# FPGA.net
KiCad netlist of a schematic drawn in Altium Designer
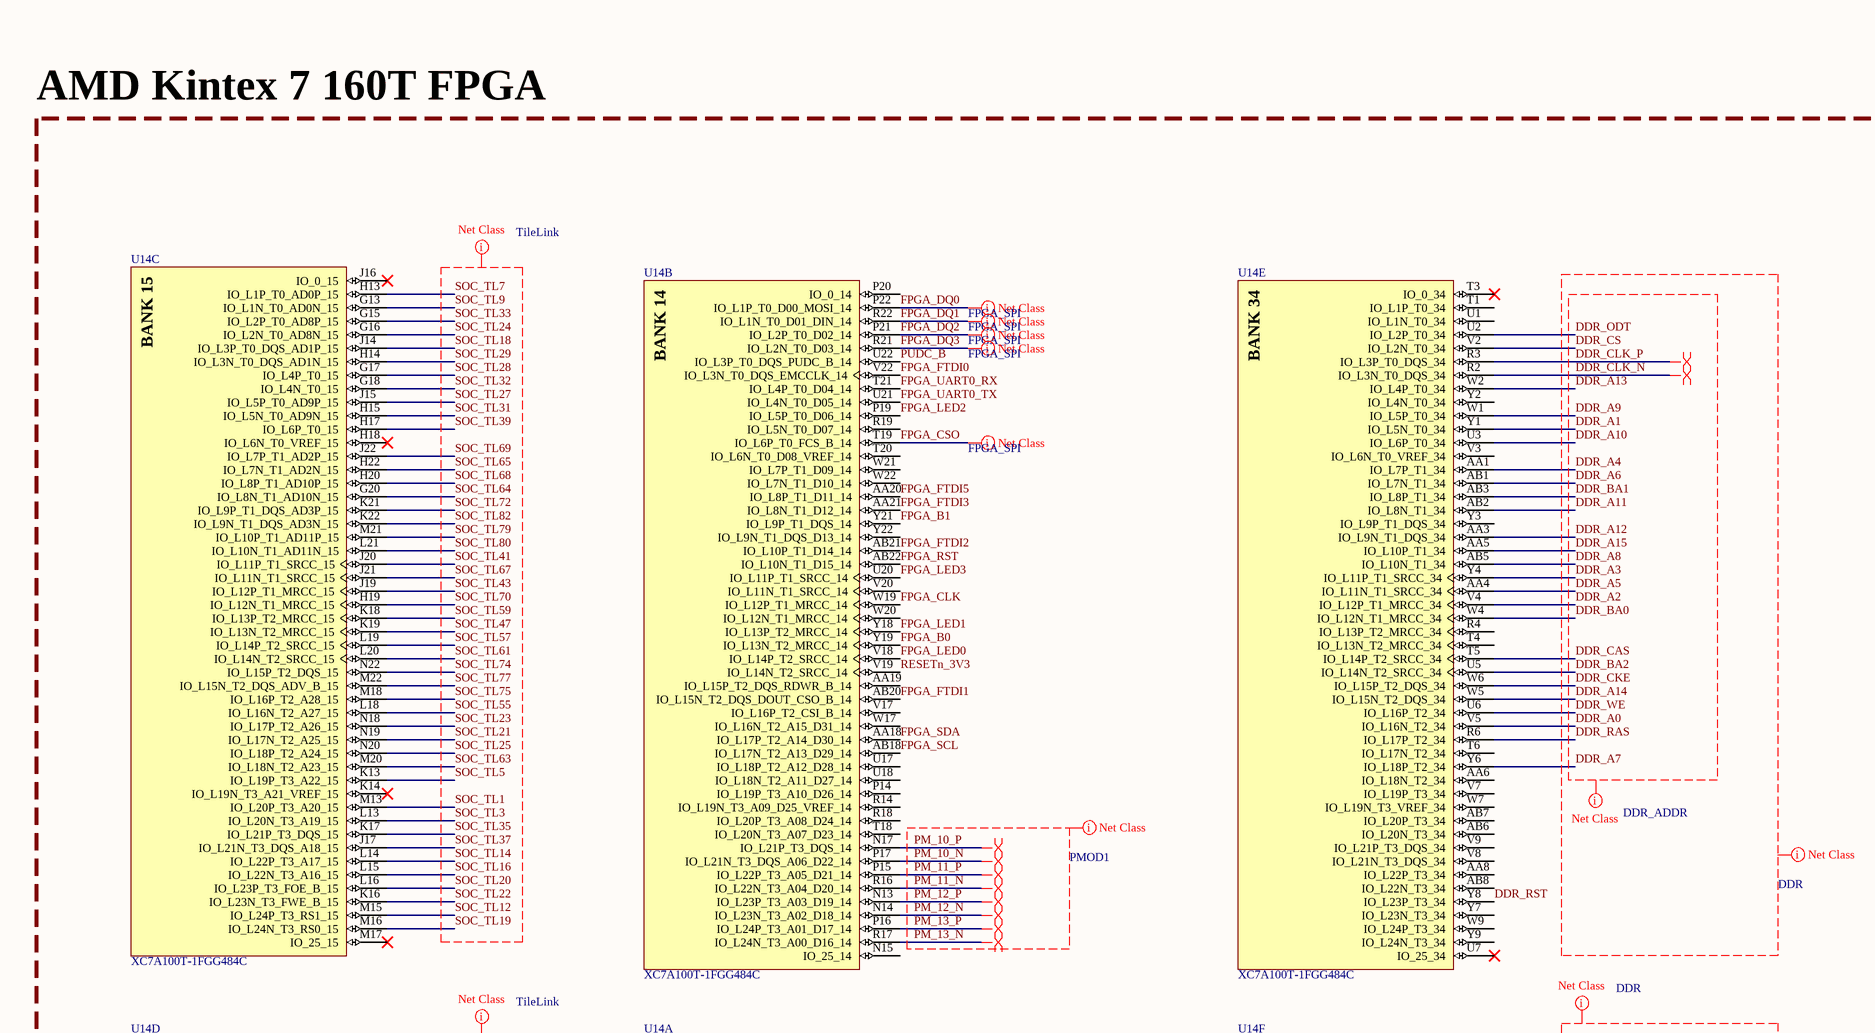
[diagram p0: FPGA.SchDoc, top left]
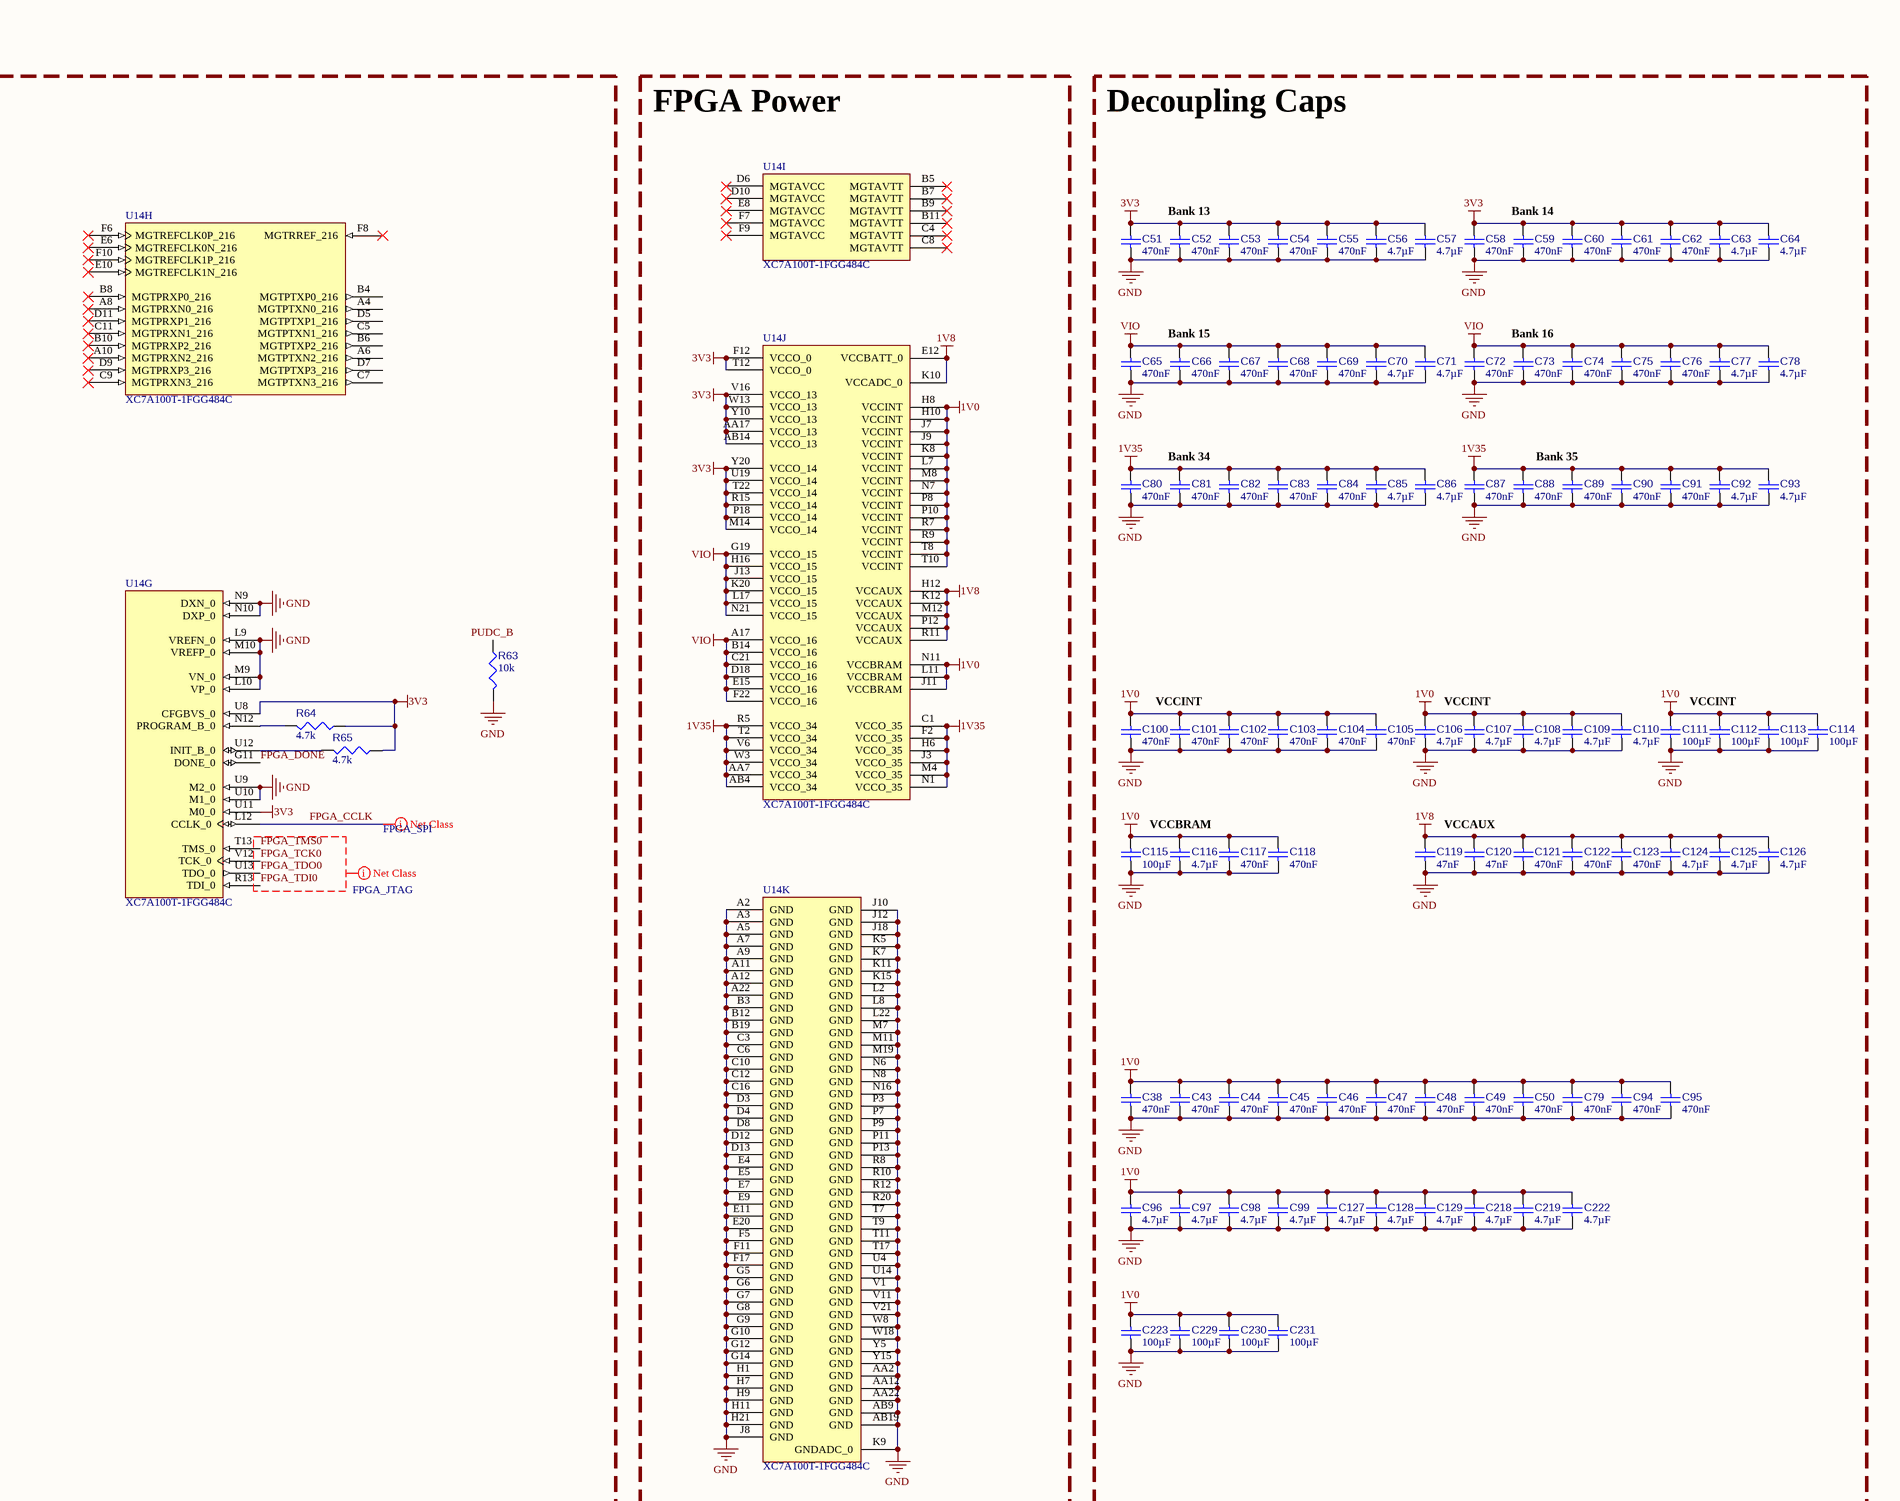
[diagram p1: FPGA.SchDoc, top right]
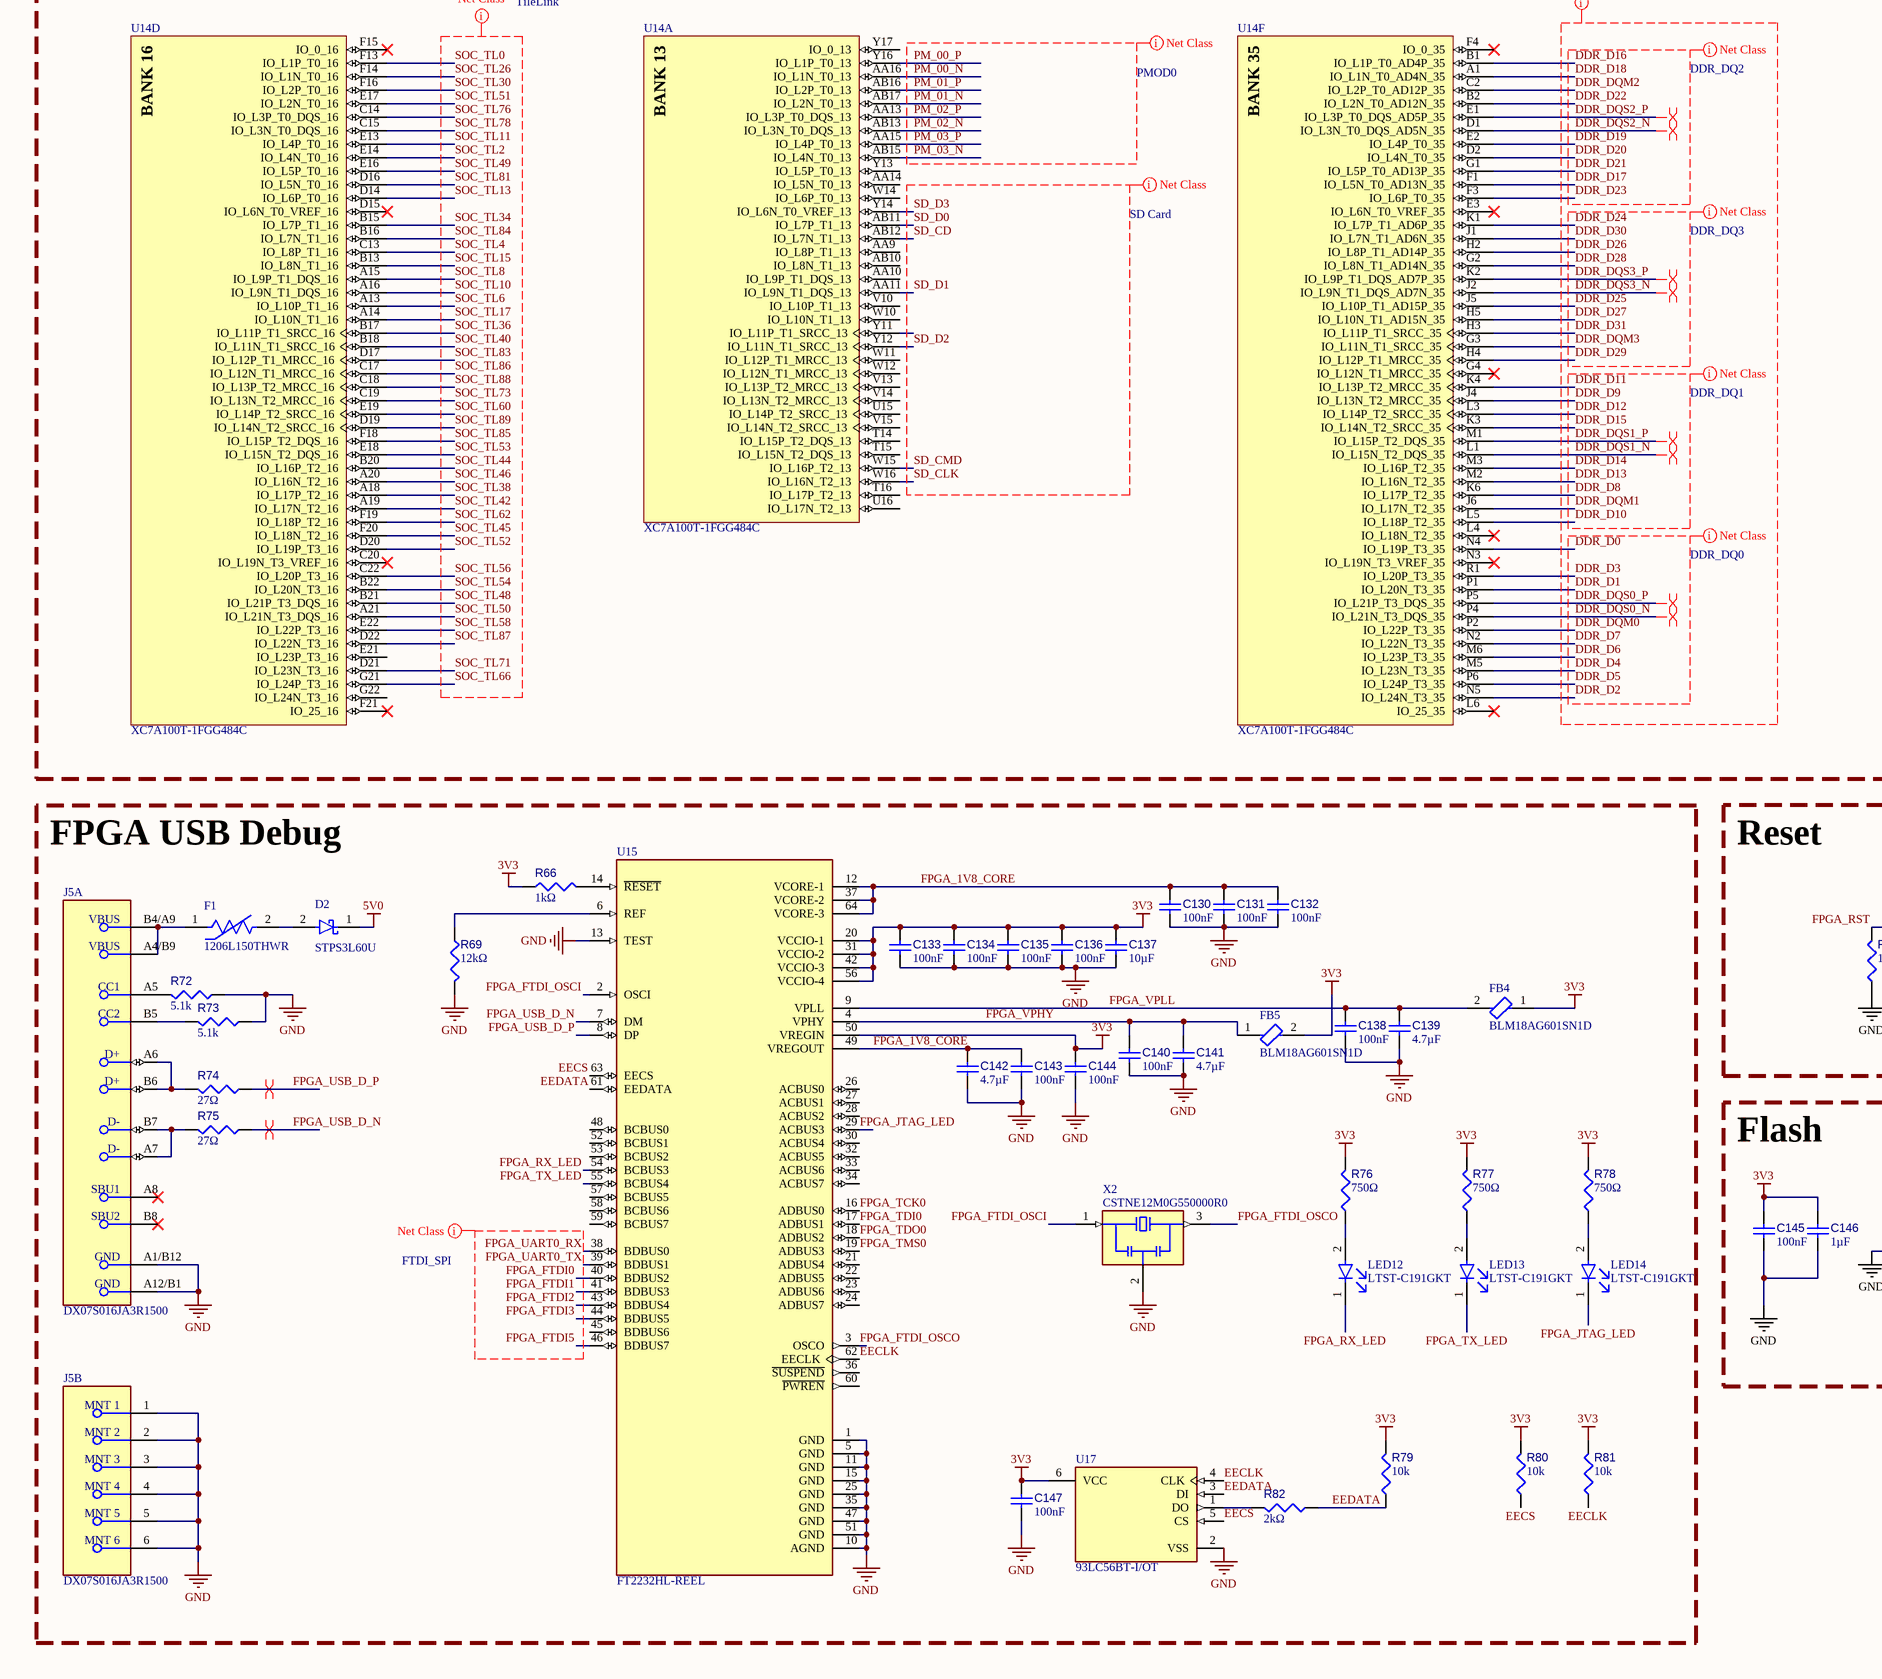
[diagram p2: FPGA.SchDoc, bottom left]
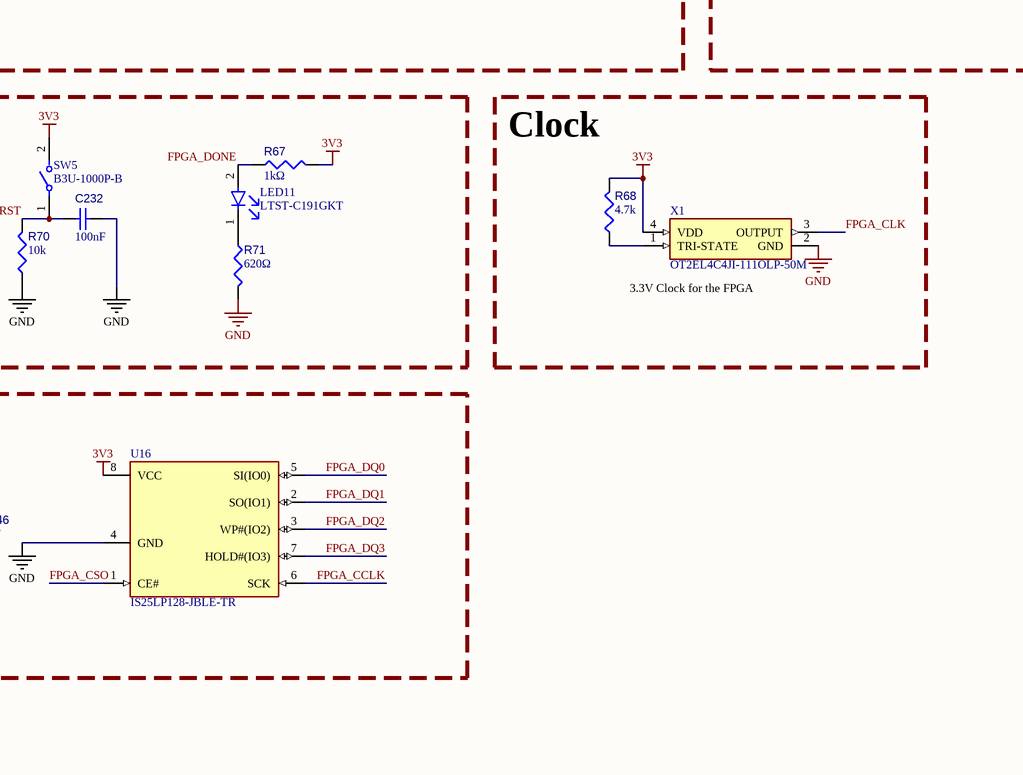
[diagram p3: FPGA.SchDoc, bottom right]

(export (version "E")
  (design (tool "Eeschema 10.0.6"))
  (components
    (comp (ref "C38")
      (value "470nF")
      (footprint "CAP-0402-MFG")
      (description "0402-470n-10%-16V-X5R-AECQ200")
      (fields (field (name "MANUFACTURER PART NUMBER") "GRT155R61C474KE01D") (field (name "TOLERANCE") "10%"))
      (libsource (lib "UC Berkeley – EE194") (part "CAP-NP-2P"))
    )
    (comp (ref "C43")
      (value "470nF")
      (footprint "CAP-0402-MFG")
      (description "0402-470n-10%-16V-X5R-AECQ200")
      (fields (field (name "MANUFACTURER PART NUMBER") "GRT155R61C474KE01D") (field (name "TOLERANCE") "10%"))
      (libsource (lib "UC Berkeley – EE194") (part "CAP-NP-2P"))
    )
    (comp (ref "C44")
      (value "470nF")
      (footprint "CAP-0402-MFG")
      (description "0402-470n-10%-16V-X5R-AECQ200")
      (fields (field (name "MANUFACTURER PART NUMBER") "GRT155R61C474KE01D") (field (name "TOLERANCE") "10%"))
      (libsource (lib "UC Berkeley – EE194") (part "CAP-NP-2P"))
    )
    (comp (ref "C45")
      (value "470nF")
      (footprint "CAP-0402-MFG")
      (description "0402-470n-10%-16V-X5R-AECQ200")
      (fields (field (name "MANUFACTURER PART NUMBER") "GRT155R61C474KE01D") (field (name "TOLERANCE") "10%"))
      (libsource (lib "UC Berkeley – EE194") (part "CAP-NP-2P"))
    )
    (comp (ref "C46")
      (value "470nF")
      (footprint "CAP-0402-MFG")
      (description "0402-470n-10%-16V-X5R-AECQ200")
      (fields (field (name "MANUFACTURER PART NUMBER") "GRT155R61C474KE01D") (field (name "TOLERANCE") "10%"))
      (libsource (lib "UC Berkeley – EE194") (part "CAP-NP-2P"))
    )
    (comp (ref "C47")
      (value "470nF")
      (footprint "CAP-0402-MFG")
      (description "0402-470n-10%-16V-X5R-AECQ200")
      (fields (field (name "MANUFACTURER PART NUMBER") "GRT155R61C474KE01D") (field (name "TOLERANCE") "10%"))
      (libsource (lib "UC Berkeley – EE194") (part "CAP-NP-2P"))
    )
    (comp (ref "C48")
      (value "470nF")
      (footprint "CAP-0402-MFG")
      (description "0402-470n-10%-16V-X5R-AECQ200")
      (fields (field (name "MANUFACTURER PART NUMBER") "GRT155R61C474KE01D") (field (name "TOLERANCE") "10%"))
      (libsource (lib "UC Berkeley – EE194") (part "CAP-NP-2P"))
    )
    (comp (ref "C49")
      (value "470nF")
      (footprint "CAP-0402-MFG")
      (description "0402-470n-10%-16V-X5R-AECQ200")
      (fields (field (name "MANUFACTURER PART NUMBER") "GRT155R61C474KE01D") (field (name "TOLERANCE") "10%"))
      (libsource (lib "UC Berkeley – EE194") (part "CAP-NP-2P"))
    )
    (comp (ref "C50")
      (value "470nF")
      (footprint "CAP-0402-MFG")
      (description "0402-470n-10%-16V-X5R-AECQ200")
      (fields (field (name "MANUFACTURER PART NUMBER") "GRT155R61C474KE01D") (field (name "TOLERANCE") "10%"))
      (libsource (lib "UC Berkeley – EE194") (part "CAP-NP-2P"))
    )
    (comp (ref "C51")
      (value "470nF")
      (footprint "CAP-0402-MFG")
      (description "0402-470n-10%-16V-X5R-AECQ200")
      (fields (field (name "MANUFACTURER PART NUMBER") "GRT155R61C474KE01D") (field (name "TOLERANCE") "10%"))
      (libsource (lib "UC Berkeley – EE194") (part "CAP-NP-2P"))
    )
    (comp (ref "C52")
      (value "470nF")
      (footprint "CAP-0402-MFG")
      (description "0402-470n-10%-16V-X5R-AECQ200")
      (fields (field (name "MANUFACTURER PART NUMBER") "GRT155R61C474KE01D") (field (name "TOLERANCE") "10%"))
      (libsource (lib "UC Berkeley – EE194") (part "CAP-NP-2P"))
    )
    (comp (ref "C53")
      (value "470nF")
      (footprint "CAP-0402-MFG")
      (description "0402-470n-10%-16V-X5R-AECQ200")
      (fields (field (name "MANUFACTURER PART NUMBER") "GRT155R61C474KE01D") (field (name "TOLERANCE") "10%"))
      (libsource (lib "UC Berkeley – EE194") (part "CAP-NP-2P"))
    )
    (comp (ref "C54")
      (value "470nF")
      (footprint "CAP-0402-MFG")
      (description "0402-470n-10%-16V-X5R-AECQ200")
      (fields (field (name "MANUFACTURER PART NUMBER") "GRT155R61C474KE01D") (field (name "TOLERANCE") "10%"))
      (libsource (lib "UC Berkeley – EE194") (part "CAP-NP-2P"))
    )
    (comp (ref "C55")
      (value "470nF")
      (footprint "CAP-0402-MFG")
      (description "0402-470n-10%-16V-X5R-AECQ200")
      (fields (field (name "MANUFACTURER PART NUMBER") "GRT155R61C474KE01D") (field (name "TOLERANCE") "10%"))
      (libsource (lib "UC Berkeley – EE194") (part "CAP-NP-2P"))
    )
    (comp (ref "C56")
      (value "4.7µF")
      (footprint "CAP-0402-MFG")
      (description "0402-4.7u-20%-25V-X5R")
      (fields (field (name "TOLERANCE") "20%") (field (name "MANUFACTURER PART NUMBER") "GRM155R61E475ME15D"))
      (libsource (lib "UC Berkeley – EE194") (part "CAP-NP-2P"))
    )
    (comp (ref "C57")
      (value "4.7µF")
      (footprint "CAP-0402-MFG")
      (description "0402-4.7u-20%-25V-X5R")
      (fields (field (name "TOLERANCE") "20%") (field (name "MANUFACTURER PART NUMBER") "GRM155R61E475ME15D"))
      (libsource (lib "UC Berkeley – EE194") (part "CAP-NP-2P"))
    )
    (comp (ref "C58")
      (value "470nF")
      (footprint "CAP-0402-MFG")
      (description "0402-470n-10%-16V-X5R-AECQ200")
      (fields (field (name "MANUFACTURER PART NUMBER") "GRT155R61C474KE01D") (field (name "TOLERANCE") "10%"))
      (libsource (lib "UC Berkeley – EE194") (part "CAP-NP-2P"))
    )
    (comp (ref "C59")
      (value "470nF")
      (footprint "CAP-0402-MFG")
      (description "0402-470n-10%-16V-X5R-AECQ200")
      (fields (field (name "MANUFACTURER PART NUMBER") "GRT155R61C474KE01D") (field (name "TOLERANCE") "10%"))
      (libsource (lib "UC Berkeley – EE194") (part "CAP-NP-2P"))
    )
    (comp (ref "C60")
      (value "470nF")
      (footprint "CAP-0402-MFG")
      (description "0402-470n-10%-16V-X5R-AECQ200")
      (fields (field (name "MANUFACTURER PART NUMBER") "GRT155R61C474KE01D") (field (name "TOLERANCE") "10%"))
      (libsource (lib "UC Berkeley – EE194") (part "CAP-NP-2P"))
    )
    (comp (ref "C61")
      (value "470nF")
      (footprint "CAP-0402-MFG")
      (description "0402-470n-10%-16V-X5R-AECQ200")
      (fields (field (name "MANUFACTURER PART NUMBER") "GRT155R61C474KE01D") (field (name "TOLERANCE") "10%"))
      (libsource (lib "UC Berkeley – EE194") (part "CAP-NP-2P"))
    )
    (comp (ref "C62")
      (value "470nF")
      (footprint "CAP-0402-MFG")
      (description "0402-470n-10%-16V-X5R-AECQ200")
      (fields (field (name "MANUFACTURER PART NUMBER") "GRT155R61C474KE01D") (field (name "TOLERANCE") "10%"))
      (libsource (lib "UC Berkeley – EE194") (part "CAP-NP-2P"))
    )
    (comp (ref "C63")
      (value "4.7µF")
      (footprint "CAP-0402-MFG")
      (description "0402-4.7u-20%-25V-X5R")
      (fields (field (name "TOLERANCE") "20%") (field (name "MANUFACTURER PART NUMBER") "GRM155R61E475ME15D"))
      (libsource (lib "UC Berkeley – EE194") (part "CAP-NP-2P"))
    )
    (comp (ref "C64")
      (value "4.7µF")
      (footprint "CAP-0402-MFG")
      (description "0402-4.7u-20%-25V-X5R")
      (fields (field (name "TOLERANCE") "20%") (field (name "MANUFACTURER PART NUMBER") "GRM155R61E475ME15D"))
      (libsource (lib "UC Berkeley – EE194") (part "CAP-NP-2P"))
    )
    (comp (ref "C65")
      (value "470nF")
      (footprint "CAP-0402-MFG")
      (description "0402-470n-10%-16V-X5R-AECQ200")
      (fields (field (name "MANUFACTURER PART NUMBER") "GRT155R61C474KE01D") (field (name "TOLERANCE") "10%"))
      (libsource (lib "UC Berkeley – EE194") (part "CAP-NP-2P"))
    )
    (comp (ref "C66")
      (value "470nF")
      (footprint "CAP-0402-MFG")
      (description "0402-470n-10%-16V-X5R-AECQ200")
      (fields (field (name "MANUFACTURER PART NUMBER") "GRT155R61C474KE01D") (field (name "TOLERANCE") "10%"))
      (libsource (lib "UC Berkeley – EE194") (part "CAP-NP-2P"))
    )
    (comp (ref "C67")
      (value "470nF")
      (footprint "CAP-0402-MFG")
      (description "0402-470n-10%-16V-X5R-AECQ200")
      (fields (field (name "MANUFACTURER PART NUMBER") "GRT155R61C474KE01D") (field (name "TOLERANCE") "10%"))
      (libsource (lib "UC Berkeley – EE194") (part "CAP-NP-2P"))
    )
    (comp (ref "C68")
      (value "470nF")
      (footprint "CAP-0402-MFG")
      (description "0402-470n-10%-16V-X5R-AECQ200")
      (fields (field (name "MANUFACTURER PART NUMBER") "GRT155R61C474KE01D") (field (name "TOLERANCE") "10%"))
      (libsource (lib "UC Berkeley – EE194") (part "CAP-NP-2P"))
    )
    (comp (ref "C69")
      (value "470nF")
      (footprint "CAP-0402-MFG")
      (description "0402-470n-10%-16V-X5R-AECQ200")
      (fields (field (name "MANUFACTURER PART NUMBER") "GRT155R61C474KE01D") (field (name "TOLERANCE") "10%"))
      (libsource (lib "UC Berkeley – EE194") (part "CAP-NP-2P"))
    )
    (comp (ref "C70")
      (value "4.7µF")
      (footprint "CAP-0402-MFG")
      (description "0402-4.7u-20%-25V-X5R")
      (fields (field (name "TOLERANCE") "20%") (field (name "MANUFACTURER PART NUMBER") "GRM155R61E475ME15D"))
      (libsource (lib "UC Berkeley – EE194") (part "CAP-NP-2P"))
    )
    (comp (ref "C71")
      (value "4.7µF")
      (footprint "CAP-0402-MFG")
      (description "0402-4.7u-20%-25V-X5R")
      (fields (field (name "TOLERANCE") "20%") (field (name "MANUFACTURER PART NUMBER") "GRM155R61E475ME15D"))
      (libsource (lib "UC Berkeley – EE194") (part "CAP-NP-2P"))
    )
    (comp (ref "C72")
      (value "470nF")
      (footprint "CAP-0402-MFG")
      (description "0402-470n-10%-16V-X5R-AECQ200")
      (fields (field (name "MANUFACTURER PART NUMBER") "GRT155R61C474KE01D") (field (name "TOLERANCE") "10%"))
      (libsource (lib "UC Berkeley – EE194") (part "CAP-NP-2P"))
    )
    (comp (ref "C73")
      (value "470nF")
      (footprint "CAP-0402-MFG")
      (description "0402-470n-10%-16V-X5R-AECQ200")
      (fields (field (name "MANUFACTURER PART NUMBER") "GRT155R61C474KE01D") (field (name "TOLERANCE") "10%"))
      (libsource (lib "UC Berkeley – EE194") (part "CAP-NP-2P"))
    )
    (comp (ref "C74")
      (value "470nF")
      (footprint "CAP-0402-MFG")
      (description "0402-470n-10%-16V-X5R-AECQ200")
      (fields (field (name "MANUFACTURER PART NUMBER") "GRT155R61C474KE01D") (field (name "TOLERANCE") "10%"))
      (libsource (lib "UC Berkeley – EE194") (part "CAP-NP-2P"))
    )
    (comp (ref "C75")
      (value "470nF")
      (footprint "CAP-0402-MFG")
      (description "0402-470n-10%-16V-X5R-AECQ200")
      (fields (field (name "MANUFACTURER PART NUMBER") "GRT155R61C474KE01D") (field (name "TOLERANCE") "10%"))
      (libsource (lib "UC Berkeley – EE194") (part "CAP-NP-2P"))
    )
    (comp (ref "C76")
      (value "470nF")
      (footprint "CAP-0402-MFG")
      (description "0402-470n-10%-16V-X5R-AECQ200")
      (fields (field (name "MANUFACTURER PART NUMBER") "GRT155R61C474KE01D") (field (name "TOLERANCE") "10%"))
      (libsource (lib "UC Berkeley – EE194") (part "CAP-NP-2P"))
    )
    (comp (ref "C77")
      (value "4.7µF")
      (footprint "CAP-0402-MFG")
      (description "0402-4.7u-20%-25V-X5R")
      (fields (field (name "TOLERANCE") "20%") (field (name "MANUFACTURER PART NUMBER") "GRM155R61E475ME15D"))
      (libsource (lib "UC Berkeley – EE194") (part "CAP-NP-2P"))
    )
    (comp (ref "C78")
      (value "4.7µF")
      (footprint "CAP-0402-MFG")
      (description "0402-4.7u-20%-25V-X5R")
      (fields (field (name "TOLERANCE") "20%") (field (name "MANUFACTURER PART NUMBER") "GRM155R61E475ME15D"))
      (libsource (lib "UC Berkeley – EE194") (part "CAP-NP-2P"))
    )
    (comp (ref "C79")
      (value "470nF")
      (footprint "CAP-0402-MFG")
      (description "0402-470n-10%-16V-X5R-AECQ200")
      (fields (field (name "MANUFACTURER PART NUMBER") "GRT155R61C474KE01D") (field (name "TOLERANCE") "10%"))
      (libsource (lib "UC Berkeley – EE194") (part "CAP-NP-2P"))
    )
    (comp (ref "C80")
      (value "470nF")
      (footprint "CAP-0402-MFG")
      (description "0402-470n-10%-16V-X5R-AECQ200")
      (fields (field (name "MANUFACTURER PART NUMBER") "GRT155R61C474KE01D") (field (name "TOLERANCE") "10%"))
      (libsource (lib "UC Berkeley – EE194") (part "CAP-NP-2P"))
    )
    (comp (ref "C81")
      (value "470nF")
      (footprint "CAP-0402-MFG")
      (description "0402-470n-10%-16V-X5R-AECQ200")
      (fields (field (name "MANUFACTURER PART NUMBER") "GRT155R61C474KE01D") (field (name "TOLERANCE") "10%"))
      (libsource (lib "UC Berkeley – EE194") (part "CAP-NP-2P"))
    )
    (comp (ref "C82")
      (value "470nF")
      (footprint "CAP-0402-MFG")
      (description "0402-470n-10%-16V-X5R-AECQ200")
      (fields (field (name "MANUFACTURER PART NUMBER") "GRT155R61C474KE01D") (field (name "TOLERANCE") "10%"))
      (libsource (lib "UC Berkeley – EE194") (part "CAP-NP-2P"))
    )
    (comp (ref "C83")
      (value "470nF")
      (footprint "CAP-0402-MFG")
      (description "0402-470n-10%-16V-X5R-AECQ200")
      (fields (field (name "MANUFACTURER PART NUMBER") "GRT155R61C474KE01D") (field (name "TOLERANCE") "10%"))
      (libsource (lib "UC Berkeley – EE194") (part "CAP-NP-2P"))
    )
    (comp (ref "C84")
      (value "470nF")
      (footprint "CAP-0402-MFG")
      (description "0402-470n-10%-16V-X5R-AECQ200")
      (fields (field (name "MANUFACTURER PART NUMBER") "GRT155R61C474KE01D") (field (name "TOLERANCE") "10%"))
      (libsource (lib "UC Berkeley – EE194") (part "CAP-NP-2P"))
    )
    (comp (ref "C85")
      (value "4.7µF")
      (footprint "CAP-0402-MFG")
      (description "0402-4.7u-20%-25V-X5R")
      (fields (field (name "TOLERANCE") "20%") (field (name "MANUFACTURER PART NUMBER") "GRM155R61E475ME15D"))
      (libsource (lib "UC Berkeley – EE194") (part "CAP-NP-2P"))
    )
    (comp (ref "C86")
      (value "4.7µF")
      (footprint "CAP-0402-MFG")
      (description "0402-4.7u-20%-25V-X5R")
      (fields (field (name "TOLERANCE") "20%") (field (name "MANUFACTURER PART NUMBER") "GRM155R61E475ME15D"))
      (libsource (lib "UC Berkeley – EE194") (part "CAP-NP-2P"))
    )
    (comp (ref "C87")
      (value "470nF")
      (footprint "CAP-0402-MFG")
      (description "0402-470n-10%-16V-X5R-AECQ200")
      (fields (field (name "MANUFACTURER PART NUMBER") "GRT155R61C474KE01D") (field (name "TOLERANCE") "10%"))
      (libsource (lib "UC Berkeley – EE194") (part "CAP-NP-2P"))
    )
    (comp (ref "C88")
      (value "470nF")
      (footprint "CAP-0402-MFG")
      (description "0402-470n-10%-16V-X5R-AECQ200")
      (fields (field (name "MANUFACTURER PART NUMBER") "GRT155R61C474KE01D") (field (name "TOLERANCE") "10%"))
      (libsource (lib "UC Berkeley – EE194") (part "CAP-NP-2P"))
    )
    (comp (ref "C89")
      (value "470nF")
      (footprint "CAP-0402-MFG")
      (description "0402-470n-10%-16V-X5R-AECQ200")
      (fields (field (name "MANUFACTURER PART NUMBER") "GRT155R61C474KE01D") (field (name "TOLERANCE") "10%"))
      (libsource (lib "UC Berkeley – EE194") (part "CAP-NP-2P"))
    )
    (comp (ref "C90")
      (value "470nF")
      (footprint "CAP-0402-MFG")
      (description "0402-470n-10%-16V-X5R-AECQ200")
      (fields (field (name "MANUFACTURER PART NUMBER") "GRT155R61C474KE01D") (field (name "TOLERANCE") "10%"))
      (libsource (lib "UC Berkeley – EE194") (part "CAP-NP-2P"))
    )
    (comp (ref "C91")
      (value "470nF")
      (footprint "CAP-0402-MFG")
      (description "0402-470n-10%-16V-X5R-AECQ200")
      (fields (field (name "MANUFACTURER PART NUMBER") "GRT155R61C474KE01D") (field (name "TOLERANCE") "10%"))
      (libsource (lib "UC Berkeley – EE194") (part "CAP-NP-2P"))
    )
    (comp (ref "C92")
      (value "4.7µF")
      (footprint "CAP-0402-MFG")
      (description "0402-4.7u-20%-25V-X5R")
      (fields (field (name "TOLERANCE") "20%") (field (name "MANUFACTURER PART NUMBER") "GRM155R61E475ME15D"))
      (libsource (lib "UC Berkeley – EE194") (part "CAP-NP-2P"))
    )
    (comp (ref "C93")
      (value "4.7µF")
      (footprint "CAP-0402-MFG")
      (description "0402-4.7u-20%-25V-X5R")
      (fields (field (name "TOLERANCE") "20%") (field (name "MANUFACTURER PART NUMBER") "GRM155R61E475ME15D"))
      (libsource (lib "UC Berkeley – EE194") (part "CAP-NP-2P"))
    )
    (comp (ref "C94")
      (value "470nF")
      (footprint "CAP-0402-MFG")
      (description "0402-470n-10%-16V-X5R-AECQ200")
      (fields (field (name "MANUFACTURER PART NUMBER") "GRT155R61C474KE01D") (field (name "TOLERANCE") "10%"))
      (libsource (lib "UC Berkeley – EE194") (part "CAP-NP-2P"))
    )
    (comp (ref "C95")
      (value "470nF")
      (footprint "CAP-0402-MFG")
      (description "0402-470n-10%-16V-X5R-AECQ200")
      (fields (field (name "MANUFACTURER PART NUMBER") "GRT155R61C474KE01D") (field (name "TOLERANCE") "10%"))
      (libsource (lib "UC Berkeley – EE194") (part "CAP-NP-2P"))
    )
    (comp (ref "C96")
      (value "4.7µF")
      (footprint "CAP-0402-MFG")
      (description "0402-4.7u-20%-25V-X5R")
      (fields (field (name "TOLERANCE") "20%") (field (name "MANUFACTURER PART NUMBER") "GRM155R61E475ME15D"))
      (libsource (lib "UC Berkeley – EE194") (part "CAP-NP-2P"))
    )
    (comp (ref "C97")
      (value "4.7µF")
      (footprint "CAP-0402-MFG")
      (description "0402-4.7u-20%-25V-X5R")
      (fields (field (name "TOLERANCE") "20%") (field (name "MANUFACTURER PART NUMBER") "GRM155R61E475ME15D"))
      (libsource (lib "UC Berkeley – EE194") (part "CAP-NP-2P"))
    )
    (comp (ref "C98")
      (value "4.7µF")
      (footprint "CAP-0402-MFG")
      (description "0402-4.7u-20%-25V-X5R")
      (fields (field (name "TOLERANCE") "20%") (field (name "MANUFACTURER PART NUMBER") "GRM155R61E475ME15D"))
      (libsource (lib "UC Berkeley – EE194") (part "CAP-NP-2P"))
    )
    (comp (ref "C99")
      (value "4.7µF")
      (footprint "CAP-0402-MFG")
      (description "0402-4.7u-20%-25V-X5R")
      (fields (field (name "TOLERANCE") "20%") (field (name "MANUFACTURER PART NUMBER") "GRM155R61E475ME15D"))
      (libsource (lib "UC Berkeley – EE194") (part "CAP-NP-2P"))
    )
    (comp (ref "C100")
      (value "470nF")
      (footprint "CAP-0402-MFG")
      (description "0402-470n-10%-16V-X5R-AECQ200")
      (fields (field (name "MANUFACTURER PART NUMBER") "GRT155R61C474KE01D") (field (name "TOLERANCE") "10%"))
      (libsource (lib "UC Berkeley – EE194") (part "CAP-NP-2P"))
    )
    (comp (ref "C101")
      (value "470nF")
      (footprint "CAP-0402-MFG")
      (description "0402-470n-10%-16V-X5R-AECQ200")
      (fields (field (name "MANUFACTURER PART NUMBER") "GRT155R61C474KE01D") (field (name "TOLERANCE") "10%"))
      (libsource (lib "UC Berkeley – EE194") (part "CAP-NP-2P"))
    )
    (comp (ref "C102")
      (value "470nF")
      (footprint "CAP-0402-MFG")
      (description "0402-470n-10%-16V-X5R-AECQ200")
      (fields (field (name "MANUFACTURER PART NUMBER") "GRT155R61C474KE01D") (field (name "TOLERANCE") "10%"))
      (libsource (lib "UC Berkeley – EE194") (part "CAP-NP-2P"))
    )
    (comp (ref "C103")
      (value "470nF")
      (footprint "CAP-0402-MFG")
      (description "0402-470n-10%-16V-X5R-AECQ200")
      (fields (field (name "MANUFACTURER PART NUMBER") "GRT155R61C474KE01D") (field (name "TOLERANCE") "10%"))
      (libsource (lib "UC Berkeley – EE194") (part "CAP-NP-2P"))
    )
    (comp (ref "C104")
      (value "470nF")
      (footprint "CAP-0402-MFG")
      (description "0402-470n-10%-16V-X5R-AECQ200")
      (fields (field (name "MANUFACTURER PART NUMBER") "GRT155R61C474KE01D") (field (name "TOLERANCE") "10%"))
      (libsource (lib "UC Berkeley – EE194") (part "CAP-NP-2P"))
    )
    (comp (ref "C105")
      (value "470nF")
      (footprint "CAP-0402-MFG")
      (description "0402-470n-10%-16V-X5R-AECQ200")
      (fields (field (name "MANUFACTURER PART NUMBER") "GRT155R61C474KE01D") (field (name "TOLERANCE") "10%"))
      (libsource (lib "UC Berkeley – EE194") (part "CAP-NP-2P"))
    )
    (comp (ref "C106")
      (value "4.7µF")
      (footprint "CAP-0402-MFG")
      (description "0402-4.7u-20%-25V-X5R")
      (fields (field (name "TOLERANCE") "20%") (field (name "MANUFACTURER PART NUMBER") "GRM155R61E475ME15D"))
      (libsource (lib "UC Berkeley – EE194") (part "CAP-NP-2P"))
    )
    (comp (ref "C107")
      (value "4.7µF")
      (footprint "CAP-0402-MFG")
      (description "0402-4.7u-20%-25V-X5R")
      (fields (field (name "TOLERANCE") "20%") (field (name "MANUFACTURER PART NUMBER") "GRM155R61E475ME15D"))
      (libsource (lib "UC Berkeley – EE194") (part "CAP-NP-2P"))
    )
    (comp (ref "C108")
      (value "4.7µF")
      (footprint "CAP-0402-MFG")
      (description "0402-4.7u-20%-25V-X5R")
      (fields (field (name "TOLERANCE") "20%") (field (name "MANUFACTURER PART NUMBER") "GRM155R61E475ME15D"))
      (libsource (lib "UC Berkeley – EE194") (part "CAP-NP-2P"))
    )
    (comp (ref "C109")
      (value "4.7µF")
      (footprint "CAP-0402-MFG")
      (description "0402-4.7u-20%-25V-X5R")
      (fields (field (name "TOLERANCE") "20%") (field (name "MANUFACTURER PART NUMBER") "GRM155R61E475ME15D"))
      (libsource (lib "UC Berkeley – EE194") (part "CAP-NP-2P"))
    )
    (comp (ref "C110")
      (value "4.7µF")
      (footprint "CAP-0402-MFG")
      (description "0402-4.7u-20%-25V-X5R")
      (fields (field (name "TOLERANCE") "20%") (field (name "MANUFACTURER PART NUMBER") "GRM155R61E475ME15D"))
      (libsource (lib "UC Berkeley – EE194") (part "CAP-NP-2P"))
    )
    (comp (ref "C111")
      (value "100µF")
      (footprint "CAP-0805-MFG")
      (description "0805-100u-20%-6.3V-X5R")
      (fields (field (name "MANUFACTURER PART NUMBER") "GRM21BR60J107ME15L") (field (name "TOLERANCE") "20%"))
      (libsource (lib "UC Berkeley – EE194") (part "CAP-NP-2P"))
    )
    (comp (ref "C112")
      (value "100µF")
      (footprint "CAP-0805-MFG")
      (description "0805-100u-20%-6.3V-X5R")
      (fields (field (name "MANUFACTURER PART NUMBER") "GRM21BR60J107ME15L") (field (name "TOLERANCE") "20%"))
      (libsource (lib "UC Berkeley – EE194") (part "CAP-NP-2P"))
    )
    (comp (ref "C113")
      (value "100µF")
      (footprint "CAP-0805-MFG")
      (description "0805-100u-20%-6.3V-X5R")
      (fields (field (name "MANUFACTURER PART NUMBER") "GRM21BR60J107ME15L") (field (name "TOLERANCE") "20%"))
      (libsource (lib "UC Berkeley – EE194") (part "CAP-NP-2P"))
    )
    (comp (ref "C114")
      (value "100µF")
      (footprint "CAP-0805-MFG")
      (description "0805-100u-20%-6.3V-X5R")
      (fields (field (name "MANUFACTURER PART NUMBER") "GRM21BR60J107ME15L") (field (name "TOLERANCE") "20%"))
      (libsource (lib "UC Berkeley – EE194") (part "CAP-NP-2P"))
    )
    (comp (ref "C115")
      (value "100µF")
      (footprint "CAP-0805-MFG")
      (description "0805-100u-20%-6.3V-X5R")
      (fields (field (name "MANUFACTURER PART NUMBER") "GRM21BR60J107ME15L") (field (name "TOLERANCE") "20%"))
      (libsource (lib "UC Berkeley – EE194") (part "CAP-NP-2P"))
    )
    (comp (ref "C116")
      (value "4.7µF")
      (footprint "CAP-0402-MFG")
      (description "0402-4.7u-20%-25V-X5R")
      (fields (field (name "TOLERANCE") "20%") (field (name "MANUFACTURER PART NUMBER") "GRM155R61E475ME15D"))
      (libsource (lib "UC Berkeley – EE194") (part "CAP-NP-2P"))
    )
    (comp (ref "C117")
      (value "470nF")
      (footprint "CAP-0402-MFG")
      (description "0402-470n-10%-16V-X5R-AECQ200")
      (fields (field (name "MANUFACTURER PART NUMBER") "GRT155R61C474KE01D") (field (name "TOLERANCE") "10%"))
      (libsource (lib "UC Berkeley – EE194") (part "CAP-NP-2P"))
    )
    (comp (ref "C118")
      (value "470nF")
      (footprint "CAP-0402-MFG")
      (description "0402-470n-10%-16V-X5R-AECQ200")
      (fields (field (name "MANUFACTURER PART NUMBER") "GRT155R61C474KE01D") (field (name "TOLERANCE") "10%"))
      (libsource (lib "UC Berkeley – EE194") (part "CAP-NP-2P"))
    )
    (comp (ref "C119")
      (value "47nF")
      (footprint "CAP-0402-MFG")
      (description "0402-47n-10%-16V-X7R-AECQ200")
      (fields (field (name "TOLERANCE") "10%") (field (name "MANUFACTURER PART NUMBER") "CL05B473KO5NNNC"))
      (libsource (lib "UC Berkeley – EE194") (part "CAP-NP-2P"))
    )
    (comp (ref "C120")
      (value "47nF")
      (footprint "CAP-0402-MFG")
      (description "0402-47n-10%-16V-X7R-AECQ200")
      (fields (field (name "TOLERANCE") "10%") (field (name "MANUFACTURER PART NUMBER") "CL05B473KO5NNNC"))
      (libsource (lib "UC Berkeley – EE194") (part "CAP-NP-2P"))
    )
    (comp (ref "C121")
      (value "470nF")
      (footprint "CAP-0402-MFG")
      (description "0402-470n-10%-16V-X5R-AECQ200")
      (fields (field (name "MANUFACTURER PART NUMBER") "GRT155R61C474KE01D") (field (name "TOLERANCE") "10%"))
      (libsource (lib "UC Berkeley – EE194") (part "CAP-NP-2P"))
    )
    (comp (ref "C122")
      (value "470nF")
      (footprint "CAP-0402-MFG")
      (description "0402-470n-10%-16V-X5R-AECQ200")
      (fields (field (name "MANUFACTURER PART NUMBER") "GRT155R61C474KE01D") (field (name "TOLERANCE") "10%"))
      (libsource (lib "UC Berkeley – EE194") (part "CAP-NP-2P"))
    )
    (comp (ref "C123")
      (value "470nF")
      (footprint "CAP-0402-MFG")
      (description "0402-470n-10%-16V-X5R-AECQ200")
      (fields (field (name "MANUFACTURER PART NUMBER") "GRT155R61C474KE01D") (field (name "TOLERANCE") "10%"))
      (libsource (lib "UC Berkeley – EE194") (part "CAP-NP-2P"))
    )
    (comp (ref "C124")
      (value "4.7µF")
      (footprint "CAP-0402-MFG")
      (description "0402-4.7u-20%-25V-X5R")
      (fields (field (name "TOLERANCE") "20%") (field (name "MANUFACTURER PART NUMBER") "GRM155R61E475ME15D"))
      (libsource (lib "UC Berkeley – EE194") (part "CAP-NP-2P"))
    )
    (comp (ref "C125")
      (value "4.7µF")
      (footprint "CAP-0402-MFG")
      (description "0402-4.7u-20%-25V-X5R")
      (fields (field (name "TOLERANCE") "20%") (field (name "MANUFACTURER PART NUMBER") "GRM155R61E475ME15D"))
      (libsource (lib "UC Berkeley – EE194") (part "CAP-NP-2P"))
    )
    (comp (ref "C126")
      (value "4.7µF")
      (footprint "CAP-0402-MFG")
      (description "0402-4.7u-20%-25V-X5R")
      (fields (field (name "TOLERANCE") "20%") (field (name "MANUFACTURER PART NUMBER") "GRM155R61E475ME15D"))
      (libsource (lib "UC Berkeley – EE194") (part "CAP-NP-2P"))
    )
    (comp (ref "C127")
      (value "4.7µF")
      (footprint "CAP-0402-MFG")
      (description "0402-4.7u-20%-25V-X5R")
      (fields (field (name "TOLERANCE") "20%") (field (name "MANUFACTURER PART NUMBER") "GRM155R61E475ME15D"))
      (libsource (lib "UC Berkeley – EE194") (part "CAP-NP-2P"))
    )
    (comp (ref "C128")
      (value "4.7µF")
      (footprint "CAP-0402-MFG")
      (description "0402-4.7u-20%-25V-X5R")
      (fields (field (name "TOLERANCE") "20%") (field (name "MANUFACTURER PART NUMBER") "GRM155R61E475ME15D"))
      (libsource (lib "UC Berkeley – EE194") (part "CAP-NP-2P"))
    )
    (comp (ref "C129")
      (value "4.7µF")
      (footprint "CAP-0402-MFG")
      (description "0402-4.7u-20%-25V-X5R")
      (fields (field (name "TOLERANCE") "20%") (field (name "MANUFACTURER PART NUMBER") "GRM155R61E475ME15D"))
      (libsource (lib "UC Berkeley – EE194") (part "CAP-NP-2P"))
    )
    (comp (ref "C130")
      (value "100nF")
      (footprint "CAP-0402-MFG")
      (description "0402-100n-10%-16V-X7R-AECQ200")
      (fields (field (name "TOLERANCE") "10%") (field (name "MANUFACTURER PART NUMBER") "CL05B104KO5VPNC"))
      (libsource (lib "UC Berkeley – EE194") (part "CAP-NP-2P"))
    )
    (comp (ref "C131")
      (value "100nF")
      (footprint "CAP-0402-MFG")
      (description "0402-100n-10%-16V-X7R-AECQ200")
      (fields (field (name "TOLERANCE") "10%") (field (name "MANUFACTURER PART NUMBER") "CL05B104KO5VPNC"))
      (libsource (lib "UC Berkeley – EE194") (part "CAP-NP-2P"))
    )
    (comp (ref "C132")
      (value "100nF")
      (footprint "CAP-0402-MFG")
      (description "0402-100n-10%-16V-X7R-AECQ200")
      (fields (field (name "TOLERANCE") "10%") (field (name "MANUFACTURER PART NUMBER") "CL05B104KO5VPNC"))
      (libsource (lib "UC Berkeley – EE194") (part "CAP-NP-2P"))
    )
    (comp (ref "C133")
      (value "100nF")
      (footprint "CAP-0402-MFG")
      (description "0402-100n-10%-16V-X7R-AECQ200")
      (fields (field (name "TOLERANCE") "10%") (field (name "MANUFACTURER PART NUMBER") "CL05B104KO5VPNC"))
      (libsource (lib "UC Berkeley – EE194") (part "CAP-NP-2P"))
    )
    (comp (ref "C134")
      (value "100nF")
      (footprint "CAP-0402-MFG")
      (description "0402-100n-10%-16V-X7R-AECQ200")
      (fields (field (name "TOLERANCE") "10%") (field (name "MANUFACTURER PART NUMBER") "CL05B104KO5VPNC"))
      (libsource (lib "UC Berkeley – EE194") (part "CAP-NP-2P"))
    )
    (comp (ref "C135")
      (value "100nF")
      (footprint "CAP-0402-MFG")
      (description "0402-100n-10%-16V-X7R-AECQ200")
      (fields (field (name "TOLERANCE") "10%") (field (name "MANUFACTURER PART NUMBER") "CL05B104KO5VPNC"))
      (libsource (lib "UC Berkeley – EE194") (part "CAP-NP-2P"))
    )
    (comp (ref "C136")
      (value "100nF")
      (footprint "CAP-0402-MFG")
      (description "0402-100n-10%-16V-X7R-AECQ200")
      (fields (field (name "TOLERANCE") "10%") (field (name "MANUFACTURER PART NUMBER") "CL05B104KO5VPNC"))
      (libsource (lib "UC Berkeley – EE194") (part "CAP-NP-2P"))
    )
    (comp (ref "C137")
      (value "10µF")
      (footprint "CAP-0603-MFG")
      (description "0603-10u-10%-16V-X5R-AECQ200")
      (fields (field (name "TOLERANCE") "10%") (field (name "MANUFACTURER PART NUMBER") "GRT188R61C106KE13J"))
      (libsource (lib "UC Berkeley – EE194") (part "CAP-NP-2P"))
    )
    (comp (ref "C138")
      (value "100nF")
      (footprint "CAP-0402-MFG")
      (description "0402-100n-10%-16V-X7R-AECQ200")
      (fields (field (name "TOLERANCE") "10%") (field (name "MANUFACTURER PART NUMBER") "CL05B104KO5VPNC"))
      (libsource (lib "UC Berkeley – EE194") (part "CAP-NP-2P"))
    )
    (comp (ref "C139")
      (value "4.7µF")
      (footprint "CAP-0402-MFG")
      (description "0402-4.7u-20%-25V-X5R")
      (fields (field (name "TOLERANCE") "20%") (field (name "MANUFACTURER PART NUMBER") "GRM155R61E475ME15D"))
      (libsource (lib "UC Berkeley – EE194") (part "CAP-NP-2P"))
    )
    (comp (ref "C140")
      (value "100nF")
      (footprint "CAP-0402-MFG")
      (description "0402-100n-10%-16V-X7R-AECQ200")
      (fields (field (name "TOLERANCE") "10%") (field (name "MANUFACTURER PART NUMBER") "CL05B104KO5VPNC"))
      (libsource (lib "UC Berkeley – EE194") (part "CAP-NP-2P"))
    )
    (comp (ref "C141")
      (value "4.7µF")
      (footprint "CAP-0402-MFG")
      (description "0402-4.7u-20%-25V-X5R")
      (fields (field (name "TOLERANCE") "20%") (field (name "MANUFACTURER PART NUMBER") "GRM155R61E475ME15D"))
      (libsource (lib "UC Berkeley – EE194") (part "CAP-NP-2P"))
    )
    (comp (ref "C142")
      (value "4.7µF")
      (footprint "CAP-0402-MFG")
      (description "0402-4.7u-20%-25V-X5R")
      (fields (field (name "TOLERANCE") "20%") (field (name "MANUFACTURER PART NUMBER") "GRM155R61E475ME15D"))
      (libsource (lib "UC Berkeley – EE194") (part "CAP-NP-2P"))
    )
    (comp (ref "C143")
      (value "100nF")
      (footprint "CAP-0402-MFG")
      (description "0402-100n-10%-16V-X7R-AECQ200")
      (fields (field (name "TOLERANCE") "10%") (field (name "MANUFACTURER PART NUMBER") "CL05B104KO5VPNC"))
      (libsource (lib "UC Berkeley – EE194") (part "CAP-NP-2P"))
    )
    (comp (ref "C144")
      (value "100nF")
      (footprint "CAP-0402-MFG")
      (description "0402-100n-10%-16V-X7R-AECQ200")
      (fields (field (name "TOLERANCE") "10%") (field (name "MANUFACTURER PART NUMBER") "CL05B104KO5VPNC"))
      (libsource (lib "UC Berkeley – EE194") (part "CAP-NP-2P"))
    )
    (comp (ref "C145")
      (value "100nF")
      (footprint "CAP-0402-MFG")
      (description "0402-100n-10%-16V-X7R-AECQ200")
      (fields (field (name "TOLERANCE") "10%") (field (name "MANUFACTURER PART NUMBER") "CL05B104KO5VPNC"))
      (libsource (lib "UC Berkeley – EE194") (part "CAP-NP-2P"))
    )
    (comp (ref "C146")
      (value "1µF")
      (footprint "CAP-0402-MFG")
      (description "0402-1u-10%-16V-X6S-AECQ200")
      (fields (field (name "MANUFACTURER PART NUMBER") "GRT155C81C105KE13J") (field (name "TOLERANCE") "10%"))
      (libsource (lib "UC Berkeley – EE194") (part "CAP-NP-2P"))
    )
    (comp (ref "C147")
      (value "100nF")
      (footprint "CAP-0402-MFG")
      (description "0402-100n-10%-16V-X7R-AECQ200")
      (fields (field (name "TOLERANCE") "10%") (field (name "MANUFACTURER PART NUMBER") "CL05B104KO5VPNC"))
      (libsource (lib "UC Berkeley – EE194") (part "CAP-NP-2P"))
    )
    (comp (ref "C218")
      (value "4.7µF")
      (footprint "CAP-0402-MFG")
      (description "0402-4.7u-20%-25V-X5R")
      (fields (field (name "TOLERANCE") "20%") (field (name "MANUFACTURER PART NUMBER") "GRM155R61E475ME15D"))
      (libsource (lib "UC Berkeley – EE194") (part "CAP-NP-2P"))
    )
    (comp (ref "C219")
      (value "4.7µF")
      (footprint "CAP-0402-MFG")
      (description "0402-4.7u-20%-25V-X5R")
      (fields (field (name "TOLERANCE") "20%") (field (name "MANUFACTURER PART NUMBER") "GRM155R61E475ME15D"))
      (libsource (lib "UC Berkeley – EE194") (part "CAP-NP-2P"))
    )
    (comp (ref "C222")
      (value "4.7µF")
      (footprint "CAP-0402-MFG")
      (description "0402-4.7u-20%-25V-X5R")
      (fields (field (name "TOLERANCE") "20%") (field (name "MANUFACTURER PART NUMBER") "GRM155R61E475ME15D"))
      (libsource (lib "UC Berkeley – EE194") (part "CAP-NP-2P"))
    )
    (comp (ref "C223")
      (value "100µF")
      (footprint "CAP-0805-MFG")
      (description "0805-100u-20%-6.3V-X5R")
      (fields (field (name "MANUFACTURER PART NUMBER") "GRM21BR60J107ME15L") (field (name "TOLERANCE") "20%"))
      (libsource (lib "UC Berkeley – EE194") (part "CAP-NP-2P"))
    )
    (comp (ref "C229")
      (value "100µF")
      (footprint "CAP-0805-MFG")
      (description "0805-100u-20%-6.3V-X5R")
      (fields (field (name "MANUFACTURER PART NUMBER") "GRM21BR60J107ME15L") (field (name "TOLERANCE") "20%"))
      (libsource (lib "UC Berkeley – EE194") (part "CAP-NP-2P"))
    )
    (comp (ref "C230")
      (value "100µF")
      (footprint "CAP-0805-MFG")
      (description "0805-100u-20%-6.3V-X5R")
      (fields (field (name "MANUFACTURER PART NUMBER") "GRM21BR60J107ME15L") (field (name "TOLERANCE") "20%"))
      (libsource (lib "UC Berkeley – EE194") (part "CAP-NP-2P"))
    )
    (comp (ref "C231")
      (value "100µF")
      (footprint "CAP-0805-MFG")
      (description "0805-100u-20%-6.3V-X5R")
      (fields (field (name "MANUFACTURER PART NUMBER") "GRM21BR60J107ME15L") (field (name "TOLERANCE") "20%"))
      (libsource (lib "UC Berkeley – EE194") (part "CAP-NP-2P"))
    )
    (comp (ref "C232")
      (value "100nF")
      (footprint "CAP-0402-MFG")
      (description "0402-100n-10%-25V-X7R-AECQ200")
      (fields (field (name "TOLERANCE") "10%") (field (name "MANUFACTURER PART NUMBER") "CL05B104KA54PNC"))
      (libsource (lib "UC Berkeley – EE194") (part "CAP-NP-2P"))
    )
    (comp (ref "D2")
      (value "STPS3L60U")
      (footprint "FP-DO214AA-MFG")
      (description "DO214AA-UNI-SCHOTTKY-60V-3A-590mV")
      (libsource (lib "UC Berkeley – EE194") (part "SCHOTTKY-UNI-2P-DIODE"))
    )
    (comp (ref "F1")
      (value "1206L150THWR")
      (footprint "FP-1206L050YR-MFG")
      (description "PTC Resettable Fuse 1.5A(hold) 3A(trip) 8VDC 100A 0.8W 0.3s 0.04Ohm SMD Solder Pad 1206 T/R")
      (libsource (lib "UC Berkeley – EE194") (part "FUSE-2P"))
    )
    (comp (ref "FB4")
      (value "BLM18AG601SN1D")
      (footprint "FERRITEBEAD-0603-MFG")
      (description "Ferrite Beads Multi-Layer 600Ohm 25% 100MHz 500mA 380mOhm DCR 0603 Automotive Paper T/R")
      (fields (field (name "TOLERANCE") "25%"))
      (libsource (lib "UC Berkeley – EE194") (part "FERRITE-BEAD-2P"))
    )
    (comp (ref "FB5")
      (value "BLM18AG601SN1D")
      (footprint "FERRITEBEAD-0603-MFG")
      (description "Ferrite Beads Multi-Layer 600Ohm 25% 100MHz 500mA 380mOhm DCR 0603 Automotive Paper T/R")
      (fields (field (name "TOLERANCE") "25%"))
      (libsource (lib "UC Berkeley – EE194") (part "FERRITE-BEAD-2P"))
    )
    (comp (ref "J5")
      (value "DX07S016JA3R1500")
      (footprint "FP-DX07S016JA3R1500-MFG")
      (description "Receptacle, 16 Position, 1-Row SMT, without Rear Shield, Shell-DIP Length 1.2mm")
      (libsource (lib "UC Berkeley – EE194") (part "DX07S016JA3R1500"))
    )
    (comp (ref "LED11")
      (value "LTST-C191GKT")
      (footprint "LED-0603-MFG")
      (description "LED yellow green 0603 wavelength 569nm light intensity 12mcd Front Mounting")
      (libsource (lib "UC Berkeley – EE194") (part "LED"))
    )
    (comp (ref "LED12")
      (value "LTST-C191GKT")
      (footprint "LED-0603-MFG")
      (description "LED yellow green 0603 wavelength 569nm light intensity 12mcd Front Mounting")
      (libsource (lib "UC Berkeley – EE194") (part "LED"))
    )
    (comp (ref "LED13")
      (value "LTST-C191GKT")
      (footprint "LED-0603-MFG")
      (description "LED yellow green 0603 wavelength 569nm light intensity 12mcd Front Mounting")
      (libsource (lib "UC Berkeley – EE194") (part "LED"))
    )
    (comp (ref "LED14")
      (value "LTST-C191GKT")
      (footprint "LED-0603-MFG")
      (description "LED yellow green 0603 wavelength 569nm light intensity 12mcd Front Mounting")
      (libsource (lib "UC Berkeley – EE194") (part "LED"))
    )
    (comp (ref "R63")
      (value "10k")
      (footprint "RES-0402")
      (description "0402-10k-1%-1/16W-AEC-Q200")
      (fields (field (name "TOLERANCE") "1%") (field (name "MANUFACTURER PART NUMBER") "AC0402FR-0710KL"))
      (libsource (lib "UC Berkeley – EE194") (part "RES-2P"))
    )
    (comp (ref "R64")
      (value "4.7k")
      (footprint "RES-0402")
      (description "0402-4.7k-1%-1/16W-AEC-Q200")
      (fields (field (name "TOLERANCE") "1%") (field (name "POWER") "63mW"))
      (libsource (lib "UC Berkeley – EE194") (part "RES-2P"))
    )
    (comp (ref "R65")
      (value "4.7k")
      (footprint "RES-0402")
      (description "0402-4.7k-1%-1/16W-AEC-Q200")
      (fields (field (name "TOLERANCE") "1%") (field (name "POWER") "63mW"))
      (libsource (lib "UC Berkeley – EE194") (part "RES-2P"))
    )
    (comp (ref "R66")
      (value "1kΩ")
      (footprint "RES-0402")
      (description "0402-1k-1%-1/16W-AEC-Q200")
      (fields (field (name "MANUFACTURER PART NUMBER") "AC0402FR-071KL") (field (name "POWER") "63mW"))
      (libsource (lib "UC Berkeley – EE194") (part "RES-2P"))
    )
    (comp (ref "R67")
      (value "1kΩ")
      (footprint "RES-0402")
      (description "0402-1k-1%-1/16W-AEC-Q200")
      (fields (field (name "MANUFACTURER PART NUMBER") "AC0402FR-071KL") (field (name "POWER") "63mW"))
      (libsource (lib "UC Berkeley – EE194") (part "RES-2P"))
    )
    (comp (ref "R68")
      (value "4.7k")
      (footprint "RES-0402")
      (description "0402-4.7k-1%-1/16W-AEC-Q200")
      (fields (field (name "TOLERANCE") "1%") (field (name "POWER") "63mW"))
      (libsource (lib "UC Berkeley – EE194") (part "RES-2P"))
    )
    (comp (ref "R69")
      (value "12kΩ")
      (footprint "RES-0402")
      (description "0402-12k-1%-1/16W-AEC-Q200")
      (fields (field (name "POWER") "63mW") (field (name "TOLERANCE") "1%"))
      (libsource (lib "UC Berkeley – EE194") (part "RES-2P"))
    )
    (comp (ref "R70")
      (value "10k")
      (footprint "RES-0402")
      (description "0402-10k-1%-1/16W-AEC-Q200")
      (fields (field (name "TOLERANCE") "1%") (field (name "MANUFACTURER PART NUMBER") "AC0402FR-0710KL"))
      (libsource (lib "UC Berkeley – EE194") (part "RES-2P"))
    )
    (comp (ref "R71")
      (value "620Ω")
      (footprint "RES-0402")
      (description "0402-620-1%-1/16W-AEC-Q200")
      (fields (field (name "MANUFACTURER PART NUMBER") "AC0402FR-07620RL") (field (name "TOLERANCE") "1%"))
      (libsource (lib "UC Berkeley – EE194") (part "RES-2P"))
    )
    (comp (ref "R72")
      (value "5.1k")
      (footprint "RES-0402")
      (description "0402-5.1k-1%-1/16W-AEC-Q200")
      (fields (field (name "TOLERANCE") "1%") (field (name "MANUFACTURER PART NUMBER") "AC0402FR-075K1L"))
      (libsource (lib "UC Berkeley – EE194") (part "RES-2P"))
    )
    (comp (ref "R73")
      (value "5.1k")
      (footprint "RES-0402")
      (description "0402-5.1k-1%-1/16W-AEC-Q200")
      (fields (field (name "TOLERANCE") "1%") (field (name "MANUFACTURER PART NUMBER") "AC0402FR-075K1L"))
      (libsource (lib "UC Berkeley – EE194") (part "RES-2P"))
    )
    (comp (ref "R74")
      (value "27Ω")
      (footprint "RES-0402")
      (description "0402-27-1%-1/16W-AEC-Q200")
      (fields (field (name "TOLERANCE") "1%") (field (name "MANUFACTURER PART NUMBER") "AC0402FR-0727RL"))
      (libsource (lib "UC Berkeley – EE194") (part "RES-2P"))
    )
    (comp (ref "R75")
      (value "27Ω")
      (footprint "RES-0402")
      (description "0402-27-1%-1/16W-AEC-Q200")
      (fields (field (name "TOLERANCE") "1%") (field (name "MANUFACTURER PART NUMBER") "AC0402FR-0727RL"))
      (libsource (lib "UC Berkeley – EE194") (part "RES-2P"))
    )
    (comp (ref "R76")
      (value "750Ω")
      (footprint "RES-0402")
      (description "0402-750-1%-1/16W-AEC-Q200")
      (fields (field (name "TOLERANCE") "1%") (field (name "POWER") "63mW"))
      (libsource (lib "UC Berkeley – EE194") (part "RES-2P"))
    )
    (comp (ref "R77")
      (value "750Ω")
      (footprint "RES-0402")
      (description "0402-750-1%-1/16W-AEC-Q200")
      (fields (field (name "TOLERANCE") "1%") (field (name "POWER") "63mW"))
      (libsource (lib "UC Berkeley – EE194") (part "RES-2P"))
    )
    (comp (ref "R78")
      (value "750Ω")
      (footprint "RES-0402")
      (description "0402-750-1%-1/16W-AEC-Q200")
      (fields (field (name "TOLERANCE") "1%") (field (name "POWER") "63mW"))
      (libsource (lib "UC Berkeley – EE194") (part "RES-2P"))
    )
    (comp (ref "R79")
      (value "10k")
      (footprint "RES-0402")
      (description "0402-10k-1%-1/16W-AEC-Q200")
      (fields (field (name "TOLERANCE") "1%") (field (name "MANUFACTURER PART NUMBER") "AC0402FR-0710KL"))
      (libsource (lib "UC Berkeley – EE194") (part "RES-2P"))
    )
    (comp (ref "R80")
      (value "10k")
      (footprint "RES-0402")
      (description "0402-10k-1%-1/16W-AEC-Q200")
      (fields (field (name "TOLERANCE") "1%") (field (name "MANUFACTURER PART NUMBER") "AC0402FR-0710KL"))
      (libsource (lib "UC Berkeley – EE194") (part "RES-2P"))
    )
    (comp (ref "R81")
      (value "10k")
      (footprint "RES-0402")
      (description "0402-10k-1%-1/16W-AEC-Q200")
      (fields (field (name "TOLERANCE") "1%") (field (name "MANUFACTURER PART NUMBER") "AC0402FR-0710KL"))
      (libsource (lib "UC Berkeley – EE194") (part "RES-2P"))
    )
    (comp (ref "R82")
      (value "2kΩ")
      (footprint "RES-0402")
      (description "0402-2k-1%-1/16W-AEC-Q200")
      (fields (field (name "TOLERANCE") "1%") (field (name "POWER") "63mW"))
      (libsource (lib "UC Berkeley – EE194") (part "RES-2P"))
    )
    (comp (ref "SW5")
      (value "B3U-1000P-B")
      (footprint "FP-B3U-1000P-B-MFG")
      (description "Switch Tactile N.O. SPST Round Button Gull Wing 0.05A 12VDC 1.5N SMD Embossed T/R")
      (libsource (lib "UC Berkeley – EE194") (part "SWITCH-SPST-OFF-MOM-2P"))
    )
    (comp (ref "U14")
      (value "XC7A100T-1FGG484C")
      (footprint "FGG484")
      (description "ARTIX-7 FPGA Field Programmable Gate Array, 7925 CLBs, 1098MHz, 101440-Cell, CMOS, PBGA484")
      (libsource (lib "UC Berkeley – EE194") (part "XNLX-XC7A100T-XNLX-FGG484"))
    )
    (comp (ref "U15")
      (value "FT2232HL-REEL")
      (footprint "LQFP-64-MFG")
      (description "USB Hi-Speed to Dual Channel Serial UART/FIFO/JTAG/SPI/I2C IC - LQFP-64")
      (libsource (lib "UC Berkeley – EE194") (part "FT2232HL-REEL"))
    )
    (comp (ref "U16")
      (value "IS25LP128-JBLE-TR")
      (footprint "FP-SOIC8-MFG")
      (description "NOR Flash Serial (SPI, Dual SPI, Quad SPI) 2.5V/3V/3.3V 128M-bit 16M x 8 8ns 8-Pin SOIC T/R")
      (fields (field (name "COPYRIGHT") "Copyright (C) 2025 Ultra Librarian. All rights reserved."))
      (libsource (lib "UC Berkeley – EE194") (part "IS25LP128-JBLE-TR"))
    )
    (comp (ref "U17")
      (value "93LC56BT-I/OT")
      (footprint "FP-SOT-23-6-MFG")
      (description "Microwire Serial EEPROM Family, 2.5Vto 5.5V' 2 MHz, -40°Cto 125°C, SOT-23-6, RoHS")
      (libsource (lib "UC Berkeley – EE194") (part "93LC56BT-I/OT"))
    )
    (comp (ref "X1")
      (value "OT2EL4C4JI-111OLP-50M")
      (footprint "OSC_SMD3225-4P")
      (description "1.8V~3.3V ±10ppm ±20ppm CMOS 50MHz SMD3225-4P")
      (fields (field (name "SOURCE") "BWRC.SchLib"))
      (libsource (lib "UC Berkeley – EE194") (part "OT2EL4C4JI-111OLP-50M"))
    )
    (comp (ref "X2")
      (value "CSTNE12M0G550000R0")
      (footprint "OSC-SMD3213-3P")
      (description "Ceramic Resonator 12MHz ±0.5% (Tol) ±0.2% (Stability) 33pF 30Ohm 3-Pin CSMD T/R")
      (libsource (lib "UC Berkeley – EE194") (part "CSTNE12M0G550000R0"))
    )
  )
  (nets
    (net (code "1") (name "/DDR_A0") (class "Default")
      (node (ref "U14") (pin "V5") (pinfunction "IO_L16N_T2_34_V5") (pintype "bidirectional"))
    )
    (net (code "2") (name "/DDR_A1") (class "Default")
      (node (ref "U14") (pin "Y1") (pinfunction "IO_L5N_T0_34_Y1") (pintype "bidirectional"))
    )
    (net (code "3") (name "/DDR_A2") (class "Default")
      (node (ref "U14") (pin "V4") (pinfunction "IO_L12P_T1_MRCC_34_V4") (pintype "bidirectional"))
    )
    (net (code "4") (name "/DDR_A3") (class "Default")
      (node (ref "U14") (pin "Y4") (pinfunction "IO_L11P_T1_SRCC_34_Y4") (pintype "bidirectional"))
    )
    (net (code "5") (name "/DDR_A4") (class "Default")
      (node (ref "U14") (pin "AA1") (pinfunction "IO_L7P_T1_34_AA1") (pintype "bidirectional"))
    )
    (net (code "6") (name "/DDR_A5") (class "Default")
      (node (ref "U14") (pin "AA4") (pinfunction "IO_L11N_T1_SRCC_34_AA4") (pintype "bidirectional"))
    )
    (net (code "7") (name "/DDR_A6") (class "Default")
      (node (ref "U14") (pin "AB1") (pinfunction "IO_L7N_T1_34_AB1") (pintype "bidirectional"))
    )
    (net (code "8") (name "/DDR_A7") (class "Default")
      (node (ref "U14") (pin "Y6") (pinfunction "IO_L18P_T2_34_Y6") (pintype "bidirectional"))
    )
    (net (code "9") (name "/DDR_A8") (class "Default")
      (node (ref "U14") (pin "AB5") (pinfunction "IO_L10N_T1_34_AB5") (pintype "bidirectional"))
    )
    (net (code "10") (name "/DDR_A9") (class "Default")
      (node (ref "U14") (pin "W1") (pinfunction "IO_L5P_T0_34_W1") (pintype "bidirectional"))
    )
    (net (code "11") (name "/DDR_A10") (class "Default")
      (node (ref "U14") (pin "U3") (pinfunction "IO_L6P_T0_34_U3") (pintype "bidirectional"))
    )
    (net (code "12") (name "/DDR_A11") (class "Default")
      (node (ref "U14") (pin "AB2") (pinfunction "IO_L8N_T1_34_AB2") (pintype "bidirectional"))
    )
    (net (code "13") (name "/DDR_A12") (class "Default")
      (node (ref "U14") (pin "AA3") (pinfunction "IO_L9N_T1_DQS_34_AA3") (pintype "bidirectional"))
    )
    (net (code "14") (name "/DDR_A13") (class "Default")
      (node (ref "U14") (pin "W2") (pinfunction "IO_L4P_T0_34_W2") (pintype "bidirectional"))
    )
    (net (code "15") (name "/DDR_A14") (class "Default")
      (node (ref "U14") (pin "W5") (pinfunction "IO_L15N_T2_DQS_34_W5") (pintype "bidirectional"))
    )
    (net (code "16") (name "/DDR_A15") (class "Default")
      (node (ref "U14") (pin "AA5") (pinfunction "IO_L10P_T1_34_AA5") (pintype "bidirectional"))
    )
    (net (code "17") (name "/DDR_BA0") (class "Default")
      (node (ref "U14") (pin "W4") (pinfunction "IO_L12N_T1_MRCC_34_W4") (pintype "bidirectional"))
    )
    (net (code "18") (name "/DDR_BA1") (class "Default")
      (node (ref "U14") (pin "AB3") (pinfunction "IO_L8P_T1_34_AB3") (pintype "bidirectional"))
    )
    (net (code "19") (name "/DDR_BA2") (class "Default")
      (node (ref "U14") (pin "U5") (pinfunction "IO_L14N_T2_SRCC_34_U5") (pintype "bidirectional"))
    )
    (net (code "20") (name "/DDR_CAS") (class "Default")
      (node (ref "U14") (pin "T5") (pinfunction "IO_L14P_T2_SRCC_34_T5") (pintype "bidirectional"))
    )
    (net (code "21") (name "/DDR_CKE") (class "Default")
      (node (ref "U14") (pin "W6") (pinfunction "IO_L15P_T2_DQS_34_W6") (pintype "bidirectional"))
    )
    (net (code "22") (name "/DDR_CLK_N") (class "Default")
      (node (ref "U14") (pin "R2") (pinfunction "IO_L3N_T0_DQS_34_R2") (pintype "bidirectional"))
    )
    (net (code "23") (name "/DDR_CLK_P") (class "Default")
      (node (ref "U14") (pin "R3") (pinfunction "IO_L3P_T0_DQS_34_R3") (pintype "bidirectional"))
    )
    (net (code "24") (name "/DDR_CS") (class "Default")
      (node (ref "U14") (pin "V2") (pinfunction "IO_L2N_T0_34_V2") (pintype "bidirectional"))
    )
    (net (code "25") (name "/DDR_D0") (class "Default")
      (node (ref "U14") (pin "N4") (pinfunction "IO_L19P_T3_35_N4") (pintype "bidirectional"))
    )
    (net (code "26") (name "/DDR_D1") (class "Default")
      (node (ref "U14") (pin "P1") (pinfunction "IO_L20N_T3_35_P1") (pintype "bidirectional"))
    )
    (net (code "27") (name "/DDR_D2") (class "Default")
      (node (ref "U14") (pin "N5") (pinfunction "IO_L24N_T3_35_N5") (pintype "bidirectional"))
    )
    (net (code "28") (name "/DDR_D3") (class "Default")
      (node (ref "U14") (pin "R1") (pinfunction "IO_L20P_T3_35_R1") (pintype "bidirectional"))
    )
    (net (code "29") (name "/DDR_D4") (class "Default")
      (node (ref "U14") (pin "M5") (pinfunction "IO_L23N_T3_35_M5") (pintype "bidirectional"))
    )
    (net (code "30") (name "/DDR_D5") (class "Default")
      (node (ref "U14") (pin "P6") (pinfunction "IO_L24P_T3_35_P6") (pintype "bidirectional"))
    )
    (net (code "31") (name "/DDR_D6") (class "Default")
      (node (ref "U14") (pin "M6") (pinfunction "IO_L23P_T3_35_M6") (pintype "bidirectional"))
    )
    (net (code "32") (name "/DDR_D7") (class "Default")
      (node (ref "U14") (pin "N2") (pinfunction "IO_L22N_T3_35_N2") (pintype "bidirectional"))
    )
    (net (code "33") (name "/DDR_D8") (class "Default")
      (node (ref "U14") (pin "K6") (pinfunction "IO_L17P_T2_35_K6") (pintype "bidirectional"))
    )
    (net (code "34") (name "/DDR_D9") (class "Default")
      (node (ref "U14") (pin "J4") (pinfunction "IO_L13N_T2_MRCC_35_J4") (pintype "bidirectional"))
    )
    (net (code "35") (name "/DDR_D10") (class "Default")
      (node (ref "U14") (pin "L5") (pinfunction "IO_L18P_T2_35_L5") (pintype "bidirectional"))
    )
    (net (code "36") (name "/DDR_D11") (class "Default")
      (node (ref "U14") (pin "K4") (pinfunction "IO_L13P_T2_MRCC_35_K4") (pintype "bidirectional"))
    )
    (net (code "37") (name "/DDR_D12") (class "Default")
      (node (ref "U14") (pin "L3") (pinfunction "IO_L14P_T2_SRCC_35_L3") (pintype "bidirectional"))
    )
    (net (code "38") (name "/DDR_D13") (class "Default")
      (node (ref "U14") (pin "M2") (pinfunction "IO_L16N_T2_35_M2") (pintype "bidirectional"))
    )
    (net (code "39") (name "/DDR_D14") (class "Default")
      (node (ref "U14") (pin "M3") (pinfunction "IO_L16P_T2_35_M3") (pintype "bidirectional"))
    )
    (net (code "40") (name "/DDR_D15") (class "Default")
      (node (ref "U14") (pin "K3") (pinfunction "IO_L14N_T2_SRCC_35_K3") (pintype "bidirectional"))
    )
    (net (code "41") (name "/DDR_D16") (class "Default")
      (node (ref "U14") (pin "B1") (pinfunction "IO_L1P_T0_AD4P_35_B1") (pintype "bidirectional"))
    )
    (net (code "42") (name "/DDR_D17") (class "Default")
      (node (ref "U14") (pin "F1") (pinfunction "IO_L5N_T0_AD13N_35_F1") (pintype "bidirectional"))
    )
    (net (code "43") (name "/DDR_D18") (class "Default")
      (node (ref "U14") (pin "A1") (pinfunction "IO_L1N_T0_AD4N_35_A1") (pintype "bidirectional"))
    )
    (net (code "44") (name "/DDR_D19") (class "Default")
      (node (ref "U14") (pin "E2") (pinfunction "IO_L4P_T0_35_E2") (pintype "bidirectional"))
    )
    (net (code "45") (name "/DDR_D20") (class "Default")
      (node (ref "U14") (pin "D2") (pinfunction "IO_L4N_T0_35_D2") (pintype "bidirectional"))
    )
    (net (code "46") (name "/DDR_D21") (class "Default")
      (node (ref "U14") (pin "G1") (pinfunction "IO_L5P_T0_AD13P_35_G1") (pintype "bidirectional"))
    )
    (net (code "47") (name "/DDR_D22") (class "Default")
      (node (ref "U14") (pin "B2") (pinfunction "IO_L2N_T0_AD12N_35_B2") (pintype "bidirectional"))
    )
    (net (code "48") (name "/DDR_D23") (class "Default")
      (node (ref "U14") (pin "F3") (pinfunction "IO_L6P_T0_35_F3") (pintype "bidirectional"))
    )
    (net (code "49") (name "/DDR_D24") (class "Default")
      (node (ref "U14") (pin "K1") (pinfunction "IO_L7P_T1_AD6P_35_K1") (pintype "bidirectional"))
    )
    (net (code "50") (name "/DDR_D25") (class "Default")
      (node (ref "U14") (pin "J5") (pinfunction "IO_L10P_T1_AD15P_35_J5") (pintype "bidirectional"))
    )
    (net (code "51") (name "/DDR_D26") (class "Default")
      (node (ref "U14") (pin "H2") (pinfunction "IO_L8P_T1_AD14P_35_H2") (pintype "bidirectional"))
    )
    (net (code "52") (name "/DDR_D27") (class "Default")
      (node (ref "U14") (pin "H5") (pinfunction "IO_L10N_T1_AD15N_35_H5") (pintype "bidirectional"))
    )
    (net (code "53") (name "/DDR_D28") (class "Default")
      (node (ref "U14") (pin "G2") (pinfunction "IO_L8N_T1_AD14N_35_G2") (pintype "bidirectional"))
    )
    (net (code "54") (name "/DDR_D29") (class "Default")
      (node (ref "U14") (pin "H4") (pinfunction "IO_L12P_T1_MRCC_35_H4") (pintype "bidirectional"))
    )
    (net (code "55") (name "/DDR_D30") (class "Default")
      (node (ref "U14") (pin "J1") (pinfunction "IO_L7N_T1_AD6N_35_J1") (pintype "bidirectional"))
    )
    (net (code "56") (name "/DDR_D31") (class "Default")
      (node (ref "U14") (pin "H3") (pinfunction "IO_L11P_T1_SRCC_35_H3") (pintype "bidirectional"))
    )
    (net (code "57") (name "/DDR_DQM0") (class "Default")
      (node (ref "U14") (pin "P2") (pinfunction "IO_L22P_T3_35_P2") (pintype "bidirectional"))
    )
    (net (code "58") (name "/DDR_DQM1") (class "Default")
      (node (ref "U14") (pin "J6") (pinfunction "IO_L17N_T2_35_J6") (pintype "bidirectional"))
    )
    (net (code "59") (name "/DDR_DQM2") (class "Default")
      (node (ref "U14") (pin "C2") (pinfunction "IO_L2P_T0_AD12P_35_C2") (pintype "bidirectional"))
    )
    (net (code "60") (name "/DDR_DQM3") (class "Default")
      (node (ref "U14") (pin "G3") (pinfunction "IO_L11N_T1_SRCC_35_G3") (pintype "bidirectional"))
    )
    (net (code "61") (name "/DDR_DQS0_N") (class "Default")
      (node (ref "U14") (pin "P4") (pinfunction "IO_L21N_T3_DQS_35_P4") (pintype "bidirectional"))
    )
    (net (code "62") (name "/DDR_DQS0_P") (class "Default")
      (node (ref "U14") (pin "P5") (pinfunction "IO_L21P_T3_DQS_35_P5") (pintype "bidirectional"))
    )
    (net (code "63") (name "/DDR_DQS1_N") (class "Default")
      (node (ref "U14") (pin "L1") (pinfunction "IO_L15N_T2_DQS_35_L1") (pintype "bidirectional"))
    )
    (net (code "64") (name "/DDR_DQS1_P") (class "Default")
      (node (ref "U14") (pin "M1") (pinfunction "IO_L15P_T2_DQS_35_M1") (pintype "bidirectional"))
    )
    (net (code "65") (name "/DDR_DQS2_N") (class "Default")
      (node (ref "U14") (pin "D1") (pinfunction "IO_L3N_T0_DQS_AD5N_35_D1") (pintype "bidirectional"))
    )
    (net (code "66") (name "/DDR_DQS2_P") (class "Default")
      (node (ref "U14") (pin "E1") (pinfunction "IO_L3P_T0_DQS_AD5P_35_E1") (pintype "bidirectional"))
    )
    (net (code "67") (name "/DDR_DQS3_N") (class "Default")
      (node (ref "U14") (pin "J2") (pinfunction "IO_L9N_T1_DQS_AD7N_35_J2") (pintype "bidirectional"))
    )
    (net (code "68") (name "/DDR_DQS3_P") (class "Default")
      (node (ref "U14") (pin "K2") (pinfunction "IO_L9P_T1_DQS_AD7P_35_K2") (pintype "bidirectional"))
    )
    (net (code "69") (name "/DDR_ODT") (class "Default")
      (node (ref "U14") (pin "U2") (pinfunction "IO_L2P_T0_34_U2") (pintype "bidirectional"))
    )
    (net (code "70") (name "/DDR_RAS") (class "Default")
      (node (ref "U14") (pin "R6") (pinfunction "IO_L17P_T2_34_R6") (pintype "bidirectional"))
    )
    (net (code "71") (name "/DDR_RST") (class "Default")
      (node (ref "U14") (pin "Y8") (pinfunction "IO_L23P_T3_34_Y8") (pintype "bidirectional"))
    )
    (net (code "72") (name "/DDR_WE") (class "Default")
      (node (ref "U14") (pin "U6") (pinfunction "IO_L16P_T2_34_U6") (pintype "bidirectional"))
    )
    (net (code "73") (name "/EECLK") (class "Default")
      (node (ref "R81") (pin "1") (pinfunction "1_1") (pintype "passive"))
      (node (ref "U15") (pin "62") (pinfunction "EECLK_62") (pintype "output"))
      (node (ref "U17") (pin "4") (pinfunction "CLK_4") (pintype "input"))
    )
    (net (code "74") (name "/EECS") (class "Default")
      (node (ref "R80") (pin "1") (pinfunction "1_1") (pintype "passive"))
      (node (ref "U15") (pin "63") (pinfunction "EECS_63") (pintype "bidirectional"))
      (node (ref "U17") (pin "5") (pinfunction "CS_5") (pintype "input"))
    )
    (net (code "75") (name "/EEDATA") (class "Default")
      (node (ref "R79") (pin "1") (pinfunction "1_1") (pintype "passive"))
      (node (ref "R82") (pin "1") (pinfunction "1_1") (pintype "passive"))
      (node (ref "U15") (pin "61") (pinfunction "EEDATA_61") (pintype "bidirectional"))
      (node (ref "U17") (pin "3") (pinfunction "DI_3") (pintype "input"))
    )
    (net (code "76") (name "/FPGA_1V8_CORE") (class "Default")
      (node (ref "C130") (pin "1") (pinfunction "1_1") (pintype "passive"))
      (node (ref "C131") (pin "1") (pinfunction "1_1") (pintype "passive"))
      (node (ref "C132") (pin "1") (pinfunction "1_1") (pintype "passive"))
      (node (ref "C142") (pin "1") (pinfunction "1_1") (pintype "passive"))
      (node (ref "C143") (pin "1") (pinfunction "1_1") (pintype "passive"))
      (node (ref "U15") (pin "12") (pinfunction "VCORE-1_12") (pintype "power_in"))
      (node (ref "U15") (pin "37") (pinfunction "VCORE-2_37") (pintype "power_in"))
      (node (ref "U15") (pin "49") (pinfunction "VREGOUT_49") (pintype "power_in"))
      (node (ref "U15") (pin "64") (pinfunction "VCORE-3_64") (pintype "power_in"))
    )
    (net (code "77") (name "/FPGA_B0") (class "Default")
      (node (ref "U14") (pin "Y19") (pinfunction "IO_L13N_T2_MRCC_14_Y19") (pintype "bidirectional"))
    )
    (net (code "78") (name "/FPGA_B1") (class "Default")
      (node (ref "U14") (pin "Y21") (pinfunction "IO_L9P_T1_DQS_14_Y21") (pintype "bidirectional"))
    )
    (net (code "79") (name "/FPGA_CCLK") (class "Default")
      (node (ref "U14") (pin "L12") (pinfunction "CCLK_0_L12") (pintype "bidirectional"))
      (node (ref "U16") (pin "6") (pinfunction "SCK_6") (pintype "input"))
    )
    (net (code "80") (name "/FPGA_CLK") (class "Default")
      (node (ref "U14") (pin "W19") (pinfunction "IO_L12P_T1_MRCC_14_W19") (pintype "bidirectional"))
      (node (ref "X1") (pin "3") (pinfunction "OUTPUT_3") (pintype "output"))
    )
    (net (code "81") (name "/FPGA_CSO") (class "Default")
      (node (ref "U14") (pin "T19") (pinfunction "IO_L6P_T0_FCS_B_14_T19") (pintype "bidirectional"))
      (node (ref "U16") (pin "1") (pinfunction "CE#_1") (pintype "input"))
    )
    (net (code "82") (name "/FPGA_DONE") (class "Default")
      (node (ref "LED11") (pin "2") (pinfunction "A_2") (pintype "passive"))
      (node (ref "R67") (pin "1") (pinfunction "1_1") (pintype "passive"))
      (node (ref "U14") (pin "G11") (pinfunction "DONE_0_G11") (pintype "bidirectional"))
    )
    (net (code "83") (name "/FPGA_DQ0") (class "Default")
      (node (ref "U14") (pin "P22") (pinfunction "IO_L1P_T0_D00_MOSI_14_P22") (pintype "bidirectional"))
      (node (ref "U16") (pin "5") (pinfunction "SI(IO0)_5") (pintype "bidirectional"))
    )
    (net (code "84") (name "/FPGA_DQ1") (class "Default")
      (node (ref "U14") (pin "R22") (pinfunction "IO_L1N_T0_D01_DIN_14_R22") (pintype "bidirectional"))
      (node (ref "U16") (pin "2") (pinfunction "SO(IO1)_2") (pintype "bidirectional"))
    )
    (net (code "85") (name "/FPGA_DQ2") (class "Default")
      (node (ref "U14") (pin "P21") (pinfunction "IO_L2P_T0_D02_14_P21") (pintype "bidirectional"))
      (node (ref "U16") (pin "3") (pinfunction "WP#(IO2)_3") (pintype "bidirectional"))
    )
    (net (code "86") (name "/FPGA_DQ3") (class "Default")
      (node (ref "U14") (pin "R21") (pinfunction "IO_L2N_T0_D03_14_R21") (pintype "bidirectional"))
      (node (ref "U16") (pin "7") (pinfunction "HOLD#(IO3)_7") (pintype "bidirectional"))
    )
    (net (code "87") (name "/FPGA_FTDI0") (class "Default")
      (node (ref "U14") (pin "V22") (pinfunction "IO_L3N_T0_DQS_EMCCLK_14_V22") (pintype "bidirectional"))
      (node (ref "U15") (pin "40") (pinfunction "BDBUS2_40") (pintype "bidirectional"))
    )
    (net (code "88") (name "/FPGA_FTDI1") (class "Default")
      (node (ref "U14") (pin "AB20") (pinfunction "IO_L15N_T2_DQS_DOUT_CSO_B_14_AB20") (pintype "bidirectional"))
      (node (ref "U15") (pin "41") (pinfunction "BDBUS3_41") (pintype "bidirectional"))
    )
    (net (code "89") (name "/FPGA_FTDI2") (class "Default")
      (node (ref "U14") (pin "AB21") (pinfunction "IO_L10P_T1_D14_14_AB21") (pintype "bidirectional"))
      (node (ref "U15") (pin "43") (pinfunction "BDBUS4_43") (pintype "bidirectional"))
    )
    (net (code "90") (name "/FPGA_FTDI3") (class "Default")
      (node (ref "U14") (pin "AA21") (pinfunction "IO_L8N_T1_D12_14_AA21") (pintype "bidirectional"))
      (node (ref "U15") (pin "44") (pinfunction "BDBUS5_44") (pintype "bidirectional"))
    )
    (net (code "91") (name "/FPGA_FTDI5") (class "Default")
      (node (ref "U14") (pin "AA20") (pinfunction "IO_L8P_T1_D11_14_AA20") (pintype "bidirectional"))
      (node (ref "U15") (pin "46") (pinfunction "BDBUS7_46") (pintype "bidirectional"))
    )
    (net (code "92") (name "/FPGA_FTDI_OSCI") (class "Default")
      (node (ref "U15") (pin "2") (pinfunction "OSCI_2") (pintype "input"))
      (node (ref "X2") (pin "1") (pinfunction "IN_1") (pintype "input"))
    )
    (net (code "93") (name "/FPGA_FTDI_OSCO") (class "Default")
      (node (ref "U15") (pin "3") (pinfunction "OSCO_3") (pintype "output"))
      (node (ref "X2") (pin "3") (pinfunction "OUT_3") (pintype "output"))
    )
    (net (code "94") (name "/FPGA_JTAG_LED") (class "Default")
      (node (ref "LED14") (pin "1") (pinfunction "C_1") (pintype "passive"))
      (node (ref "U15") (pin "29") (pinfunction "ACBUS3_29") (pintype "bidirectional"))
    )
    (net (code "95") (name "/FPGA_LED0") (class "Default")
      (node (ref "U14") (pin "V18") (pinfunction "IO_L14P_T2_SRCC_14_V18") (pintype "bidirectional"))
    )
    (net (code "96") (name "/FPGA_LED1") (class "Default")
      (node (ref "U14") (pin "Y18") (pinfunction "IO_L13P_T2_MRCC_14_Y18") (pintype "bidirectional"))
    )
    (net (code "97") (name "/FPGA_LED2") (class "Default")
      (node (ref "U14") (pin "P19") (pinfunction "IO_L5P_T0_D06_14_P19") (pintype "bidirectional"))
    )
    (net (code "98") (name "/FPGA_LED3") (class "Default")
      (node (ref "U14") (pin "U20") (pinfunction "IO_L11P_T1_SRCC_14_U20") (pintype "bidirectional"))
    )
    (net (code "99") (name "/FPGA_RST") (class "Default")
      (node (ref "C232") (pin "1") (pinfunction "1_1") (pintype "passive"))
      (node (ref "R70") (pin "2") (pinfunction "2_2") (pintype "passive"))
      (node (ref "SW5") (pin "1") (pinfunction "1_1") (pintype "passive"))
      (node (ref "U14") (pin "AB22") (pinfunction "IO_L10N_T1_D15_14_AB22") (pintype "bidirectional"))
    )
    (net (code "100") (name "/FPGA_RX_LED") (class "Default")
      (node (ref "LED12") (pin "1") (pinfunction "C_1") (pintype "passive"))
      (node (ref "U15") (pin "54") (pinfunction "BCBUS3_54") (pintype "bidirectional"))
    )
    (net (code "101") (name "/FPGA_SCL") (class "Default")
      (node (ref "U14") (pin "AB18") (pinfunction "IO_L17N_T2_A13_D29_14_AB18") (pintype "bidirectional"))
    )
    (net (code "102") (name "/FPGA_SDA") (class "Default")
      (node (ref "U14") (pin "AA18") (pinfunction "IO_L17P_T2_A14_D30_14_AA18") (pintype "bidirectional"))
    )
    (net (code "103") (name "/FPGA_TCK0") (class "Default")
      (node (ref "U14") (pin "V12") (pinfunction "TCK_0_V12") (pintype "input"))
      (node (ref "U15") (pin "16") (pinfunction "ADBUS0_16") (pintype "bidirectional"))
    )
    (net (code "104") (name "/FPGA_TDI0") (class "Default")
      (node (ref "U14") (pin "R13") (pinfunction "TDI_0_R13") (pintype "input"))
      (node (ref "U15") (pin "17") (pinfunction "ADBUS1_17") (pintype "bidirectional"))
    )
    (net (code "105") (name "/FPGA_TDO0") (class "Default")
      (node (ref "U14") (pin "U13") (pinfunction "TDO_0_U13") (pintype "output"))
      (node (ref "U15") (pin "18") (pinfunction "ADBUS2_18") (pintype "bidirectional"))
    )
    (net (code "106") (name "/FPGA_TMS0") (class "Default")
      (node (ref "U14") (pin "T13") (pinfunction "TMS_0_T13") (pintype "input"))
      (node (ref "U15") (pin "19") (pinfunction "ADBUS3_19") (pintype "bidirectional"))
    )
    (net (code "107") (name "/FPGA_TX_LED") (class "Default")
      (node (ref "LED13") (pin "1") (pinfunction "C_1") (pintype "passive"))
      (node (ref "U15") (pin "55") (pinfunction "BCBUS4_55") (pintype "bidirectional"))
    )
    (net (code "108") (name "/FPGA_UART0_RX") (class "Default")
      (node (ref "U14") (pin "T21") (pinfunction "IO_L4P_T0_D04_14_T21") (pintype "bidirectional"))
      (node (ref "U15") (pin "38") (pinfunction "BDBUS0_38") (pintype "bidirectional"))
    )
    (net (code "109") (name "/FPGA_UART0_TX") (class "Default")
      (node (ref "U14") (pin "U21") (pinfunction "IO_L4N_T0_D05_14_U21") (pintype "bidirectional"))
      (node (ref "U15") (pin "39") (pinfunction "BDBUS1_39") (pintype "bidirectional"))
    )
    (net (code "110") (name "/FPGA_USB_D_N") (class "Default")
      (node (ref "R75") (pin "1") (pinfunction "1_1") (pintype "passive"))
      (node (ref "U15") (pin "7") (pinfunction "DM_7") (pintype "bidirectional"))
    )
    (net (code "111") (name "/FPGA_USB_D_P") (class "Default")
      (node (ref "R74") (pin "1") (pinfunction "1_1") (pintype "passive"))
      (node (ref "U15") (pin "8") (pinfunction "DP_8") (pintype "bidirectional"))
    )
    (net (code "112") (name "/FPGA_VPHY") (class "Default")
      (node (ref "C140") (pin "1") (pinfunction "1_1") (pintype "passive"))
      (node (ref "C141") (pin "1") (pinfunction "1_1") (pintype "passive"))
      (node (ref "FB5") (pin "1") (pinfunction "1_1") (pintype "passive"))
      (node (ref "U15") (pin "4") (pinfunction "VPHY_4") (pintype "power_in"))
    )
    (net (code "113") (name "/FPGA_VPLL") (class "Default")
      (node (ref "C138") (pin "1") (pinfunction "1_1") (pintype "passive"))
      (node (ref "C139") (pin "1") (pinfunction "1_1") (pintype "passive"))
      (node (ref "FB4") (pin "2") (pinfunction "2_2") (pintype "passive"))
      (node (ref "U15") (pin "9") (pinfunction "VPLL_9") (pintype "power_in"))
    )
    (net (code "114") (name "/PM_00_N") (class "Default")
      (node (ref "U14") (pin "AA16") (pinfunction "IO_L1N_T0_13_AA16") (pintype "bidirectional"))
    )
    (net (code "115") (name "/PM_00_P") (class "Default")
      (node (ref "U14") (pin "Y16") (pinfunction "IO_L1P_T0_13_Y16") (pintype "bidirectional"))
    )
    (net (code "116") (name "/PM_01_N") (class "Default")
      (node (ref "U14") (pin "AB17") (pinfunction "IO_L2N_T0_13_AB17") (pintype "bidirectional"))
    )
    (net (code "117") (name "/PM_01_P") (class "Default")
      (node (ref "U14") (pin "AB16") (pinfunction "IO_L2P_T0_13_AB16") (pintype "bidirectional"))
    )
    (net (code "118") (name "/PM_02_N") (class "Default")
      (node (ref "U14") (pin "AB13") (pinfunction "IO_L3N_T0_DQS_13_AB13") (pintype "bidirectional"))
    )
    (net (code "119") (name "/PM_02_P") (class "Default")
      (node (ref "U14") (pin "AA13") (pinfunction "IO_L3P_T0_DQS_13_AA13") (pintype "bidirectional"))
    )
    (net (code "120") (name "/PM_03_N") (class "Default")
      (node (ref "U14") (pin "AB15") (pinfunction "IO_L4N_T0_13_AB15") (pintype "bidirectional"))
    )
    (net (code "121") (name "/PM_03_P") (class "Default")
      (node (ref "U14") (pin "AA15") (pinfunction "IO_L4P_T0_13_AA15") (pintype "bidirectional"))
    )
    (net (code "122") (name "/PM_10_N") (class "Default")
      (node (ref "U14") (pin "P17") (pinfunction "IO_L21N_T3_DQS_A06_D22_14_P17") (pintype "bidirectional"))
    )
    (net (code "123") (name "/PM_10_P") (class "Default")
      (node (ref "U14") (pin "N17") (pinfunction "IO_L21P_T3_DQS_14_N17") (pintype "bidirectional"))
    )
    (net (code "124") (name "/PM_11_N") (class "Default")
      (node (ref "U14") (pin "R16") (pinfunction "IO_L22N_T3_A04_D20_14_R16") (pintype "bidirectional"))
    )
    (net (code "125") (name "/PM_11_P") (class "Default")
      (node (ref "U14") (pin "P15") (pinfunction "IO_L22P_T3_A05_D21_14_P15") (pintype "bidirectional"))
    )
    (net (code "126") (name "/PM_12_N") (class "Default")
      (node (ref "U14") (pin "N14") (pinfunction "IO_L23N_T3_A02_D18_14_N14") (pintype "bidirectional"))
    )
    (net (code "127") (name "/PM_12_P") (class "Default")
      (node (ref "U14") (pin "N13") (pinfunction "IO_L23P_T3_A03_D19_14_N13") (pintype "bidirectional"))
    )
    (net (code "128") (name "/PM_13_N") (class "Default")
      (node (ref "U14") (pin "R17") (pinfunction "IO_L24N_T3_A00_D16_14_R17") (pintype "bidirectional"))
    )
    (net (code "129") (name "/PM_13_P") (class "Default")
      (node (ref "U14") (pin "P16") (pinfunction "IO_L24P_T3_A01_D17_14_P16") (pintype "bidirectional"))
    )
    (net (code "130") (name "/PUDC_B") (class "Default")
      (node (ref "R63") (pin "1") (pinfunction "1_1") (pintype "passive"))
      (node (ref "U14") (pin "U22") (pinfunction "IO_L3P_T0_DQS_PUDC_B_14_U22") (pintype "bidirectional"))
    )
    (net (code "131") (name "/RESETn_3V3") (class "Default")
      (node (ref "U14") (pin "V19") (pinfunction "IO_L14N_T2_SRCC_14_V19") (pintype "bidirectional"))
    )
    (net (code "132") (name "/SD_CD") (class "Default")
      (node (ref "U14") (pin "AB12") (pinfunction "IO_L7N_T1_13_AB12") (pintype "bidirectional"))
    )
    (net (code "133") (name "/SD_CLK") (class "Default")
      (node (ref "U14") (pin "W16") (pinfunction "IO_L16N_T2_13_W16") (pintype "bidirectional"))
    )
    (net (code "134") (name "/SD_CMD") (class "Default")
      (node (ref "U14") (pin "W15") (pinfunction "IO_L16P_T2_13_W15") (pintype "bidirectional"))
    )
    (net (code "135") (name "/SD_D0") (class "Default")
      (node (ref "U14") (pin "AB11") (pinfunction "IO_L7P_T1_13_AB11") (pintype "bidirectional"))
    )
    (net (code "136") (name "/SD_D1") (class "Default")
      (node (ref "U14") (pin "AA11") (pinfunction "IO_L9N_T1_DQS_13_AA11") (pintype "bidirectional"))
    )
    (net (code "137") (name "/SD_D2") (class "Default")
      (node (ref "U14") (pin "Y12") (pinfunction "IO_L11N_T1_SRCC_13_Y12") (pintype "bidirectional"))
    )
    (net (code "138") (name "/SD_D3") (class "Default")
      (node (ref "U14") (pin "Y14") (pinfunction "IO_L6N_T0_VREF_13_Y14") (pintype "bidirectional"))
    )
    (net (code "139") (name "/SOC_TL0") (class "Default")
      (node (ref "U14") (pin "F13") (pinfunction "IO_L1P_T0_16_F13") (pintype "bidirectional"))
    )
    (net (code "140") (name "/SOC_TL1") (class "Default")
      (node (ref "U14") (pin "M13") (pinfunction "IO_L20P_T3_A20_15_M13") (pintype "bidirectional"))
    )
    (net (code "141") (name "/SOC_TL2") (class "Default")
      (node (ref "U14") (pin "E14") (pinfunction "IO_L4N_T0_16_E14") (pintype "bidirectional"))
    )
    (net (code "142") (name "/SOC_TL3") (class "Default")
      (node (ref "U14") (pin "L13") (pinfunction "IO_L20N_T3_A19_15_L13") (pintype "bidirectional"))
    )
    (net (code "143") (name "/SOC_TL4") (class "Default")
      (node (ref "U14") (pin "C13") (pinfunction "IO_L8P_T1_16_C13") (pintype "bidirectional"))
    )
    (net (code "144") (name "/SOC_TL5") (class "Default")
      (node (ref "U14") (pin "K13") (pinfunction "IO_L19P_T3_A22_15_K13") (pintype "bidirectional"))
    )
    (net (code "145") (name "/SOC_TL6") (class "Default")
      (node (ref "U14") (pin "A13") (pinfunction "IO_L10P_T1_16_A13") (pintype "bidirectional"))
    )
    (net (code "146") (name "/SOC_TL7") (class "Default")
      (node (ref "U14") (pin "H13") (pinfunction "IO_L1P_T0_AD0P_15_H13") (pintype "bidirectional"))
    )
    (net (code "147") (name "/SOC_TL8") (class "Default")
      (node (ref "U14") (pin "A15") (pinfunction "IO_L9P_T1_DQS_16_A15") (pintype "bidirectional"))
    )
    (net (code "148") (name "/SOC_TL9") (class "Default")
      (node (ref "U14") (pin "G13") (pinfunction "IO_L1N_T0_AD0N_15_G13") (pintype "bidirectional"))
    )
    (net (code "149") (name "/SOC_TL10") (class "Default")
      (node (ref "U14") (pin "A16") (pinfunction "IO_L9N_T1_DQS_16_A16") (pintype "bidirectional"))
    )
    (net (code "150") (name "/SOC_TL11") (class "Default")
      (node (ref "U14") (pin "E13") (pinfunction "IO_L4P_T0_16_E13") (pintype "bidirectional"))
    )
    (net (code "151") (name "/SOC_TL12") (class "Default")
      (node (ref "U14") (pin "M15") (pinfunction "IO_L24P_T3_RS1_15_M15") (pintype "bidirectional"))
    )
    (net (code "152") (name "/SOC_TL13") (class "Default")
      (node (ref "U14") (pin "D14") (pinfunction "IO_L6P_T0_16_D14") (pintype "bidirectional"))
    )
    (net (code "153") (name "/SOC_TL14") (class "Default")
      (node (ref "U14") (pin "L14") (pinfunction "IO_L22P_T3_A17_15_L14") (pintype "bidirectional"))
    )
    (net (code "154") (name "/SOC_TL15") (class "Default")
      (node (ref "U14") (pin "B13") (pinfunction "IO_L8N_T1_16_B13") (pintype "bidirectional"))
    )
    (net (code "155") (name "/SOC_TL16") (class "Default")
      (node (ref "U14") (pin "L15") (pinfunction "IO_L22N_T3_A16_15_L15") (pintype "bidirectional"))
    )
    (net (code "156") (name "/SOC_TL17") (class "Default")
      (node (ref "U14") (pin "A14") (pinfunction "IO_L10N_T1_16_A14") (pintype "bidirectional"))
    )
    (net (code "157") (name "/SOC_TL18") (class "Default")
      (node (ref "U14") (pin "J14") (pinfunction "IO_L3P_T0_DQS_AD1P_15_J14") (pintype "bidirectional"))
    )
    (net (code "158") (name "/SOC_TL19") (class "Default")
      (node (ref "U14") (pin "M16") (pinfunction "IO_L24N_T3_RS0_15_M16") (pintype "bidirectional"))
    )
    (net (code "159") (name "/SOC_TL20") (class "Default")
      (node (ref "U14") (pin "L16") (pinfunction "IO_L23P_T3_FOE_B_15_L16") (pintype "bidirectional"))
    )
    (net (code "160") (name "/SOC_TL21") (class "Default")
      (node (ref "U14") (pin "N19") (pinfunction "IO_L17N_T2_A25_15_N19") (pintype "bidirectional"))
    )
    (net (code "161") (name "/SOC_TL22") (class "Default")
      (node (ref "U14") (pin "K16") (pinfunction "IO_L23N_T3_FWE_B_15_K16") (pintype "bidirectional"))
    )
    (net (code "162") (name "/SOC_TL23") (class "Default")
      (node (ref "U14") (pin "N18") (pinfunction "IO_L17P_T2_A26_15_N18") (pintype "bidirectional"))
    )
    (net (code "163") (name "/SOC_TL24") (class "Default")
      (node (ref "U14") (pin "G16") (pinfunction "IO_L2N_T0_AD8N_15_G16") (pintype "bidirectional"))
    )
    (net (code "164") (name "/SOC_TL25") (class "Default")
      (node (ref "U14") (pin "N20") (pinfunction "IO_L18P_T2_A24_15_N20") (pintype "bidirectional"))
    )
    (net (code "165") (name "/SOC_TL26") (class "Default")
      (node (ref "U14") (pin "F14") (pinfunction "IO_L1N_T0_16_F14") (pintype "bidirectional"))
    )
    (net (code "166") (name "/SOC_TL27") (class "Default")
      (node (ref "U14") (pin "J15") (pinfunction "IO_L5P_T0_AD9P_15_J15") (pintype "bidirectional"))
    )
    (net (code "167") (name "/SOC_TL28") (class "Default")
      (node (ref "U14") (pin "G17") (pinfunction "IO_L4P_T0_15_G17") (pintype "bidirectional"))
    )
    (net (code "168") (name "/SOC_TL29") (class "Default")
      (node (ref "U14") (pin "H14") (pinfunction "IO_L3N_T0_DQS_AD1N_15_H14") (pintype "bidirectional"))
    )
    (net (code "169") (name "/SOC_TL30") (class "Default")
      (node (ref "U14") (pin "F16") (pinfunction "IO_L2P_T0_16_F16") (pintype "bidirectional"))
    )
    (net (code "170") (name "/SOC_TL31") (class "Default")
      (node (ref "U14") (pin "H15") (pinfunction "IO_L5N_T0_AD9N_15_H15") (pintype "bidirectional"))
    )
    (net (code "171") (name "/SOC_TL32") (class "Default")
      (node (ref "U14") (pin "G18") (pinfunction "IO_L4N_T0_15_G18") (pintype "bidirectional"))
    )
    (net (code "172") (name "/SOC_TL33") (class "Default")
      (node (ref "U14") (pin "G15") (pinfunction "IO_L2P_T0_AD8P_15_G15") (pintype "bidirectional"))
    )
    (net (code "173") (name "/SOC_TL34") (class "Default")
      (node (ref "U14") (pin "B15") (pinfunction "IO_L7P_T1_16_B15") (pintype "bidirectional"))
    )
    (net (code "174") (name "/SOC_TL35") (class "Default")
      (node (ref "U14") (pin "K17") (pinfunction "IO_L21P_T3_DQS_15_K17") (pintype "bidirectional"))
    )
    (net (code "175") (name "/SOC_TL36") (class "Default")
      (node (ref "U14") (pin "B17") (pinfunction "IO_L11P_T1_SRCC_16_B17") (pintype "bidirectional"))
    )
    (net (code "176") (name "/SOC_TL37") (class "Default")
      (node (ref "U14") (pin "J17") (pinfunction "IO_L21N_T3_DQS_A18_15_J17") (pintype "bidirectional"))
    )
    (net (code "177") (name "/SOC_TL38") (class "Default")
      (node (ref "U14") (pin "A18") (pinfunction "IO_L17P_T2_16_A18") (pintype "bidirectional"))
    )
    (net (code "178") (name "/SOC_TL39") (class "Default")
      (node (ref "U14") (pin "H17") (pinfunction "IO_L6P_T0_15_H17") (pintype "bidirectional"))
    )
    (net (code "179") (name "/SOC_TL40") (class "Default")
      (node (ref "U14") (pin "B18") (pinfunction "IO_L11N_T1_SRCC_16_B18") (pintype "bidirectional"))
    )
    (net (code "180") (name "/SOC_TL41") (class "Default")
      (node (ref "U14") (pin "J20") (pinfunction "IO_L11P_T1_SRCC_15_J20") (pintype "bidirectional"))
    )
    (net (code "181") (name "/SOC_TL42") (class "Default")
      (node (ref "U14") (pin "A19") (pinfunction "IO_L17N_T2_16_A19") (pintype "bidirectional"))
    )
    (net (code "182") (name "/SOC_TL43") (class "Default")
      (node (ref "U14") (pin "J19") (pinfunction "IO_L12P_T1_MRCC_15_J19") (pintype "bidirectional"))
    )
    (net (code "183") (name "/SOC_TL44") (class "Default")
      (node (ref "U14") (pin "B20") (pinfunction "IO_L16P_T2_16_B20") (pintype "bidirectional"))
    )
    (net (code "184") (name "/SOC_TL45") (class "Default")
      (node (ref "U14") (pin "F20") (pinfunction "IO_L18N_T2_16_F20") (pintype "bidirectional"))
    )
    (net (code "185") (name "/SOC_TL46") (class "Default")
      (node (ref "U14") (pin "A20") (pinfunction "IO_L16N_T2_16_A20") (pintype "bidirectional"))
    )
    (net (code "186") (name "/SOC_TL47") (class "Default")
      (node (ref "U14") (pin "K19") (pinfunction "IO_L13N_T2_MRCC_15_K19") (pintype "bidirectional"))
    )
    (net (code "187") (name "/SOC_TL48") (class "Default")
      (node (ref "U14") (pin "B21") (pinfunction "IO_L21P_T3_DQS_16_B21") (pintype "bidirectional"))
    )
    (net (code "188") (name "/SOC_TL49") (class "Default")
      (node (ref "U14") (pin "E16") (pinfunction "IO_L5P_T0_16_E16") (pintype "bidirectional"))
    )
    (net (code "189") (name "/SOC_TL50") (class "Default")
      (node (ref "U14") (pin "A21") (pinfunction "IO_L21N_T3_DQS_16_A21") (pintype "bidirectional"))
    )
    (net (code "190") (name "/SOC_TL51") (class "Default")
      (node (ref "U14") (pin "E17") (pinfunction "IO_L2N_T0_16_E17") (pintype "bidirectional"))
    )
    (net (code "191") (name "/SOC_TL52") (class "Default")
      (node (ref "U14") (pin "D20") (pinfunction "IO_L19P_T3_16_D20") (pintype "bidirectional"))
    )
    (net (code "192") (name "/SOC_TL53") (class "Default")
      (node (ref "U14") (pin "E18") (pinfunction "IO_L15N_T2_DQS_16_E18") (pintype "bidirectional"))
    )
    (net (code "193") (name "/SOC_TL54") (class "Default")
      (node (ref "U14") (pin "B22") (pinfunction "IO_L20N_T3_16_B22") (pintype "bidirectional"))
    )
    (net (code "194") (name "/SOC_TL55") (class "Default")
      (node (ref "U14") (pin "L18") (pinfunction "IO_L16N_T2_A27_15_L18") (pintype "bidirectional"))
    )
    (net (code "195") (name "/SOC_TL56") (class "Default")
      (node (ref "U14") (pin "C22") (pinfunction "IO_L20P_T3_16_C22") (pintype "bidirectional"))
    )
    (net (code "196") (name "/SOC_TL57") (class "Default")
      (node (ref "U14") (pin "L19") (pinfunction "IO_L14P_T2_SRCC_15_L19") (pintype "bidirectional"))
    )
    (net (code "197") (name "/SOC_TL58") (class "Default")
      (node (ref "U14") (pin "E22") (pinfunction "IO_L22P_T3_16_E22") (pintype "bidirectional"))
    )
    (net (code "198") (name "/SOC_TL59") (class "Default")
      (node (ref "U14") (pin "K18") (pinfunction "IO_L13P_T2_MRCC_15_K18") (pintype "bidirectional"))
    )
    (net (code "199") (name "/SOC_TL60") (class "Default")
      (node (ref "U14") (pin "E19") (pinfunction "IO_L14P_T2_SRCC_16_E19") (pintype "bidirectional"))
    )
    (net (code "200") (name "/SOC_TL61") (class "Default")
      (node (ref "U14") (pin "L20") (pinfunction "IO_L14N_T2_SRCC_15_L20") (pintype "bidirectional"))
    )
    (net (code "201") (name "/SOC_TL62") (class "Default")
      (node (ref "U14") (pin "F19") (pinfunction "IO_L18P_T2_16_F19") (pintype "bidirectional"))
    )
    (net (code "202") (name "/SOC_TL63") (class "Default")
      (node (ref "U14") (pin "M20") (pinfunction "IO_L18N_T2_A23_15_M20") (pintype "bidirectional"))
    )
    (net (code "203") (name "/SOC_TL64") (class "Default")
      (node (ref "U14") (pin "G20") (pinfunction "IO_L8N_T1_AD10N_15_G20") (pintype "bidirectional"))
    )
    (net (code "204") (name "/SOC_TL65") (class "Default")
      (node (ref "U14") (pin "H22") (pinfunction "IO_L7N_T1_AD2N_15_H22") (pintype "bidirectional"))
    )
    (net (code "205") (name "/SOC_TL66") (class "Default")
      (node (ref "U14") (pin "G21") (pinfunction "IO_L24P_T3_16_G21") (pintype "bidirectional"))
    )
    (net (code "206") (name "/SOC_TL67") (class "Default")
      (node (ref "U14") (pin "J21") (pinfunction "IO_L11N_T1_SRCC_15_J21") (pintype "bidirectional"))
    )
    (net (code "207") (name "/SOC_TL68") (class "Default")
      (node (ref "U14") (pin "H20") (pinfunction "IO_L8P_T1_AD10P_15_H20") (pintype "bidirectional"))
    )
    (net (code "208") (name "/SOC_TL69") (class "Default")
      (node (ref "U14") (pin "J22") (pinfunction "IO_L7P_T1_AD2P_15_J22") (pintype "bidirectional"))
    )
    (net (code "209") (name "/SOC_TL70") (class "Default")
      (node (ref "U14") (pin "H19") (pinfunction "IO_L12N_T1_MRCC_15_H19") (pintype "bidirectional"))
    )
    (net (code "210") (name "/SOC_TL71") (class "Default")
      (node (ref "U14") (pin "D21") (pinfunction "IO_L23N_T3_16_D21") (pintype "bidirectional"))
    )
    (net (code "211") (name "/SOC_TL72") (class "Default")
      (node (ref "U14") (pin "K21") (pinfunction "IO_L9P_T1_DQS_AD3P_15_K21") (pintype "bidirectional"))
    )
    (net (code "212") (name "/SOC_TL73") (class "Default")
      (node (ref "U14") (pin "C19") (pinfunction "IO_L13N_T2_MRCC_16_C19") (pintype "bidirectional"))
    )
    (net (code "213") (name "/SOC_TL74") (class "Default")
      (node (ref "U14") (pin "N22") (pinfunction "IO_L15P_T2_DQS_15_N22") (pintype "bidirectional"))
    )
    (net (code "214") (name "/SOC_TL75") (class "Default")
      (node (ref "U14") (pin "M18") (pinfunction "IO_L16P_T2_A28_15_M18") (pintype "bidirectional"))
    )
    (net (code "215") (name "/SOC_TL76") (class "Default")
      (node (ref "U14") (pin "C14") (pinfunction "IO_L3P_T0_DQS_16_C14") (pintype "bidirectional"))
    )
    (net (code "216") (name "/SOC_TL77") (class "Default")
      (node (ref "U14") (pin "M22") (pinfunction "IO_L15N_T2_DQS_ADV_B_15_M22") (pintype "bidirectional"))
    )
    (net (code "217") (name "/SOC_TL78") (class "Default")
      (node (ref "U14") (pin "C15") (pinfunction "IO_L3N_T0_DQS_16_C15") (pintype "bidirectional"))
    )
    (net (code "218") (name "/SOC_TL79") (class "Default")
      (node (ref "U14") (pin "M21") (pinfunction "IO_L10P_T1_AD11P_15_M21") (pintype "bidirectional"))
    )
    (net (code "219") (name "/SOC_TL80") (class "Default")
      (node (ref "U14") (pin "L21") (pinfunction "IO_L10N_T1_AD11N_15_L21") (pintype "bidirectional"))
    )
    (net (code "220") (name "/SOC_TL81") (class "Default")
      (node (ref "U14") (pin "D16") (pinfunction "IO_L5N_T0_16_D16") (pintype "bidirectional"))
    )
    (net (code "221") (name "/SOC_TL82") (class "Default")
      (node (ref "U14") (pin "K22") (pinfunction "IO_L9N_T1_DQS_AD3N_15_K22") (pintype "bidirectional"))
    )
    (net (code "222") (name "/SOC_TL83") (class "Default")
      (node (ref "U14") (pin "D17") (pinfunction "IO_L12P_T1_MRCC_16_D17") (pintype "bidirectional"))
    )
    (net (code "223") (name "/SOC_TL84") (class "Default")
      (node (ref "U14") (pin "B16") (pinfunction "IO_L7N_T1_16_B16") (pintype "bidirectional"))
    )
    (net (code "224") (name "/SOC_TL85") (class "Default")
      (node (ref "U14") (pin "F18") (pinfunction "IO_L15P_T2_DQS_16_F18") (pintype "bidirectional"))
    )
    (net (code "225") (name "/SOC_TL86") (class "Default")
      (node (ref "U14") (pin "C17") (pinfunction "IO_L12N_T1_MRCC_16_C17") (pintype "bidirectional"))
    )
    (net (code "226") (name "/SOC_TL87") (class "Default")
      (node (ref "U14") (pin "D22") (pinfunction "IO_L22N_T3_16_D22") (pintype "bidirectional"))
    )
    (net (code "227") (name "/SOC_TL88") (class "Default")
      (node (ref "U14") (pin "C18") (pinfunction "IO_L13P_T2_MRCC_16_C18") (pintype "bidirectional"))
    )
    (net (code "228") (name "/SOC_TL89") (class "Default")
      (node (ref "U14") (pin "D19") (pinfunction "IO_L14N_T2_SRCC_16_D19") (pintype "bidirectional"))
    )
    (net (code "229") (name "1V0") (class "Default")
      (node (ref "C100") (pin "1") (pinfunction "1_1") (pintype "passive"))
      (node (ref "C101") (pin "1") (pinfunction "1_1") (pintype "passive"))
      (node (ref "C102") (pin "1") (pinfunction "1_1") (pintype "passive"))
      (node (ref "C103") (pin "1") (pinfunction "1_1") (pintype "passive"))
      (node (ref "C104") (pin "2") (pinfunction "2_2") (pintype "passive"))
      (node (ref "C105") (pin "1") (pinfunction "1_1") (pintype "passive"))
      (node (ref "C106") (pin "1") (pinfunction "1_1") (pintype "passive"))
      (node (ref "C107") (pin "1") (pinfunction "1_1") (pintype "passive"))
      (node (ref "C108") (pin "2") (pinfunction "2_2") (pintype "passive"))
      (node (ref "C109") (pin "2") (pinfunction "2_2") (pintype "passive"))
      (node (ref "C110") (pin "1") (pinfunction "1_1") (pintype "passive"))
      (node (ref "C111") (pin "1") (pinfunction "1_1") (pintype "passive"))
      (node (ref "C112") (pin "1") (pinfunction "1_1") (pintype "passive"))
      (node (ref "C113") (pin "1") (pinfunction "1_1") (pintype "passive"))
      (node (ref "C114") (pin "1") (pinfunction "1_1") (pintype "passive"))
      (node (ref "C115") (pin "1") (pinfunction "1_1") (pintype "passive"))
      (node (ref "C116") (pin "1") (pinfunction "1_1") (pintype "passive"))
      (node (ref "C117") (pin "2") (pinfunction "2_2") (pintype "passive"))
      (node (ref "C118") (pin "1") (pinfunction "1_1") (pintype "passive"))
      (node (ref "C127") (pin "1") (pinfunction "1_1") (pintype "passive"))
      (node (ref "C128") (pin "1") (pinfunction "1_1") (pintype "passive"))
      (node (ref "C129") (pin "1") (pinfunction "1_1") (pintype "passive"))
      (node (ref "C218") (pin "1") (pinfunction "1_1") (pintype "passive"))
      (node (ref "C219") (pin "2") (pinfunction "2_2") (pintype "passive"))
      (node (ref "C222") (pin "1") (pinfunction "1_1") (pintype "passive"))
      (node (ref "C223") (pin "1") (pinfunction "1_1") (pintype "passive"))
      (node (ref "C229") (pin "1") (pinfunction "1_1") (pintype "passive"))
      (node (ref "C230") (pin "1") (pinfunction "1_1") (pintype "passive"))
      (node (ref "C231") (pin "1") (pinfunction "1_1") (pintype "passive"))
      (node (ref "C38") (pin "1") (pinfunction "1_1") (pintype "passive"))
      (node (ref "C43") (pin "1") (pinfunction "1_1") (pintype "passive"))
      (node (ref "C44") (pin "1") (pinfunction "1_1") (pintype "passive"))
      (node (ref "C45") (pin "1") (pinfunction "1_1") (pintype "passive"))
      (node (ref "C46") (pin "2") (pinfunction "2_2") (pintype "passive"))
      (node (ref "C47") (pin "2") (pinfunction "2_2") (pintype "passive"))
      (node (ref "C48") (pin "2") (pinfunction "2_2") (pintype "passive"))
      (node (ref "C49") (pin "1") (pinfunction "1_1") (pintype "passive"))
      (node (ref "C50") (pin "2") (pinfunction "2_2") (pintype "passive"))
      (node (ref "C79") (pin "1") (pinfunction "1_1") (pintype "passive"))
      (node (ref "C94") (pin "1") (pinfunction "1_1") (pintype "passive"))
      (node (ref "C95") (pin "1") (pinfunction "1_1") (pintype "passive"))
      (node (ref "C96") (pin "1") (pinfunction "1_1") (pintype "passive"))
      (node (ref "C97") (pin "1") (pinfunction "1_1") (pintype "passive"))
      (node (ref "C98") (pin "1") (pinfunction "1_1") (pintype "passive"))
      (node (ref "C99") (pin "1") (pinfunction "1_1") (pintype "passive"))
      (node (ref "U14") (pin "H10") (pinfunction "VCCINT_H10") (pintype "power_in"))
      (node (ref "U14") (pin "H8") (pinfunction "VCCINT_H8") (pintype "power_in"))
      (node (ref "U14") (pin "J11") (pinfunction "VCCBRAM_J11") (pintype "power_in"))
      (node (ref "U14") (pin "J7") (pinfunction "VCCINT_J7") (pintype "power_in"))
      (node (ref "U14") (pin "J9") (pinfunction "VCCINT_J9") (pintype "power_in"))
      (node (ref "U14") (pin "K8") (pinfunction "VCCINT_K8") (pintype "power_in"))
      (node (ref "U14") (pin "L11") (pinfunction "VCCBRAM_L11") (pintype "power_in"))
      (node (ref "U14") (pin "L7") (pinfunction "VCCINT_L7") (pintype "power_in"))
      (node (ref "U14") (pin "M8") (pinfunction "VCCINT_M8") (pintype "power_in"))
      (node (ref "U14") (pin "N11") (pinfunction "VCCBRAM_N11") (pintype "power_in"))
      (node (ref "U14") (pin "N7") (pinfunction "VCCINT_N7") (pintype "power_in"))
      (node (ref "U14") (pin "P10") (pinfunction "VCCINT_P10") (pintype "power_in"))
      (node (ref "U14") (pin "P8") (pinfunction "VCCINT_P8") (pintype "power_in"))
      (node (ref "U14") (pin "R7") (pinfunction "VCCINT_R7") (pintype "power_in"))
      (node (ref "U14") (pin "R9") (pinfunction "VCCINT_R9") (pintype "power_in"))
      (node (ref "U14") (pin "T10") (pinfunction "VCCINT_T10") (pintype "power_in"))
      (node (ref "U14") (pin "T8") (pinfunction "VCCINT_T8") (pintype "power_in"))
    )
    (net (code "230") (name "1V8") (class "Default")
      (node (ref "C119") (pin "1") (pinfunction "1_1") (pintype "passive"))
      (node (ref "C120") (pin "1") (pinfunction "1_1") (pintype "passive"))
      (node (ref "C121") (pin "1") (pinfunction "1_1") (pintype "passive"))
      (node (ref "C122") (pin "1") (pinfunction "1_1") (pintype "passive"))
      (node (ref "C123") (pin "1") (pinfunction "1_1") (pintype "passive"))
      (node (ref "C124") (pin "1") (pinfunction "1_1") (pintype "passive"))
      (node (ref "C125") (pin "1") (pinfunction "1_1") (pintype "passive"))
      (node (ref "C126") (pin "1") (pinfunction "1_1") (pintype "passive"))
      (node (ref "U14") (pin "E12") (pinfunction "VCCBATT_0_E12") (pintype "power_in"))
      (node (ref "U14") (pin "H12") (pinfunction "VCCAUX_H12") (pintype "power_in"))
      (node (ref "U14") (pin "K10") (pinfunction "VCCADC_0_K10") (pintype "power_in"))
      (node (ref "U14") (pin "K12") (pinfunction "VCCAUX_K12") (pintype "power_in"))
      (node (ref "U14") (pin "M12") (pinfunction "VCCAUX_M12") (pintype "power_in"))
      (node (ref "U14") (pin "P12") (pinfunction "VCCAUX_P12") (pintype "power_in"))
      (node (ref "U14") (pin "R11") (pinfunction "VCCAUX_R11") (pintype "power_in"))
    )
    (net (code "231") (name "1V35") (class "Default")
      (node (ref "C80") (pin "1") (pinfunction "1_1") (pintype "passive"))
      (node (ref "C81") (pin "1") (pinfunction "1_1") (pintype "passive"))
      (node (ref "C82") (pin "1") (pinfunction "1_1") (pintype "passive"))
      (node (ref "C83") (pin "1") (pinfunction "1_1") (pintype "passive"))
      (node (ref "C84") (pin "1") (pinfunction "1_1") (pintype "passive"))
      (node (ref "C85") (pin "1") (pinfunction "1_1") (pintype "passive"))
      (node (ref "C86") (pin "1") (pinfunction "1_1") (pintype "passive"))
      (node (ref "C87") (pin "1") (pinfunction "1_1") (pintype "passive"))
      (node (ref "C88") (pin "1") (pinfunction "1_1") (pintype "passive"))
      (node (ref "C89") (pin "1") (pinfunction "1_1") (pintype "passive"))
      (node (ref "C90") (pin "1") (pinfunction "1_1") (pintype "passive"))
      (node (ref "C91") (pin "1") (pinfunction "1_1") (pintype "passive"))
      (node (ref "C92") (pin "1") (pinfunction "1_1") (pintype "passive"))
      (node (ref "C93") (pin "1") (pinfunction "1_1") (pintype "passive"))
      (node (ref "U14") (pin "AA7") (pinfunction "VCCO_34_AA7") (pintype "power_in"))
      (node (ref "U14") (pin "AB4") (pinfunction "VCCO_34_AB4") (pintype "power_in"))
      (node (ref "U14") (pin "C1") (pinfunction "VCCO_35_C1") (pintype "power_in"))
      (node (ref "U14") (pin "F2") (pinfunction "VCCO_35_F2") (pintype "power_in"))
      (node (ref "U14") (pin "H6") (pinfunction "VCCO_35_H6") (pintype "power_in"))
      (node (ref "U14") (pin "J3") (pinfunction "VCCO_35_J3") (pintype "power_in"))
      (node (ref "U14") (pin "M4") (pinfunction "VCCO_35_M4") (pintype "power_in"))
      (node (ref "U14") (pin "N1") (pinfunction "VCCO_35_N1") (pintype "power_in"))
      (node (ref "U14") (pin "R5") (pinfunction "VCCO_34_R5") (pintype "power_in"))
      (node (ref "U14") (pin "T2") (pinfunction "VCCO_34_T2") (pintype "power_in"))
      (node (ref "U14") (pin "V6") (pinfunction "VCCO_34_V6") (pintype "power_in"))
      (node (ref "U14") (pin "W3") (pinfunction "VCCO_34_W3") (pintype "power_in"))
    )
    (net (code "232") (name "3V3") (class "Default")
      (node (ref "C133") (pin "1") (pinfunction "1_1") (pintype "passive"))
      (node (ref "C134") (pin "1") (pinfunction "1_1") (pintype "passive"))
      (node (ref "C135") (pin "1") (pinfunction "1_1") (pintype "passive"))
      (node (ref "C136") (pin "1") (pinfunction "1_1") (pintype "passive"))
      (node (ref "C137") (pin "1") (pinfunction "1_1") (pintype "passive"))
      (node (ref "C144") (pin "1") (pinfunction "1_1") (pintype "passive"))
      (node (ref "C145") (pin "1") (pinfunction "1_1") (pintype "passive"))
      (node (ref "C146") (pin "1") (pinfunction "1_1") (pintype "passive"))
      (node (ref "C147") (pin "2") (pinfunction "2_2") (pintype "passive"))
      (node (ref "C51") (pin "1") (pinfunction "1_1") (pintype "passive"))
      (node (ref "C52") (pin "1") (pinfunction "1_1") (pintype "passive"))
      (node (ref "C53") (pin "1") (pinfunction "1_1") (pintype "passive"))
      (node (ref "C54") (pin "1") (pinfunction "1_1") (pintype "passive"))
      (node (ref "C55") (pin "1") (pinfunction "1_1") (pintype "passive"))
      (node (ref "C56") (pin "1") (pinfunction "1_1") (pintype "passive"))
      (node (ref "C57") (pin "1") (pinfunction "1_1") (pintype "passive"))
      (node (ref "C58") (pin "1") (pinfunction "1_1") (pintype "passive"))
      (node (ref "C59") (pin "1") (pinfunction "1_1") (pintype "passive"))
      (node (ref "C60") (pin "1") (pinfunction "1_1") (pintype "passive"))
      (node (ref "C61") (pin "1") (pinfunction "1_1") (pintype "passive"))
      (node (ref "C62") (pin "1") (pinfunction "1_1") (pintype "passive"))
      (node (ref "C63") (pin "1") (pinfunction "1_1") (pintype "passive"))
      (node (ref "C64") (pin "1") (pinfunction "1_1") (pintype "passive"))
      (node (ref "FB4") (pin "1") (pinfunction "1_1") (pintype "passive"))
      (node (ref "FB5") (pin "2") (pinfunction "2_2") (pintype "passive"))
      (node (ref "R64") (pin "1") (pinfunction "1_1") (pintype "passive"))
      (node (ref "R65") (pin "1") (pinfunction "1_1") (pintype "passive"))
      (node (ref "R66") (pin "1") (pinfunction "1_1") (pintype "passive"))
      (node (ref "R67") (pin "2") (pinfunction "2_2") (pintype "passive"))
      (node (ref "R68") (pin "2") (pinfunction "2_2") (pintype "passive"))
      (node (ref "R76") (pin "2") (pinfunction "2_2") (pintype "passive"))
      (node (ref "R77") (pin "2") (pinfunction "2_2") (pintype "passive"))
      (node (ref "R78") (pin "2") (pinfunction "2_2") (pintype "passive"))
      (node (ref "R79") (pin "2") (pinfunction "2_2") (pintype "passive"))
      (node (ref "R80") (pin "2") (pinfunction "2_2") (pintype "passive"))
      (node (ref "R81") (pin "2") (pinfunction "2_2") (pintype "passive"))
      (node (ref "SW5") (pin "2") (pinfunction "2_2") (pintype "passive"))
      (node (ref "U14") (pin "AA17") (pinfunction "VCCO_13_AA17") (pintype "power_in"))
      (node (ref "U14") (pin "AB14") (pinfunction "VCCO_13_AB14") (pintype "power_in"))
      (node (ref "U14") (pin "F12") (pinfunction "VCCO_0_F12") (pintype "power_in"))
      (node (ref "U14") (pin "M14") (pinfunction "VCCO_14_M14") (pintype "power_in"))
      (node (ref "U14") (pin "P18") (pinfunction "VCCO_14_P18") (pintype "power_in"))
      (node (ref "U14") (pin "R15") (pinfunction "VCCO_14_R15") (pintype "power_in"))
      (node (ref "U14") (pin "T12") (pinfunction "VCCO_0_T12") (pintype "power_in"))
      (node (ref "U14") (pin "T22") (pinfunction "VCCO_14_T22") (pintype "power_in"))
      (node (ref "U14") (pin "U11") (pinfunction "M0_0_U11") (pintype "input"))
      (node (ref "U14") (pin "U19") (pinfunction "VCCO_14_U19") (pintype "power_in"))
      (node (ref "U14") (pin "U8") (pinfunction "CFGBVS_0_U8") (pintype "input"))
      (node (ref "U14") (pin "V16") (pinfunction "VCCO_13_V16") (pintype "power_in"))
      (node (ref "U14") (pin "W13") (pinfunction "VCCO_13_W13") (pintype "power_in"))
      (node (ref "U14") (pin "Y10") (pinfunction "VCCO_13_Y10") (pintype "power_in"))
      (node (ref "U14") (pin "Y20") (pinfunction "VCCO_14_Y20") (pintype "power_in"))
      (node (ref "U15") (pin "20") (pinfunction "VCCIO-1_20") (pintype "power_in"))
      (node (ref "U15") (pin "31") (pinfunction "VCCIO-2_31") (pintype "power_in"))
      (node (ref "U15") (pin "42") (pinfunction "VCCIO-3_42") (pintype "power_in"))
      (node (ref "U15") (pin "50") (pinfunction "VREGIN_50") (pintype "power_in"))
      (node (ref "U15") (pin "56") (pinfunction "VCCIO-4_56") (pintype "power_in"))
      (node (ref "U16") (pin "8") (pinfunction "VCC_8") (pintype "power_in"))
      (node (ref "U17") (pin "6") (pinfunction "VCC_6") (pintype "power_in"))
      (node (ref "X1") (pin "4") (pinfunction "VDD_4") (pintype "input"))
    )
    (net (code "233") (name "5V0") (class "Default")
      (node (ref "D2") (pin "1") (pinfunction "K_1") (pintype "passive"))
    )
    (net (code "234") (name "GND") (class "Default")
      (node (ref "C100") (pin "2") (pinfunction "2_2") (pintype "passive"))
      (node (ref "C101") (pin "2") (pinfunction "2_2") (pintype "passive"))
      (node (ref "C102") (pin "2") (pinfunction "2_2") (pintype "passive"))
      (node (ref "C103") (pin "2") (pinfunction "2_2") (pintype "passive"))
      (node (ref "C104") (pin "1") (pinfunction "1_1") (pintype "passive"))
      (node (ref "C105") (pin "2") (pinfunction "2_2") (pintype "passive"))
      (node (ref "C106") (pin "2") (pinfunction "2_2") (pintype "passive"))
      (node (ref "C107") (pin "2") (pinfunction "2_2") (pintype "passive"))
      (node (ref "C108") (pin "1") (pinfunction "1_1") (pintype "passive"))
      (node (ref "C109") (pin "1") (pinfunction "1_1") (pintype "passive"))
      (node (ref "C110") (pin "2") (pinfunction "2_2") (pintype "passive"))
      (node (ref "C111") (pin "2") (pinfunction "2_2") (pintype "passive"))
      (node (ref "C112") (pin "2") (pinfunction "2_2") (pintype "passive"))
      (node (ref "C113") (pin "2") (pinfunction "2_2") (pintype "passive"))
      (node (ref "C114") (pin "2") (pinfunction "2_2") (pintype "passive"))
      (node (ref "C115") (pin "2") (pinfunction "2_2") (pintype "passive"))
      (node (ref "C116") (pin "2") (pinfunction "2_2") (pintype "passive"))
      (node (ref "C117") (pin "1") (pinfunction "1_1") (pintype "passive"))
      (node (ref "C118") (pin "2") (pinfunction "2_2") (pintype "passive"))
      (node (ref "C119") (pin "2") (pinfunction "2_2") (pintype "passive"))
      (node (ref "C120") (pin "2") (pinfunction "2_2") (pintype "passive"))
      (node (ref "C121") (pin "2") (pinfunction "2_2") (pintype "passive"))
      (node (ref "C122") (pin "2") (pinfunction "2_2") (pintype "passive"))
      (node (ref "C123") (pin "2") (pinfunction "2_2") (pintype "passive"))
      (node (ref "C124") (pin "2") (pinfunction "2_2") (pintype "passive"))
      (node (ref "C125") (pin "2") (pinfunction "2_2") (pintype "passive"))
      (node (ref "C126") (pin "2") (pinfunction "2_2") (pintype "passive"))
      (node (ref "C127") (pin "2") (pinfunction "2_2") (pintype "passive"))
      (node (ref "C128") (pin "2") (pinfunction "2_2") (pintype "passive"))
      (node (ref "C129") (pin "2") (pinfunction "2_2") (pintype "passive"))
      (node (ref "C130") (pin "2") (pinfunction "2_2") (pintype "passive"))
      (node (ref "C131") (pin "2") (pinfunction "2_2") (pintype "passive"))
      (node (ref "C132") (pin "2") (pinfunction "2_2") (pintype "passive"))
      (node (ref "C133") (pin "2") (pinfunction "2_2") (pintype "passive"))
      (node (ref "C134") (pin "2") (pinfunction "2_2") (pintype "passive"))
      (node (ref "C135") (pin "2") (pinfunction "2_2") (pintype "passive"))
      (node (ref "C136") (pin "2") (pinfunction "2_2") (pintype "passive"))
      (node (ref "C137") (pin "2") (pinfunction "2_2") (pintype "passive"))
      (node (ref "C138") (pin "2") (pinfunction "2_2") (pintype "passive"))
      (node (ref "C139") (pin "2") (pinfunction "2_2") (pintype "passive"))
      (node (ref "C140") (pin "2") (pinfunction "2_2") (pintype "passive"))
      (node (ref "C141") (pin "2") (pinfunction "2_2") (pintype "passive"))
      (node (ref "C142") (pin "2") (pinfunction "2_2") (pintype "passive"))
      (node (ref "C143") (pin "2") (pinfunction "2_2") (pintype "passive"))
      (node (ref "C144") (pin "2") (pinfunction "2_2") (pintype "passive"))
      (node (ref "C145") (pin "2") (pinfunction "2_2") (pintype "passive"))
      (node (ref "C146") (pin "2") (pinfunction "2_2") (pintype "passive"))
      (node (ref "C147") (pin "1") (pinfunction "1_1") (pintype "passive"))
      (node (ref "C218") (pin "2") (pinfunction "2_2") (pintype "passive"))
      (node (ref "C219") (pin "1") (pinfunction "1_1") (pintype "passive"))
      (node (ref "C222") (pin "2") (pinfunction "2_2") (pintype "passive"))
      (node (ref "C223") (pin "2") (pinfunction "2_2") (pintype "passive"))
      (node (ref "C229") (pin "2") (pinfunction "2_2") (pintype "passive"))
      (node (ref "C230") (pin "2") (pinfunction "2_2") (pintype "passive"))
      (node (ref "C231") (pin "2") (pinfunction "2_2") (pintype "passive"))
      (node (ref "C232") (pin "2") (pinfunction "2_2") (pintype "passive"))
      (node (ref "C38") (pin "2") (pinfunction "2_2") (pintype "passive"))
      (node (ref "C43") (pin "2") (pinfunction "2_2") (pintype "passive"))
      (node (ref "C44") (pin "2") (pinfunction "2_2") (pintype "passive"))
      (node (ref "C45") (pin "2") (pinfunction "2_2") (pintype "passive"))
      (node (ref "C46") (pin "1") (pinfunction "1_1") (pintype "passive"))
      (node (ref "C47") (pin "1") (pinfunction "1_1") (pintype "passive"))
      (node (ref "C48") (pin "1") (pinfunction "1_1") (pintype "passive"))
      (node (ref "C49") (pin "2") (pinfunction "2_2") (pintype "passive"))
      (node (ref "C50") (pin "1") (pinfunction "1_1") (pintype "passive"))
      (node (ref "C51") (pin "2") (pinfunction "2_2") (pintype "passive"))
      (node (ref "C52") (pin "2") (pinfunction "2_2") (pintype "passive"))
      (node (ref "C53") (pin "2") (pinfunction "2_2") (pintype "passive"))
      (node (ref "C54") (pin "2") (pinfunction "2_2") (pintype "passive"))
      (node (ref "C55") (pin "2") (pinfunction "2_2") (pintype "passive"))
      (node (ref "C56") (pin "2") (pinfunction "2_2") (pintype "passive"))
      (node (ref "C57") (pin "2") (pinfunction "2_2") (pintype "passive"))
      (node (ref "C58") (pin "2") (pinfunction "2_2") (pintype "passive"))
      (node (ref "C59") (pin "2") (pinfunction "2_2") (pintype "passive"))
      (node (ref "C60") (pin "2") (pinfunction "2_2") (pintype "passive"))
      (node (ref "C61") (pin "2") (pinfunction "2_2") (pintype "passive"))
      (node (ref "C62") (pin "2") (pinfunction "2_2") (pintype "passive"))
      (node (ref "C63") (pin "2") (pinfunction "2_2") (pintype "passive"))
      (node (ref "C64") (pin "2") (pinfunction "2_2") (pintype "passive"))
      (node (ref "C65") (pin "2") (pinfunction "2_2") (pintype "passive"))
      (node (ref "C66") (pin "2") (pinfunction "2_2") (pintype "passive"))
      (node (ref "C67") (pin "2") (pinfunction "2_2") (pintype "passive"))
      (node (ref "C68") (pin "2") (pinfunction "2_2") (pintype "passive"))
      (node (ref "C69") (pin "2") (pinfunction "2_2") (pintype "passive"))
      (node (ref "C70") (pin "2") (pinfunction "2_2") (pintype "passive"))
      (node (ref "C71") (pin "2") (pinfunction "2_2") (pintype "passive"))
      (node (ref "C72") (pin "2") (pinfunction "2_2") (pintype "passive"))
      (node (ref "C73") (pin "2") (pinfunction "2_2") (pintype "passive"))
      (node (ref "C74") (pin "2") (pinfunction "2_2") (pintype "passive"))
      (node (ref "C75") (pin "2") (pinfunction "2_2") (pintype "passive"))
      (node (ref "C76") (pin "2") (pinfunction "2_2") (pintype "passive"))
      (node (ref "C77") (pin "2") (pinfunction "2_2") (pintype "passive"))
      (node (ref "C78") (pin "2") (pinfunction "2_2") (pintype "passive"))
      (node (ref "C79") (pin "2") (pinfunction "2_2") (pintype "passive"))
      (node (ref "C80") (pin "2") (pinfunction "2_2") (pintype "passive"))
      (node (ref "C81") (pin "2") (pinfunction "2_2") (pintype "passive"))
      (node (ref "C82") (pin "2") (pinfunction "2_2") (pintype "passive"))
      (node (ref "C83") (pin "2") (pinfunction "2_2") (pintype "passive"))
      (node (ref "C84") (pin "2") (pinfunction "2_2") (pintype "passive"))
      (node (ref "C85") (pin "2") (pinfunction "2_2") (pintype "passive"))
      (node (ref "C86") (pin "2") (pinfunction "2_2") (pintype "passive"))
      (node (ref "C87") (pin "2") (pinfunction "2_2") (pintype "passive"))
      (node (ref "C88") (pin "2") (pinfunction "2_2") (pintype "passive"))
      (node (ref "C89") (pin "2") (pinfunction "2_2") (pintype "passive"))
      (node (ref "C90") (pin "2") (pinfunction "2_2") (pintype "passive"))
      (node (ref "C91") (pin "2") (pinfunction "2_2") (pintype "passive"))
      (node (ref "C92") (pin "2") (pinfunction "2_2") (pintype "passive"))
      (node (ref "C93") (pin "2") (pinfunction "2_2") (pintype "passive"))
      (node (ref "C94") (pin "2") (pinfunction "2_2") (pintype "passive"))
      (node (ref "C95") (pin "2") (pinfunction "2_2") (pintype "passive"))
      (node (ref "C96") (pin "2") (pinfunction "2_2") (pintype "passive"))
      (node (ref "C97") (pin "2") (pinfunction "2_2") (pintype "passive"))
      (node (ref "C98") (pin "2") (pinfunction "2_2") (pintype "passive"))
      (node (ref "C99") (pin "2") (pinfunction "2_2") (pintype "passive"))
      (node (ref "J5") (pin "1") (pinfunction "MNT_1_1") (pintype "passive"))
      (node (ref "J5") (pin "2") (pinfunction "MNT_2_2") (pintype "passive"))
      (node (ref "J5") (pin "3") (pinfunction "MNT_3_3") (pintype "passive"))
      (node (ref "J5") (pin "4") (pinfunction "MNT_4_4") (pintype "passive"))
      (node (ref "J5") (pin "5") (pinfunction "MNT_5_5") (pintype "passive"))
      (node (ref "J5") (pin "6") (pinfunction "MNT_6_6") (pintype "passive"))
      (node (ref "J5") (pin "A1/B12") (pinfunction "GND_A1/B12") (pintype "power_in"))
      (node (ref "J5") (pin "A12/B1") (pinfunction "GND_A12/B1") (pintype "power_in"))
      (node (ref "R63") (pin "2") (pinfunction "2_2") (pintype "passive"))
      (node (ref "R69") (pin "2") (pinfunction "2_2") (pintype "passive"))
      (node (ref "R70") (pin "1") (pinfunction "1_1") (pintype "passive"))
      (node (ref "R71") (pin "2") (pinfunction "2_2") (pintype "passive"))
      (node (ref "R72") (pin "1") (pinfunction "1_1") (pintype "passive"))
      (node (ref "R73") (pin "1") (pinfunction "1_1") (pintype "passive"))
      (node (ref "U14") (pin "A11") (pinfunction "GND_A11") (pintype "power_in"))
      (node (ref "U14") (pin "A12") (pinfunction "GND_A12") (pintype "power_in"))
      (node (ref "U14") (pin "A2") (pinfunction "GND_A2") (pintype "power_in"))
      (node (ref "U14") (pin "A22") (pinfunction "GND_A22") (pintype "power_in"))
      (node (ref "U14") (pin "A3") (pinfunction "GND_A3") (pintype "power_in"))
      (node (ref "U14") (pin "A5") (pinfunction "GND_A5") (pintype "power_in"))
      (node (ref "U14") (pin "A7") (pinfunction "GND_A7") (pintype "power_in"))
      (node (ref "U14") (pin "A9") (pinfunction "GND_A9") (pintype "power_in"))
      (node (ref "U14") (pin "AA12") (pinfunction "GND_AA12") (pintype "power_in"))
      (node (ref "U14") (pin "AA2") (pinfunction "GND_AA2") (pintype "power_in"))
      (node (ref "U14") (pin "AA22") (pinfunction "GND_AA22") (pintype "power_in"))
      (node (ref "U14") (pin "AB19") (pinfunction "GND_AB19") (pintype "power_in"))
      (node (ref "U14") (pin "AB9") (pinfunction "GND_AB9") (pintype "power_in"))
      (node (ref "U14") (pin "B12") (pinfunction "GND_B12") (pintype "power_in"))
      (node (ref "U14") (pin "B19") (pinfunction "GND_B19") (pintype "power_in"))
      (node (ref "U14") (pin "B3") (pinfunction "GND_B3") (pintype "power_in"))
      (node (ref "U14") (pin "C10") (pinfunction "GND_C10") (pintype "power_in"))
      (node (ref "U14") (pin "C12") (pinfunction "GND_C12") (pintype "power_in"))
      (node (ref "U14") (pin "C16") (pinfunction "GND_C16") (pintype "power_in"))
      (node (ref "U14") (pin "C3") (pinfunction "GND_C3") (pintype "power_in"))
      (node (ref "U14") (pin "C6") (pinfunction "GND_C6") (pintype "power_in"))
      (node (ref "U14") (pin "D12") (pinfunction "GND_D12") (pintype "power_in"))
      (node (ref "U14") (pin "D13") (pinfunction "GND_D13") (pintype "power_in"))
      (node (ref "U14") (pin "D3") (pinfunction "GND_D3") (pintype "power_in"))
      (node (ref "U14") (pin "D4") (pinfunction "GND_D4") (pintype "power_in"))
      (node (ref "U14") (pin "D8") (pinfunction "GND_D8") (pintype "power_in"))
      (node (ref "U14") (pin "E11") (pinfunction "GND_E11") (pintype "power_in"))
      (node (ref "U14") (pin "E20") (pinfunction "GND_E20") (pintype "power_in"))
      (node (ref "U14") (pin "E4") (pinfunction "GND_E4") (pintype "power_in"))
      (node (ref "U14") (pin "E5") (pinfunction "GND_E5") (pintype "power_in"))
      (node (ref "U14") (pin "E7") (pinfunction "GND_E7") (pintype "power_in"))
      (node (ref "U14") (pin "E9") (pinfunction "GND_E9") (pintype "power_in"))
      (node (ref "U14") (pin "F11") (pinfunction "GND_F11") (pintype "power_in"))
      (node (ref "U14") (pin "F17") (pinfunction "GND_F17") (pintype "power_in"))
      (node (ref "U14") (pin "F5") (pinfunction "GND_F5") (pintype "power_in"))
      (node (ref "U14") (pin "G10") (pinfunction "GND_G10") (pintype "power_in"))
      (node (ref "U14") (pin "G12") (pinfunction "GND_G12") (pintype "power_in"))
      (node (ref "U14") (pin "G14") (pinfunction "GND_G14") (pintype "power_in"))
      (node (ref "U14") (pin "G5") (pinfunction "GND_G5") (pintype "power_in"))
      (node (ref "U14") (pin "G6") (pinfunction "GND_G6") (pintype "power_in"))
      (node (ref "U14") (pin "G7") (pinfunction "GND_G7") (pintype "power_in"))
      (node (ref "U14") (pin "G8") (pinfunction "GND_G8") (pintype "power_in"))
      (node (ref "U14") (pin "G9") (pinfunction "GND_G9") (pintype "power_in"))
      (node (ref "U14") (pin "H1") (pinfunction "GND_H1") (pintype "power_in"))
      (node (ref "U14") (pin "H11") (pinfunction "GND_H11") (pintype "power_in"))
      (node (ref "U14") (pin "H21") (pinfunction "GND_H21") (pintype "power_in"))
      (node (ref "U14") (pin "H7") (pinfunction "GND_H7") (pintype "power_in"))
      (node (ref "U14") (pin "H9") (pinfunction "GND_H9") (pintype "power_in"))
      (node (ref "U14") (pin "J10") (pinfunction "GND_J10") (pintype "power_in"))
      (node (ref "U14") (pin "J12") (pinfunction "GND_J12") (pintype "power_in"))
      (node (ref "U14") (pin "J18") (pinfunction "GND_J18") (pintype "power_in"))
      (node (ref "U14") (pin "J8") (pinfunction "GND_J8") (pintype "power_in"))
      (node (ref "U14") (pin "K11") (pinfunction "GND_K11") (pintype "power_in"))
      (node (ref "U14") (pin "K15") (pinfunction "GND_K15") (pintype "power_in"))
      (node (ref "U14") (pin "K5") (pinfunction "GND_K5") (pintype "power_in"))
      (node (ref "U14") (pin "K7") (pinfunction "GND_K7") (pintype "power_in"))
      (node (ref "U14") (pin "K9") (pinfunction "GNDADC_0_K9") (pintype "power_in"))
      (node (ref "U14") (pin "L10") (pinfunction "VP_0_L10") (pintype "input"))
      (node (ref "U14") (pin "L2") (pinfunction "GND_L2") (pintype "power_in"))
      (node (ref "U14") (pin "L22") (pinfunction "GND_L22") (pintype "power_in"))
      (node (ref "U14") (pin "L8") (pinfunction "GND_L8") (pintype "power_in"))
      (node (ref "U14") (pin "L9") (pinfunction "VREFN_0_L9") (pintype "input"))
      (node (ref "U14") (pin "M10") (pinfunction "VREFP_0_M10") (pintype "input"))
      (node (ref "U14") (pin "M11") (pinfunction "GND_M11") (pintype "power_in"))
      (node (ref "U14") (pin "M19") (pinfunction "GND_M19") (pintype "power_in"))
      (node (ref "U14") (pin "M7") (pinfunction "GND_M7") (pintype "power_in"))
      (node (ref "U14") (pin "M9") (pinfunction "VN_0_M9") (pintype "input"))
      (node (ref "U14") (pin "N10") (pinfunction "DXP_0_N10") (pintype "input"))
      (node (ref "U14") (pin "N16") (pinfunction "GND_N16") (pintype "power_in"))
      (node (ref "U14") (pin "N6") (pinfunction "GND_N6") (pintype "power_in"))
      (node (ref "U14") (pin "N8") (pinfunction "GND_N8") (pintype "power_in"))
      (node (ref "U14") (pin "N9") (pinfunction "DXN_0_N9") (pintype "input"))
      (node (ref "U14") (pin "P11") (pinfunction "GND_P11") (pintype "power_in"))
      (node (ref "U14") (pin "P13") (pinfunction "GND_P13") (pintype "power_in"))
      (node (ref "U14") (pin "P3") (pinfunction "GND_P3") (pintype "power_in"))
      (node (ref "U14") (pin "P7") (pinfunction "GND_P7") (pintype "power_in"))
      (node (ref "U14") (pin "P9") (pinfunction "GND_P9") (pintype "power_in"))
      (node (ref "U14") (pin "R10") (pinfunction "GND_R10") (pintype "power_in"))
      (node (ref "U14") (pin "R12") (pinfunction "GND_R12") (pintype "power_in"))
      (node (ref "U14") (pin "R20") (pinfunction "GND_R20") (pintype "power_in"))
      (node (ref "U14") (pin "R8") (pinfunction "GND_R8") (pintype "power_in"))
      (node (ref "U14") (pin "T11") (pinfunction "GND_T11") (pintype "power_in"))
      (node (ref "U14") (pin "T17") (pinfunction "GND_T17") (pintype "power_in"))
      (node (ref "U14") (pin "T7") (pinfunction "GND_T7") (pintype "power_in"))
      (node (ref "U14") (pin "T9") (pinfunction "GND_T9") (pintype "power_in"))
      (node (ref "U14") (pin "U10") (pinfunction "M1_0_U10") (pintype "input"))
      (node (ref "U14") (pin "U14") (pinfunction "GND_U14") (pintype "power_in"))
      (node (ref "U14") (pin "U4") (pinfunction "GND_U4") (pintype "power_in"))
      (node (ref "U14") (pin "U9") (pinfunction "M2_0_U9") (pintype "input"))
      (node (ref "U14") (pin "V1") (pinfunction "GND_V1") (pintype "power_in"))
      (node (ref "U14") (pin "V11") (pinfunction "GND_V11") (pintype "power_in"))
      (node (ref "U14") (pin "V21") (pinfunction "GND_V21") (pintype "power_in"))
      (node (ref "U14") (pin "W18") (pinfunction "GND_W18") (pintype "power_in"))
      (node (ref "U14") (pin "W8") (pinfunction "GND_W8") (pintype "power_in"))
      (node (ref "U14") (pin "Y15") (pinfunction "GND_Y15") (pintype "power_in"))
      (node (ref "U14") (pin "Y5") (pinfunction "GND_Y5") (pintype "power_in"))
      (node (ref "U15") (pin "1") (pinfunction "GND_1") (pintype "power_in"))
      (node (ref "U15") (pin "10") (pinfunction "AGND_10") (pintype "power_in"))
      (node (ref "U15") (pin "11") (pinfunction "GND_11") (pintype "power_in"))
      (node (ref "U15") (pin "13") (pinfunction "TEST_13") (pintype "input"))
      (node (ref "U15") (pin "15") (pinfunction "GND_15") (pintype "power_in"))
      (node (ref "U15") (pin "25") (pinfunction "GND_25") (pintype "power_in"))
      (node (ref "U15") (pin "35") (pinfunction "GND_35") (pintype "power_in"))
      (node (ref "U15") (pin "47") (pinfunction "GND_47") (pintype "power_in"))
      (node (ref "U15") (pin "5") (pinfunction "GND_5") (pintype "power_in"))
      (node (ref "U15") (pin "51") (pinfunction "GND_51") (pintype "power_in"))
      (node (ref "U16") (pin "4") (pinfunction "GND_4") (pintype "power_in"))
      (node (ref "U17") (pin "2") (pinfunction "VSS_2") (pintype "power_in"))
      (node (ref "X1") (pin "2") (pinfunction "GND_2") (pintype "power_in"))
      (node (ref "X2") (pin "2") (pinfunction "GND_2") (pintype "power_in"))
    )
    (net (code "235") (name "Net-(D2-A)") (class "Default")
      (node (ref "D2") (pin "2") (pinfunction "A_2") (pintype "passive"))
      (node (ref "F1") (pin "2") (pinfunction "2_2") (pintype "passive"))
    )
    (net (code "236") (name "Net-(F1-Pad1)") (class "Default")
      (node (ref "F1") (pin "1") (pinfunction "1_1") (pintype "passive"))
      (node (ref "J5") (pin "A4/B9") (pinfunction "VBUS_A4/B9") (pintype "power_in"))
      (node (ref "J5") (pin "B4/A9") (pinfunction "VBUS_B4/A9") (pintype "power_in"))
    )
    (net (code "237") (name "Net-(J5A-CC1)") (class "Default")
      (node (ref "J5") (pin "A5") (pinfunction "CC1_A5") (pintype "passive"))
      (node (ref "R72") (pin "2") (pinfunction "2_2") (pintype "passive"))
    )
    (net (code "238") (name "Net-(J5A-CC2)") (class "Default")
      (node (ref "J5") (pin "B5") (pinfunction "CC2_B5") (pintype "passive"))
      (node (ref "R73") (pin "2") (pinfunction "2_2") (pintype "passive"))
    )
    (net (code "239") (name "Net-(J5A-D+-PadA6)") (class "Default")
      (node (ref "J5") (pin "A6") (pinfunction "D+_A6") (pintype "bidirectional"))
      (node (ref "J5") (pin "B6") (pinfunction "D+_B6") (pintype "bidirectional"))
      (node (ref "R74") (pin "2") (pinfunction "2_2") (pintype "passive"))
    )
    (net (code "240") (name "Net-(J5A-D--PadA7)") (class "Default")
      (node (ref "J5") (pin "A7") (pinfunction "D-_A7") (pintype "bidirectional"))
      (node (ref "J5") (pin "B7") (pinfunction "D-_B7") (pintype "bidirectional"))
      (node (ref "R75") (pin "2") (pinfunction "2_2") (pintype "passive"))
    )
    (net (code "241") (name "Net-(LED11-C)") (class "Default")
      (node (ref "LED11") (pin "1") (pinfunction "C_1") (pintype "passive"))
      (node (ref "R71") (pin "1") (pinfunction "1_1") (pintype "passive"))
    )
    (net (code "242") (name "Net-(LED12-A)") (class "Default")
      (node (ref "LED12") (pin "2") (pinfunction "A_2") (pintype "passive"))
      (node (ref "R76") (pin "1") (pinfunction "1_1") (pintype "passive"))
    )
    (net (code "243") (name "Net-(LED13-A)") (class "Default")
      (node (ref "LED13") (pin "2") (pinfunction "A_2") (pintype "passive"))
      (node (ref "R77") (pin "1") (pinfunction "1_1") (pintype "passive"))
    )
    (net (code "244") (name "Net-(LED14-A)") (class "Default")
      (node (ref "LED14") (pin "2") (pinfunction "A_2") (pintype "passive"))
      (node (ref "R78") (pin "1") (pinfunction "1_1") (pintype "passive"))
    )
    (net (code "245") (name "Net-(U14G-INIT_B_0)") (class "Default")
      (node (ref "R65") (pin "2") (pinfunction "2_2") (pintype "passive"))
      (node (ref "U14") (pin "U12") (pinfunction "INIT_B_0_U12") (pintype "bidirectional"))
    )
    (net (code "246") (name "Net-(U14G-PROGRAM_B_0)") (class "Default")
      (node (ref "R64") (pin "2") (pinfunction "2_2") (pintype "passive"))
      (node (ref "U14") (pin "N12") (pinfunction "PROGRAM_B_0_N12") (pintype "input"))
    )
    (net (code "247") (name "Net-(U15-REF)") (class "Default")
      (node (ref "R69") (pin "1") (pinfunction "1_1") (pintype "passive"))
      (node (ref "U15") (pin "6") (pinfunction "REF_6") (pintype "input"))
    )
    (net (code "248") (name "Net-(U15-~{RESET})") (class "Default")
      (node (ref "R66") (pin "2") (pinfunction "2_2") (pintype "passive"))
      (node (ref "U15") (pin "14") (pinfunction "~{RESET}_14") (pintype "input"))
    )
    (net (code "249") (name "Net-(U17-DO)") (class "Default")
      (node (ref "R82") (pin "2") (pinfunction "2_2") (pintype "passive"))
      (node (ref "U17") (pin "1") (pinfunction "DO_1") (pintype "output"))
    )
    (net (code "250") (name "Net-(X1-TRI-STATE)") (class "Default")
      (node (ref "R68") (pin "1") (pinfunction "1_1") (pintype "passive"))
      (node (ref "X1") (pin "1") (pinfunction "TRI-STATE_1") (pintype "input"))
    )
    (net (code "251") (name "VIO") (class "Default")
      (node (ref "C65") (pin "1") (pinfunction "1_1") (pintype "passive"))
      (node (ref "C66") (pin "1") (pinfunction "1_1") (pintype "passive"))
      (node (ref "C67") (pin "1") (pinfunction "1_1") (pintype "passive"))
      (node (ref "C68") (pin "1") (pinfunction "1_1") (pintype "passive"))
      (node (ref "C69") (pin "1") (pinfunction "1_1") (pintype "passive"))
      (node (ref "C70") (pin "1") (pinfunction "1_1") (pintype "passive"))
      (node (ref "C71") (pin "1") (pinfunction "1_1") (pintype "passive"))
      (node (ref "C72") (pin "1") (pinfunction "1_1") (pintype "passive"))
      (node (ref "C73") (pin "1") (pinfunction "1_1") (pintype "passive"))
      (node (ref "C74") (pin "1") (pinfunction "1_1") (pintype "passive"))
      (node (ref "C75") (pin "1") (pinfunction "1_1") (pintype "passive"))
      (node (ref "C76") (pin "1") (pinfunction "1_1") (pintype "passive"))
      (node (ref "C77") (pin "1") (pinfunction "1_1") (pintype "passive"))
      (node (ref "C78") (pin "1") (pinfunction "1_1") (pintype "passive"))
      (node (ref "U14") (pin "A17") (pinfunction "VCCO_16_A17") (pintype "power_in"))
      (node (ref "U14") (pin "B14") (pinfunction "VCCO_16_B14") (pintype "power_in"))
      (node (ref "U14") (pin "C21") (pinfunction "VCCO_16_C21") (pintype "power_in"))
      (node (ref "U14") (pin "D18") (pinfunction "VCCO_16_D18") (pintype "power_in"))
      (node (ref "U14") (pin "E15") (pinfunction "VCCO_16_E15") (pintype "power_in"))
      (node (ref "U14") (pin "F22") (pinfunction "VCCO_16_F22") (pintype "power_in"))
      (node (ref "U14") (pin "G19") (pinfunction "VCCO_15_G19") (pintype "power_in"))
      (node (ref "U14") (pin "H16") (pinfunction "VCCO_15_H16") (pintype "power_in"))
      (node (ref "U14") (pin "J13") (pinfunction "VCCO_15_J13") (pintype "power_in"))
      (node (ref "U14") (pin "K20") (pinfunction "VCCO_15_K20") (pintype "power_in"))
      (node (ref "U14") (pin "L17") (pinfunction "VCCO_15_L17") (pintype "power_in"))
      (node (ref "U14") (pin "N21") (pinfunction "VCCO_15_N21") (pintype "power_in"))
    )
    (net (code "252") (name "unconnected-(J5A-SBU1-PadA8)") (class "Default")
      (node (ref "J5") (pin "A8") (pinfunction "SBU1_A8") (pintype "passive+no_connect"))
    )
    (net (code "253") (name "unconnected-(J5A-SBU2-PadB8)") (class "Default")
      (node (ref "J5") (pin "B8") (pinfunction "SBU2_B8") (pintype "passive+no_connect"))
    )
    (net (code "254") (name "unconnected-(U14A-IO_0_13-PadY17)") (class "Default")
      (node (ref "U14") (pin "Y17") (pinfunction "IO_0_13_Y17") (pintype "bidirectional"))
    )
    (net (code "255") (name "unconnected-(U14A-IO_L5N_T0_13-PadAA14)") (class "Default")
      (node (ref "U14") (pin "AA14") (pinfunction "IO_L5N_T0_13_AA14") (pintype "bidirectional"))
    )
    (net (code "256") (name "unconnected-(U14A-IO_L5P_T0_13-PadY13)") (class "Default")
      (node (ref "U14") (pin "Y13") (pinfunction "IO_L5P_T0_13_Y13") (pintype "bidirectional"))
    )
    (net (code "257") (name "unconnected-(U14A-IO_L6P_T0_13-PadW14)") (class "Default")
      (node (ref "U14") (pin "W14") (pinfunction "IO_L6P_T0_13_W14") (pintype "bidirectional"))
    )
    (net (code "258") (name "unconnected-(U14A-IO_L8N_T1_13-PadAB10)") (class "Default")
      (node (ref "U14") (pin "AB10") (pinfunction "IO_L8N_T1_13_AB10") (pintype "bidirectional"))
    )
    (net (code "259") (name "unconnected-(U14A-IO_L8P_T1_13-PadAA9)") (class "Default")
      (node (ref "U14") (pin "AA9") (pinfunction "IO_L8P_T1_13_AA9") (pintype "bidirectional"))
    )
    (net (code "260") (name "unconnected-(U14A-IO_L9P_T1_DQS_13-PadAA10)") (class "Default")
      (node (ref "U14") (pin "AA10") (pinfunction "IO_L9P_T1_DQS_13_AA10") (pintype "bidirectional"))
    )
    (net (code "261") (name "unconnected-(U14A-IO_L10N_T1_13-PadW10)") (class "Default")
      (node (ref "U14") (pin "W10") (pinfunction "IO_L10N_T1_13_W10") (pintype "bidirectional"))
    )
    (net (code "262") (name "unconnected-(U14A-IO_L10P_T1_13-PadV10)") (class "Default")
      (node (ref "U14") (pin "V10") (pinfunction "IO_L10P_T1_13_V10") (pintype "bidirectional"))
    )
    (net (code "263") (name "unconnected-(U14A-IO_L11P_T1_SRCC_13-PadY11)") (class "Default")
      (node (ref "U14") (pin "Y11") (pinfunction "IO_L11P_T1_SRCC_13_Y11") (pintype "bidirectional"))
    )
    (net (code "264") (name "unconnected-(U14A-IO_L12N_T1_MRCC_13-PadW12)") (class "Default")
      (node (ref "U14") (pin "W12") (pinfunction "IO_L12N_T1_MRCC_13_W12") (pintype "bidirectional"))
    )
    (net (code "265") (name "unconnected-(U14A-IO_L12P_T1_MRCC_13-PadW11)") (class "Default")
      (node (ref "U14") (pin "W11") (pinfunction "IO_L12P_T1_MRCC_13_W11") (pintype "bidirectional"))
    )
    (net (code "266") (name "unconnected-(U14A-IO_L13N_T2_MRCC_13-PadV14)") (class "Default")
      (node (ref "U14") (pin "V14") (pinfunction "IO_L13N_T2_MRCC_13_V14") (pintype "bidirectional"))
    )
    (net (code "267") (name "unconnected-(U14A-IO_L13P_T2_MRCC_13-PadV13)") (class "Default")
      (node (ref "U14") (pin "V13") (pinfunction "IO_L13P_T2_MRCC_13_V13") (pintype "bidirectional"))
    )
    (net (code "268") (name "unconnected-(U14A-IO_L14N_T2_SRCC_13-PadV15)") (class "Default")
      (node (ref "U14") (pin "V15") (pinfunction "IO_L14N_T2_SRCC_13_V15") (pintype "bidirectional"))
    )
    (net (code "269") (name "unconnected-(U14A-IO_L14P_T2_SRCC_13-PadU15)") (class "Default")
      (node (ref "U14") (pin "U15") (pinfunction "IO_L14P_T2_SRCC_13_U15") (pintype "bidirectional"))
    )
    (net (code "270") (name "unconnected-(U14A-IO_L15N_T2_DQS_13-PadT15)") (class "Default")
      (node (ref "U14") (pin "T15") (pinfunction "IO_L15N_T2_DQS_13_T15") (pintype "bidirectional"))
    )
    (net (code "271") (name "unconnected-(U14A-IO_L15P_T2_DQS_13-PadT14)") (class "Default")
      (node (ref "U14") (pin "T14") (pinfunction "IO_L15P_T2_DQS_13_T14") (pintype "bidirectional"))
    )
    (net (code "272") (name "unconnected-(U14A-IO_L17N_T2_13-PadU16)") (class "Default")
      (node (ref "U14") (pin "U16") (pinfunction "IO_L17N_T2_13_U16") (pintype "bidirectional"))
    )
    (net (code "273") (name "unconnected-(U14A-IO_L17P_T2_13-PadT16)") (class "Default")
      (node (ref "U14") (pin "T16") (pinfunction "IO_L17P_T2_13_T16") (pintype "bidirectional"))
    )
    (net (code "274") (name "unconnected-(U14B-IO_0_14-PadP20)") (class "Default")
      (node (ref "U14") (pin "P20") (pinfunction "IO_0_14_P20") (pintype "bidirectional"))
    )
    (net (code "275") (name "unconnected-(U14B-IO_25_14-PadN15)") (class "Default")
      (node (ref "U14") (pin "N15") (pinfunction "IO_25_14_N15") (pintype "bidirectional"))
    )
    (net (code "276") (name "unconnected-(U14B-IO_L5N_T0_D07_14-PadR19)") (class "Default")
      (node (ref "U14") (pin "R19") (pinfunction "IO_L5N_T0_D07_14_R19") (pintype "bidirectional"))
    )
    (net (code "277") (name "unconnected-(U14B-IO_L6N_T0_D08_VREF_14-PadT20)") (class "Default")
      (node (ref "U14") (pin "T20") (pinfunction "IO_L6N_T0_D08_VREF_14_T20") (pintype "bidirectional"))
    )
    (net (code "278") (name "unconnected-(U14B-IO_L7N_T1_D10_14-PadW22)") (class "Default")
      (node (ref "U14") (pin "W22") (pinfunction "IO_L7N_T1_D10_14_W22") (pintype "bidirectional"))
    )
    (net (code "279") (name "unconnected-(U14B-IO_L7P_T1_D09_14-PadW21)") (class "Default")
      (node (ref "U14") (pin "W21") (pinfunction "IO_L7P_T1_D09_14_W21") (pintype "bidirectional"))
    )
    (net (code "280") (name "unconnected-(U14B-IO_L9N_T1_DQS_D13_14-PadY22)") (class "Default")
      (node (ref "U14") (pin "Y22") (pinfunction "IO_L9N_T1_DQS_D13_14_Y22") (pintype "bidirectional"))
    )
    (net (code "281") (name "unconnected-(U14B-IO_L11N_T1_SRCC_14-PadV20)") (class "Default")
      (node (ref "U14") (pin "V20") (pinfunction "IO_L11N_T1_SRCC_14_V20") (pintype "bidirectional"))
    )
    (net (code "282") (name "unconnected-(U14B-IO_L12N_T1_MRCC_14-PadW20)") (class "Default")
      (node (ref "U14") (pin "W20") (pinfunction "IO_L12N_T1_MRCC_14_W20") (pintype "bidirectional"))
    )
    (net (code "283") (name "unconnected-(U14B-IO_L15P_T2_DQS_RDWR_B_14-PadAA19)") (class "Default")
      (node (ref "U14") (pin "AA19") (pinfunction "IO_L15P_T2_DQS_RDWR_B_14_AA19") (pintype "bidirectional"))
    )
    (net (code "284") (name "unconnected-(U14B-IO_L16N_T2_A15_D31_14-PadW17)") (class "Default")
      (node (ref "U14") (pin "W17") (pinfunction "IO_L16N_T2_A15_D31_14_W17") (pintype "bidirectional"))
    )
    (net (code "285") (name "unconnected-(U14B-IO_L16P_T2_CSI_B_14-PadV17)") (class "Default")
      (node (ref "U14") (pin "V17") (pinfunction "IO_L16P_T2_CSI_B_14_V17") (pintype "bidirectional"))
    )
    (net (code "286") (name "unconnected-(U14B-IO_L18N_T2_A11_D27_14-PadU18)") (class "Default")
      (node (ref "U14") (pin "U18") (pinfunction "IO_L18N_T2_A11_D27_14_U18") (pintype "bidirectional"))
    )
    (net (code "287") (name "unconnected-(U14B-IO_L18P_T2_A12_D28_14-PadU17)") (class "Default")
      (node (ref "U14") (pin "U17") (pinfunction "IO_L18P_T2_A12_D28_14_U17") (pintype "bidirectional"))
    )
    (net (code "288") (name "unconnected-(U14B-IO_L19N_T3_A09_D25_VREF_14-PadR14)") (class "Default")
      (node (ref "U14") (pin "R14") (pinfunction "IO_L19N_T3_A09_D25_VREF_14_R14") (pintype "bidirectional"))
    )
    (net (code "289") (name "unconnected-(U14B-IO_L19P_T3_A10_D26_14-PadP14)") (class "Default")
      (node (ref "U14") (pin "P14") (pinfunction "IO_L19P_T3_A10_D26_14_P14") (pintype "bidirectional"))
    )
    (net (code "290") (name "unconnected-(U14B-IO_L20N_T3_A07_D23_14-PadT18)") (class "Default")
      (node (ref "U14") (pin "T18") (pinfunction "IO_L20N_T3_A07_D23_14_T18") (pintype "bidirectional"))
    )
    (net (code "291") (name "unconnected-(U14B-IO_L20P_T3_A08_D24_14-PadR18)") (class "Default")
      (node (ref "U14") (pin "R18") (pinfunction "IO_L20P_T3_A08_D24_14_R18") (pintype "bidirectional"))
    )
    (net (code "292") (name "unconnected-(U14C-IO_0_15-PadJ16)") (class "Default")
      (node (ref "U14") (pin "J16") (pinfunction "IO_0_15_J16") (pintype "bidirectional+no_connect"))
    )
    (net (code "293") (name "unconnected-(U14C-IO_25_15-PadM17)") (class "Default")
      (node (ref "U14") (pin "M17") (pinfunction "IO_25_15_M17") (pintype "bidirectional+no_connect"))
    )
    (net (code "294") (name "unconnected-(U14C-IO_L6N_T0_VREF_15-PadH18)") (class "Default")
      (node (ref "U14") (pin "H18") (pinfunction "IO_L6N_T0_VREF_15_H18") (pintype "bidirectional+no_connect"))
    )
    (net (code "295") (name "unconnected-(U14C-IO_L19N_T3_A21_VREF_15-PadK14)") (class "Default")
      (node (ref "U14") (pin "K14") (pinfunction "IO_L19N_T3_A21_VREF_15_K14") (pintype "bidirectional+no_connect"))
    )
    (net (code "296") (name "unconnected-(U14D-IO_0_16-PadF15)") (class "Default")
      (node (ref "U14") (pin "F15") (pinfunction "IO_0_16_F15") (pintype "bidirectional+no_connect"))
    )
    (net (code "297") (name "unconnected-(U14D-IO_25_16-PadF21)") (class "Default")
      (node (ref "U14") (pin "F21") (pinfunction "IO_25_16_F21") (pintype "bidirectional+no_connect"))
    )
    (net (code "298") (name "unconnected-(U14D-IO_L6N_T0_VREF_16-PadD15)") (class "Default")
      (node (ref "U14") (pin "D15") (pinfunction "IO_L6N_T0_VREF_16_D15") (pintype "bidirectional+no_connect"))
    )
    (net (code "299") (name "unconnected-(U14D-IO_L19N_T3_VREF_16-PadC20)") (class "Default")
      (node (ref "U14") (pin "C20") (pinfunction "IO_L19N_T3_VREF_16_C20") (pintype "bidirectional+no_connect"))
    )
    (net (code "300") (name "unconnected-(U14D-IO_L23P_T3_16-PadE21)") (class "Default")
      (node (ref "U14") (pin "E21") (pinfunction "IO_L23P_T3_16_E21") (pintype "bidirectional"))
    )
    (net (code "301") (name "unconnected-(U14D-IO_L24N_T3_16-PadG22)") (class "Default")
      (node (ref "U14") (pin "G22") (pinfunction "IO_L24N_T3_16_G22") (pintype "bidirectional"))
    )
    (net (code "302") (name "unconnected-(U14E-IO_0_34-PadT3)") (class "Default")
      (node (ref "U14") (pin "T3") (pinfunction "IO_0_34_T3") (pintype "bidirectional+no_connect"))
    )
    (net (code "303") (name "unconnected-(U14E-IO_25_34-PadU7)") (class "Default")
      (node (ref "U14") (pin "U7") (pinfunction "IO_25_34_U7") (pintype "bidirectional+no_connect"))
    )
    (net (code "304") (name "unconnected-(U14E-IO_L1N_T0_34-PadU1)") (class "Default")
      (node (ref "U14") (pin "U1") (pinfunction "IO_L1N_T0_34_U1") (pintype "bidirectional"))
    )
    (net (code "305") (name "unconnected-(U14E-IO_L1P_T0_34-PadT1)") (class "Default")
      (node (ref "U14") (pin "T1") (pinfunction "IO_L1P_T0_34_T1") (pintype "bidirectional"))
    )
    (net (code "306") (name "unconnected-(U14E-IO_L4N_T0_34-PadY2)") (class "Default")
      (node (ref "U14") (pin "Y2") (pinfunction "IO_L4N_T0_34_Y2") (pintype "bidirectional"))
    )
    (net (code "307") (name "unconnected-(U14E-IO_L6N_T0_VREF_34-PadV3)") (class "Default")
      (node (ref "U14") (pin "V3") (pinfunction "IO_L6N_T0_VREF_34_V3") (pintype "bidirectional"))
    )
    (net (code "308") (name "unconnected-(U14E-IO_L9P_T1_DQS_34-PadY3)") (class "Default")
      (node (ref "U14") (pin "Y3") (pinfunction "IO_L9P_T1_DQS_34_Y3") (pintype "bidirectional"))
    )
    (net (code "309") (name "unconnected-(U14E-IO_L13N_T2_MRCC_34-PadT4)") (class "Default")
      (node (ref "U14") (pin "T4") (pinfunction "IO_L13N_T2_MRCC_34_T4") (pintype "bidirectional"))
    )
    (net (code "310") (name "unconnected-(U14E-IO_L13P_T2_MRCC_34-PadR4)") (class "Default")
      (node (ref "U14") (pin "R4") (pinfunction "IO_L13P_T2_MRCC_34_R4") (pintype "bidirectional"))
    )
    (net (code "311") (name "unconnected-(U14E-IO_L17N_T2_34-PadT6)") (class "Default")
      (node (ref "U14") (pin "T6") (pinfunction "IO_L17N_T2_34_T6") (pintype "bidirectional"))
    )
    (net (code "312") (name "unconnected-(U14E-IO_L18N_T2_34-PadAA6)") (class "Default")
      (node (ref "U14") (pin "AA6") (pinfunction "IO_L18N_T2_34_AA6") (pintype "bidirectional"))
    )
    (net (code "313") (name "unconnected-(U14E-IO_L19N_T3_VREF_34-PadW7)") (class "Default")
      (node (ref "U14") (pin "W7") (pinfunction "IO_L19N_T3_VREF_34_W7") (pintype "bidirectional"))
    )
    (net (code "314") (name "unconnected-(U14E-IO_L19P_T3_34-PadV7)") (class "Default")
      (node (ref "U14") (pin "V7") (pinfunction "IO_L19P_T3_34_V7") (pintype "bidirectional"))
    )
    (net (code "315") (name "unconnected-(U14E-IO_L20N_T3_34-PadAB6)") (class "Default")
      (node (ref "U14") (pin "AB6") (pinfunction "IO_L20N_T3_34_AB6") (pintype "bidirectional"))
    )
    (net (code "316") (name "unconnected-(U14E-IO_L20P_T3_34-PadAB7)") (class "Default")
      (node (ref "U14") (pin "AB7") (pinfunction "IO_L20P_T3_34_AB7") (pintype "bidirectional"))
    )
    (net (code "317") (name "unconnected-(U14E-IO_L21N_T3_DQS_34-PadV8)") (class "Default")
      (node (ref "U14") (pin "V8") (pinfunction "IO_L21N_T3_DQS_34_V8") (pintype "bidirectional"))
    )
    (net (code "318") (name "unconnected-(U14E-IO_L21P_T3_DQS_34-PadV9)") (class "Default")
      (node (ref "U14") (pin "V9") (pinfunction "IO_L21P_T3_DQS_34_V9") (pintype "bidirectional"))
    )
    (net (code "319") (name "unconnected-(U14E-IO_L22N_T3_34-PadAB8)") (class "Default")
      (node (ref "U14") (pin "AB8") (pinfunction "IO_L22N_T3_34_AB8") (pintype "bidirectional"))
    )
    (net (code "320") (name "unconnected-(U14E-IO_L22P_T3_34-PadAA8)") (class "Default")
      (node (ref "U14") (pin "AA8") (pinfunction "IO_L22P_T3_34_AA8") (pintype "bidirectional"))
    )
    (net (code "321") (name "unconnected-(U14E-IO_L23N_T3_34-PadY7)") (class "Default")
      (node (ref "U14") (pin "Y7") (pinfunction "IO_L23N_T3_34_Y7") (pintype "bidirectional"))
    )
    (net (code "322") (name "unconnected-(U14E-IO_L24N_T3_34-PadY9)") (class "Default")
      (node (ref "U14") (pin "Y9") (pinfunction "IO_L24N_T3_34_Y9") (pintype "bidirectional"))
    )
    (net (code "323") (name "unconnected-(U14E-IO_L24P_T3_34-PadW9)") (class "Default")
      (node (ref "U14") (pin "W9") (pinfunction "IO_L24P_T3_34_W9") (pintype "bidirectional"))
    )
    (net (code "324") (name "unconnected-(U14F-IO_0_35-PadF4)") (class "Default")
      (node (ref "U14") (pin "F4") (pinfunction "IO_0_35_F4") (pintype "bidirectional+no_connect"))
    )
    (net (code "325") (name "unconnected-(U14F-IO_25_35-PadL6)") (class "Default")
      (node (ref "U14") (pin "L6") (pinfunction "IO_25_35_L6") (pintype "bidirectional+no_connect"))
    )
    (net (code "326") (name "unconnected-(U14F-IO_L6N_T0_VREF_35-PadE3)") (class "Default")
      (node (ref "U14") (pin "E3") (pinfunction "IO_L6N_T0_VREF_35_E3") (pintype "bidirectional+no_connect"))
    )
    (net (code "327") (name "unconnected-(U14F-IO_L12N_T1_MRCC_35-PadG4)") (class "Default")
      (node (ref "U14") (pin "G4") (pinfunction "IO_L12N_T1_MRCC_35_G4") (pintype "bidirectional+no_connect"))
    )
    (net (code "328") (name "unconnected-(U14F-IO_L18N_T2_35-PadL4)") (class "Default")
      (node (ref "U14") (pin "L4") (pinfunction "IO_L18N_T2_35_L4") (pintype "bidirectional+no_connect"))
    )
    (net (code "329") (name "unconnected-(U14F-IO_L19N_T3_VREF_35-PadN3)") (class "Default")
      (node (ref "U14") (pin "N3") (pinfunction "IO_L19N_T3_VREF_35_N3") (pintype "bidirectional+no_connect"))
    )
    (net (code "330") (name "unconnected-(U14H-MGTPRXN0_216-PadA8)") (class "Default")
      (node (ref "U14") (pin "A8") (pinfunction "MGTPRXN0_216_A8") (pintype "input+no_connect"))
    )
    (net (code "331") (name "unconnected-(U14H-MGTPRXN1_216-PadC11)") (class "Default")
      (node (ref "U14") (pin "C11") (pinfunction "MGTPRXN1_216_C11") (pintype "input+no_connect"))
    )
    (net (code "332") (name "unconnected-(U14H-MGTPRXN2_216-PadA10)") (class "Default")
      (node (ref "U14") (pin "A10") (pinfunction "MGTPRXN2_216_A10") (pintype "input+no_connect"))
    )
    (net (code "333") (name "unconnected-(U14H-MGTPRXN3_216-PadC9)") (class "Default")
      (node (ref "U14") (pin "C9") (pinfunction "MGTPRXN3_216_C9") (pintype "input+no_connect"))
    )
    (net (code "334") (name "unconnected-(U14H-MGTPRXP0_216-PadB8)") (class "Default")
      (node (ref "U14") (pin "B8") (pinfunction "MGTPRXP0_216_B8") (pintype "input+no_connect"))
    )
    (net (code "335") (name "unconnected-(U14H-MGTPRXP1_216-PadD11)") (class "Default")
      (node (ref "U14") (pin "D11") (pinfunction "MGTPRXP1_216_D11") (pintype "input+no_connect"))
    )
    (net (code "336") (name "unconnected-(U14H-MGTPRXP2_216-PadB10)") (class "Default")
      (node (ref "U14") (pin "B10") (pinfunction "MGTPRXP2_216_B10") (pintype "input+no_connect"))
    )
    (net (code "337") (name "unconnected-(U14H-MGTPRXP3_216-PadD9)") (class "Default")
      (node (ref "U14") (pin "D9") (pinfunction "MGTPRXP3_216_D9") (pintype "input+no_connect"))
    )
    (net (code "338") (name "unconnected-(U14H-MGTPTXN0_216-PadA4)") (class "Default")
      (node (ref "U14") (pin "A4") (pinfunction "MGTPTXN0_216_A4") (pintype "output"))
    )
    (net (code "339") (name "unconnected-(U14H-MGTPTXN1_216-PadC5)") (class "Default")
      (node (ref "U14") (pin "C5") (pinfunction "MGTPTXN1_216_C5") (pintype "output"))
    )
    (net (code "340") (name "unconnected-(U14H-MGTPTXN2_216-PadA6)") (class "Default")
      (node (ref "U14") (pin "A6") (pinfunction "MGTPTXN2_216_A6") (pintype "output"))
    )
    (net (code "341") (name "unconnected-(U14H-MGTPTXN3_216-PadC7)") (class "Default")
      (node (ref "U14") (pin "C7") (pinfunction "MGTPTXN3_216_C7") (pintype "output"))
    )
    (net (code "342") (name "unconnected-(U14H-MGTPTXP0_216-PadB4)") (class "Default")
      (node (ref "U14") (pin "B4") (pinfunction "MGTPTXP0_216_B4") (pintype "output"))
    )
    (net (code "343") (name "unconnected-(U14H-MGTPTXP1_216-PadD5)") (class "Default")
      (node (ref "U14") (pin "D5") (pinfunction "MGTPTXP1_216_D5") (pintype "output"))
    )
    (net (code "344") (name "unconnected-(U14H-MGTPTXP2_216-PadB6)") (class "Default")
      (node (ref "U14") (pin "B6") (pinfunction "MGTPTXP2_216_B6") (pintype "output"))
    )
    (net (code "345") (name "unconnected-(U14H-MGTPTXP3_216-PadD7)") (class "Default")
      (node (ref "U14") (pin "D7") (pinfunction "MGTPTXP3_216_D7") (pintype "output"))
    )
    (net (code "346") (name "unconnected-(U14H-MGTREFCLK0N_216-PadE6)") (class "Default")
      (node (ref "U14") (pin "E6") (pinfunction "MGTREFCLK0N_216_E6") (pintype "input+no_connect"))
    )
    (net (code "347") (name "unconnected-(U14H-MGTREFCLK0P_216-PadF6)") (class "Default")
      (node (ref "U14") (pin "F6") (pinfunction "MGTREFCLK0P_216_F6") (pintype "input+no_connect"))
    )
    (net (code "348") (name "unconnected-(U14H-MGTREFCLK1N_216-PadE10)") (class "Default")
      (node (ref "U14") (pin "E10") (pinfunction "MGTREFCLK1N_216_E10") (pintype "input+no_connect"))
    )
    (net (code "349") (name "unconnected-(U14H-MGTREFCLK1P_216-PadF10)") (class "Default")
      (node (ref "U14") (pin "F10") (pinfunction "MGTREFCLK1P_216_F10") (pintype "input+no_connect"))
    )
    (net (code "350") (name "unconnected-(U14H-MGTRREF_216-PadF8)") (class "Default")
      (node (ref "U14") (pin "F8") (pinfunction "MGTRREF_216_F8") (pintype "input+no_connect"))
    )
    (net (code "351") (name "unconnected-(U14I-MGTAVCC-PadD6)") (class "Default")
      (node (ref "U14") (pin "D6") (pinfunction "MGTAVCC_D6") (pintype "power_in+no_connect"))
    )
    (net (code "352") (name "unconnected-(U14I-MGTAVCC-PadD10)") (class "Default")
      (node (ref "U14") (pin "D10") (pinfunction "MGTAVCC_D10") (pintype "power_in+no_connect"))
    )
    (net (code "353") (name "unconnected-(U14I-MGTAVCC-PadE8)") (class "Default")
      (node (ref "U14") (pin "E8") (pinfunction "MGTAVCC_E8") (pintype "power_in+no_connect"))
    )
    (net (code "354") (name "unconnected-(U14I-MGTAVCC-PadF7)") (class "Default")
      (node (ref "U14") (pin "F7") (pinfunction "MGTAVCC_F7") (pintype "power_in+no_connect"))
    )
    (net (code "355") (name "unconnected-(U14I-MGTAVCC-PadF9)") (class "Default")
      (node (ref "U14") (pin "F9") (pinfunction "MGTAVCC_F9") (pintype "power_in+no_connect"))
    )
    (net (code "356") (name "unconnected-(U14I-MGTAVTT-PadB5)") (class "Default")
      (node (ref "U14") (pin "B5") (pinfunction "MGTAVTT_B5") (pintype "power_in+no_connect"))
    )
    (net (code "357") (name "unconnected-(U14I-MGTAVTT-PadB7)") (class "Default")
      (node (ref "U14") (pin "B7") (pinfunction "MGTAVTT_B7") (pintype "power_in+no_connect"))
    )
    (net (code "358") (name "unconnected-(U14I-MGTAVTT-PadB9)") (class "Default")
      (node (ref "U14") (pin "B9") (pinfunction "MGTAVTT_B9") (pintype "power_in+no_connect"))
    )
    (net (code "359") (name "unconnected-(U14I-MGTAVTT-PadB11)") (class "Default")
      (node (ref "U14") (pin "B11") (pinfunction "MGTAVTT_B11") (pintype "power_in+no_connect"))
    )
    (net (code "360") (name "unconnected-(U14I-MGTAVTT-PadC4)") (class "Default")
      (node (ref "U14") (pin "C4") (pinfunction "MGTAVTT_C4") (pintype "power_in+no_connect"))
    )
    (net (code "361") (name "unconnected-(U14I-MGTAVTT-PadC8)") (class "Default")
      (node (ref "U14") (pin "C8") (pinfunction "MGTAVTT_C8") (pintype "power_in+no_connect"))
    )
    (net (code "362") (name "unconnected-(U15-ACBUS0-Pad26)") (class "Default")
      (node (ref "U15") (pin "26") (pinfunction "ACBUS0_26") (pintype "bidirectional"))
    )
    (net (code "363") (name "unconnected-(U15-ACBUS1-Pad27)") (class "Default")
      (node (ref "U15") (pin "27") (pinfunction "ACBUS1_27") (pintype "bidirectional"))
    )
    (net (code "364") (name "unconnected-(U15-ACBUS2-Pad28)") (class "Default")
      (node (ref "U15") (pin "28") (pinfunction "ACBUS2_28") (pintype "bidirectional"))
    )
    (net (code "365") (name "unconnected-(U15-ACBUS4-Pad30)") (class "Default")
      (node (ref "U15") (pin "30") (pinfunction "ACBUS4_30") (pintype "bidirectional"))
    )
    (net (code "366") (name "unconnected-(U15-ACBUS5-Pad32)") (class "Default")
      (node (ref "U15") (pin "32") (pinfunction "ACBUS5_32") (pintype "bidirectional"))
    )
    (net (code "367") (name "unconnected-(U15-ACBUS6-Pad33)") (class "Default")
      (node (ref "U15") (pin "33") (pinfunction "ACBUS6_33") (pintype "bidirectional"))
    )
    (net (code "368") (name "unconnected-(U15-ACBUS7-Pad34)") (class "Default")
      (node (ref "U15") (pin "34") (pinfunction "ACBUS7_34") (pintype "bidirectional"))
    )
    (net (code "369") (name "unconnected-(U15-ADBUS4-Pad21)") (class "Default")
      (node (ref "U15") (pin "21") (pinfunction "ADBUS4_21") (pintype "bidirectional"))
    )
    (net (code "370") (name "unconnected-(U15-ADBUS5-Pad22)") (class "Default")
      (node (ref "U15") (pin "22") (pinfunction "ADBUS5_22") (pintype "bidirectional"))
    )
    (net (code "371") (name "unconnected-(U15-ADBUS6-Pad23)") (class "Default")
      (node (ref "U15") (pin "23") (pinfunction "ADBUS6_23") (pintype "bidirectional"))
    )
    (net (code "372") (name "unconnected-(U15-ADBUS7-Pad24)") (class "Default")
      (node (ref "U15") (pin "24") (pinfunction "ADBUS7_24") (pintype "bidirectional"))
    )
    (net (code "373") (name "unconnected-(U15-BCBUS0-Pad48)") (class "Default")
      (node (ref "U15") (pin "48") (pinfunction "BCBUS0_48") (pintype "bidirectional"))
    )
    (net (code "374") (name "unconnected-(U15-BCBUS1-Pad52)") (class "Default")
      (node (ref "U15") (pin "52") (pinfunction "BCBUS1_52") (pintype "bidirectional"))
    )
    (net (code "375") (name "unconnected-(U15-BCBUS2-Pad53)") (class "Default")
      (node (ref "U15") (pin "53") (pinfunction "BCBUS2_53") (pintype "bidirectional"))
    )
    (net (code "376") (name "unconnected-(U15-BCBUS5-Pad57)") (class "Default")
      (node (ref "U15") (pin "57") (pinfunction "BCBUS5_57") (pintype "bidirectional"))
    )
    (net (code "377") (name "unconnected-(U15-BCBUS6-Pad58)") (class "Default")
      (node (ref "U15") (pin "58") (pinfunction "BCBUS6_58") (pintype "bidirectional"))
    )
    (net (code "378") (name "unconnected-(U15-BCBUS7-Pad59)") (class "Default")
      (node (ref "U15") (pin "59") (pinfunction "BCBUS7_59") (pintype "bidirectional"))
    )
    (net (code "379") (name "unconnected-(U15-BDBUS6-Pad45)") (class "Default")
      (node (ref "U15") (pin "45") (pinfunction "BDBUS6_45") (pintype "bidirectional"))
    )
    (net (code "380") (name "unconnected-(U15-~{PWREN}-Pad60)") (class "Default")
      (node (ref "U15") (pin "60") (pinfunction "~{PWREN}_60") (pintype "output"))
    )
    (net (code "381") (name "unconnected-(U15-~{SUSPEND}-Pad36)") (class "Default")
      (node (ref "U15") (pin "36") (pinfunction "~{SUSPEND}_36") (pintype "output"))
    )
  )
)
